# aqc-rev3.net
KiCad netlist of a schematic drawn in EAGLE
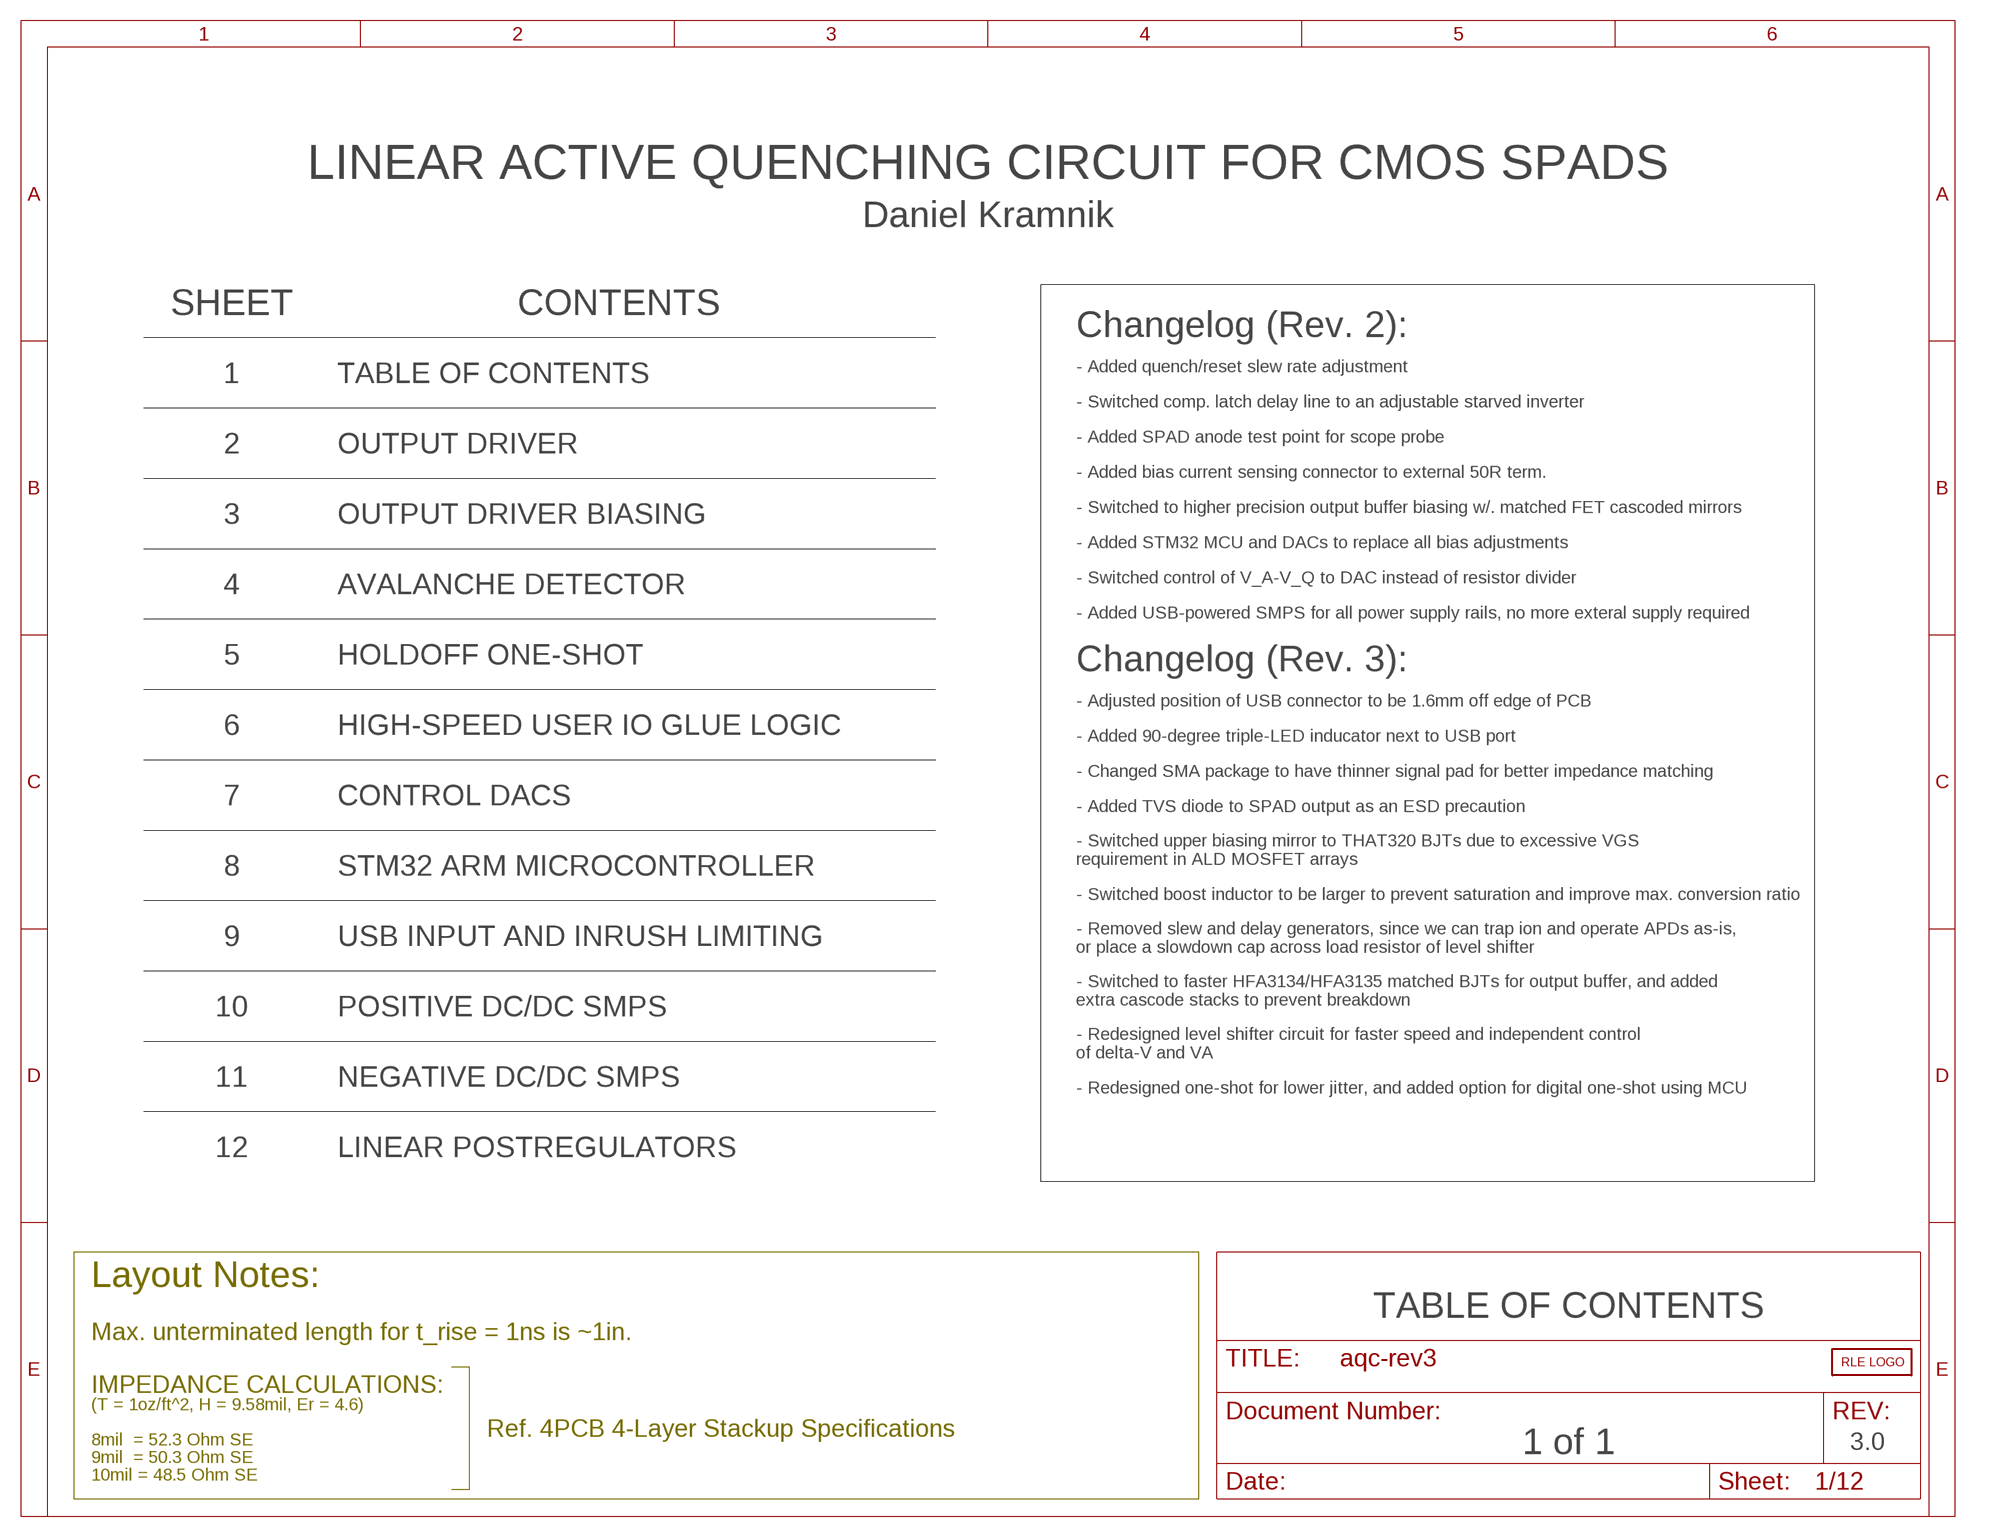
[diagram p0: schematic, sheet 1]
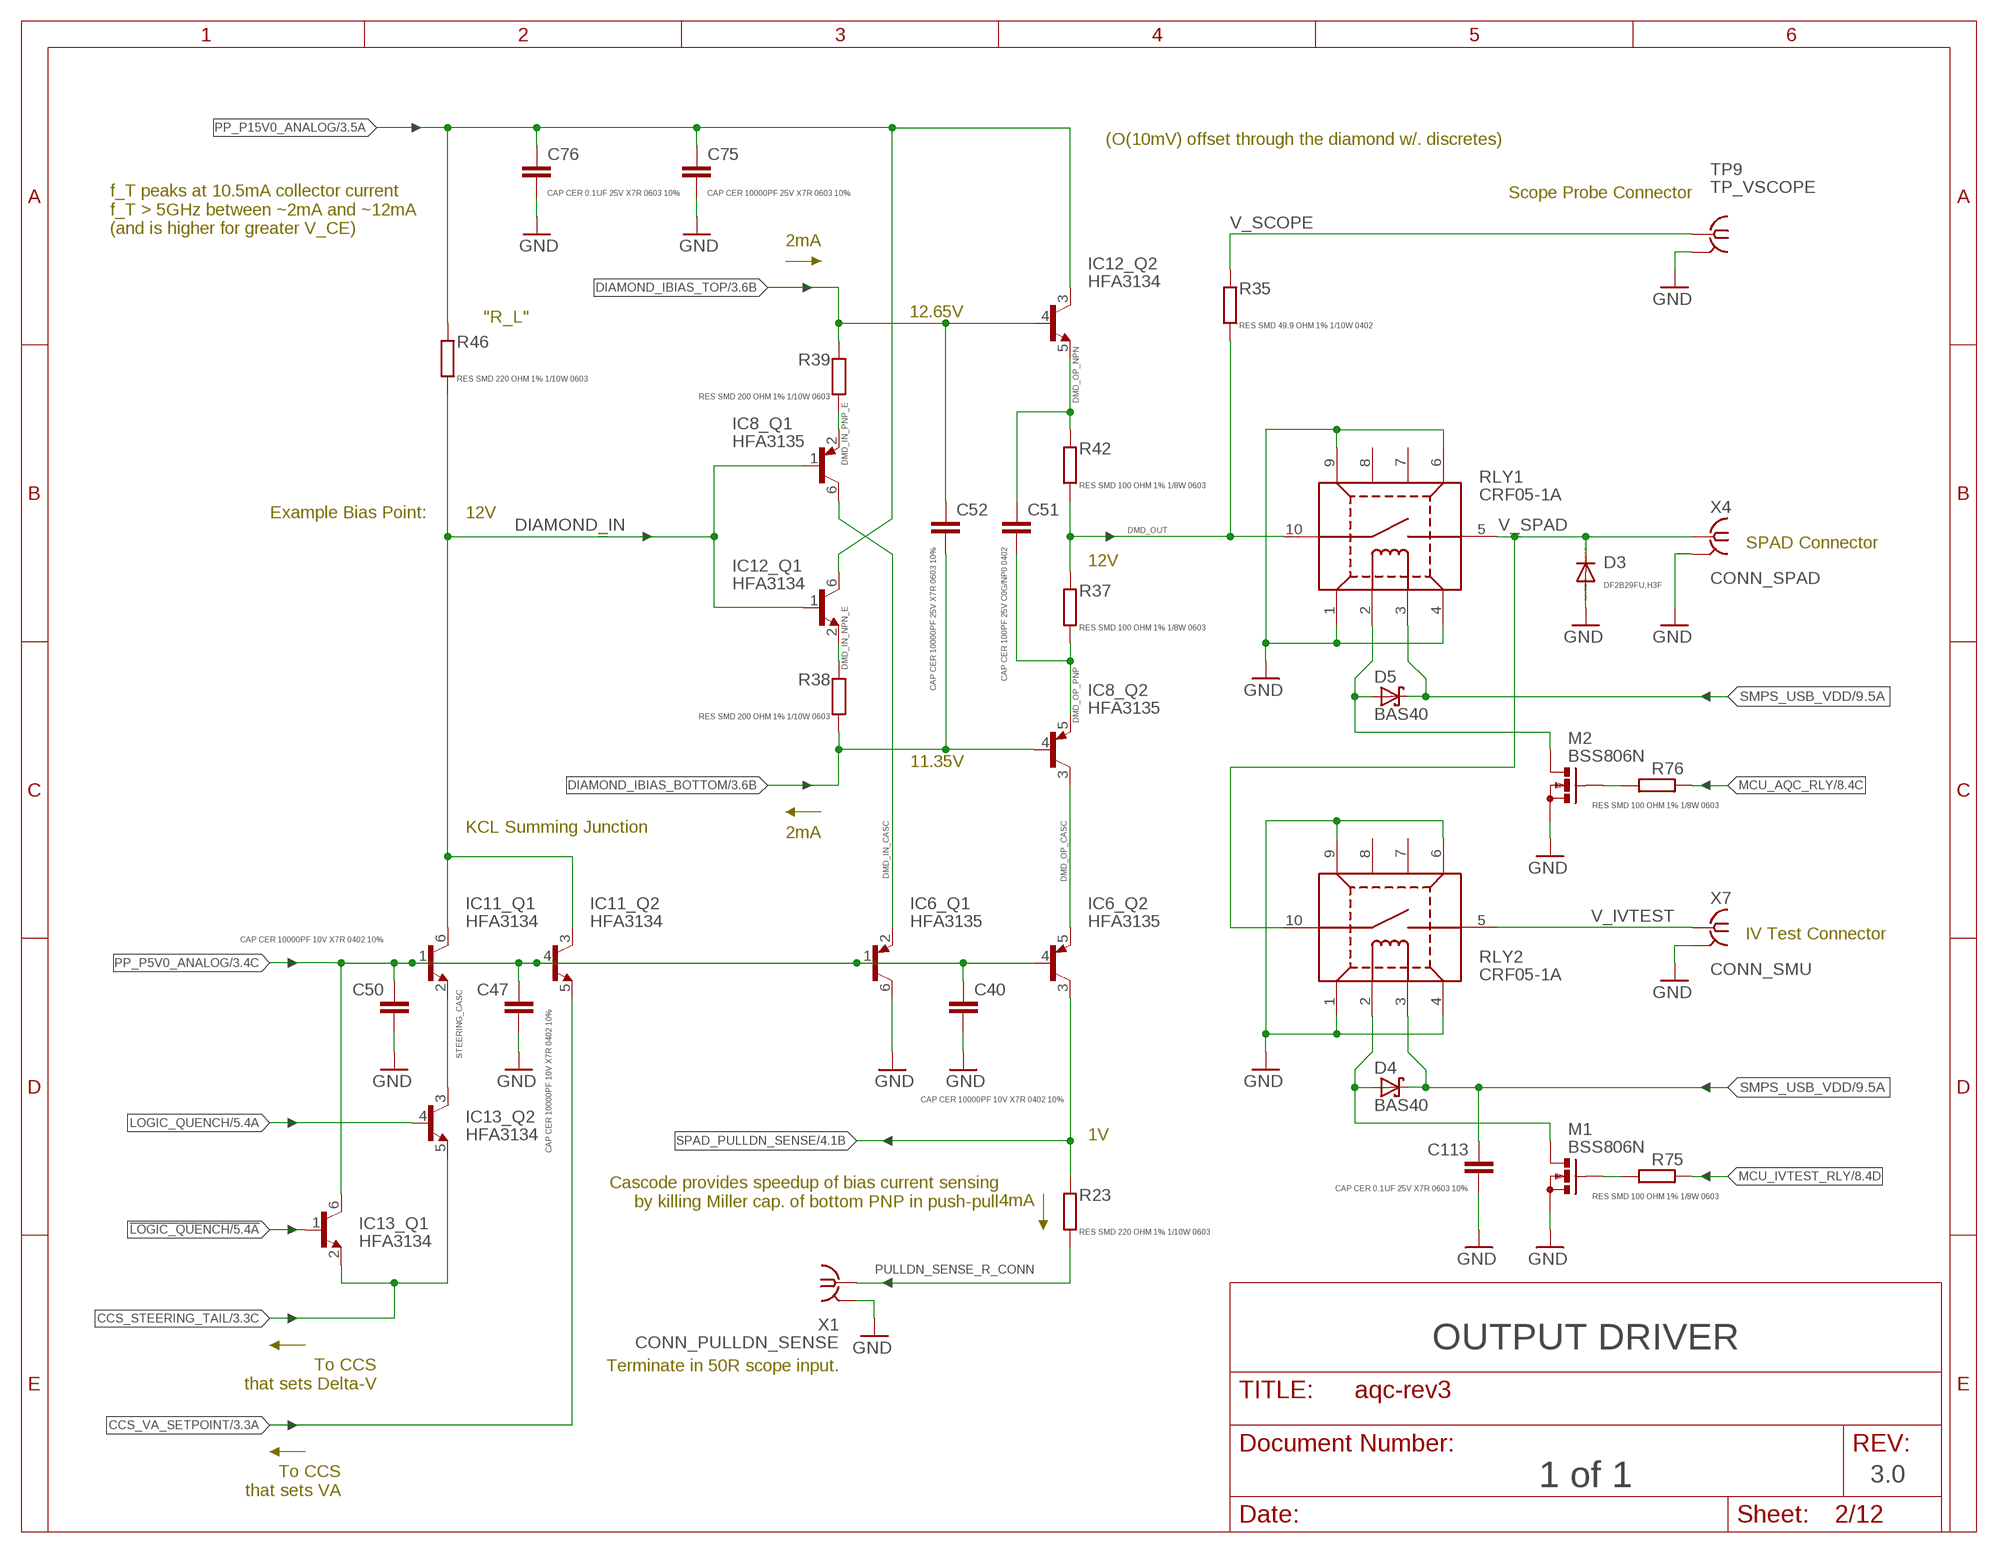
[diagram p1: schematic, sheet 2]
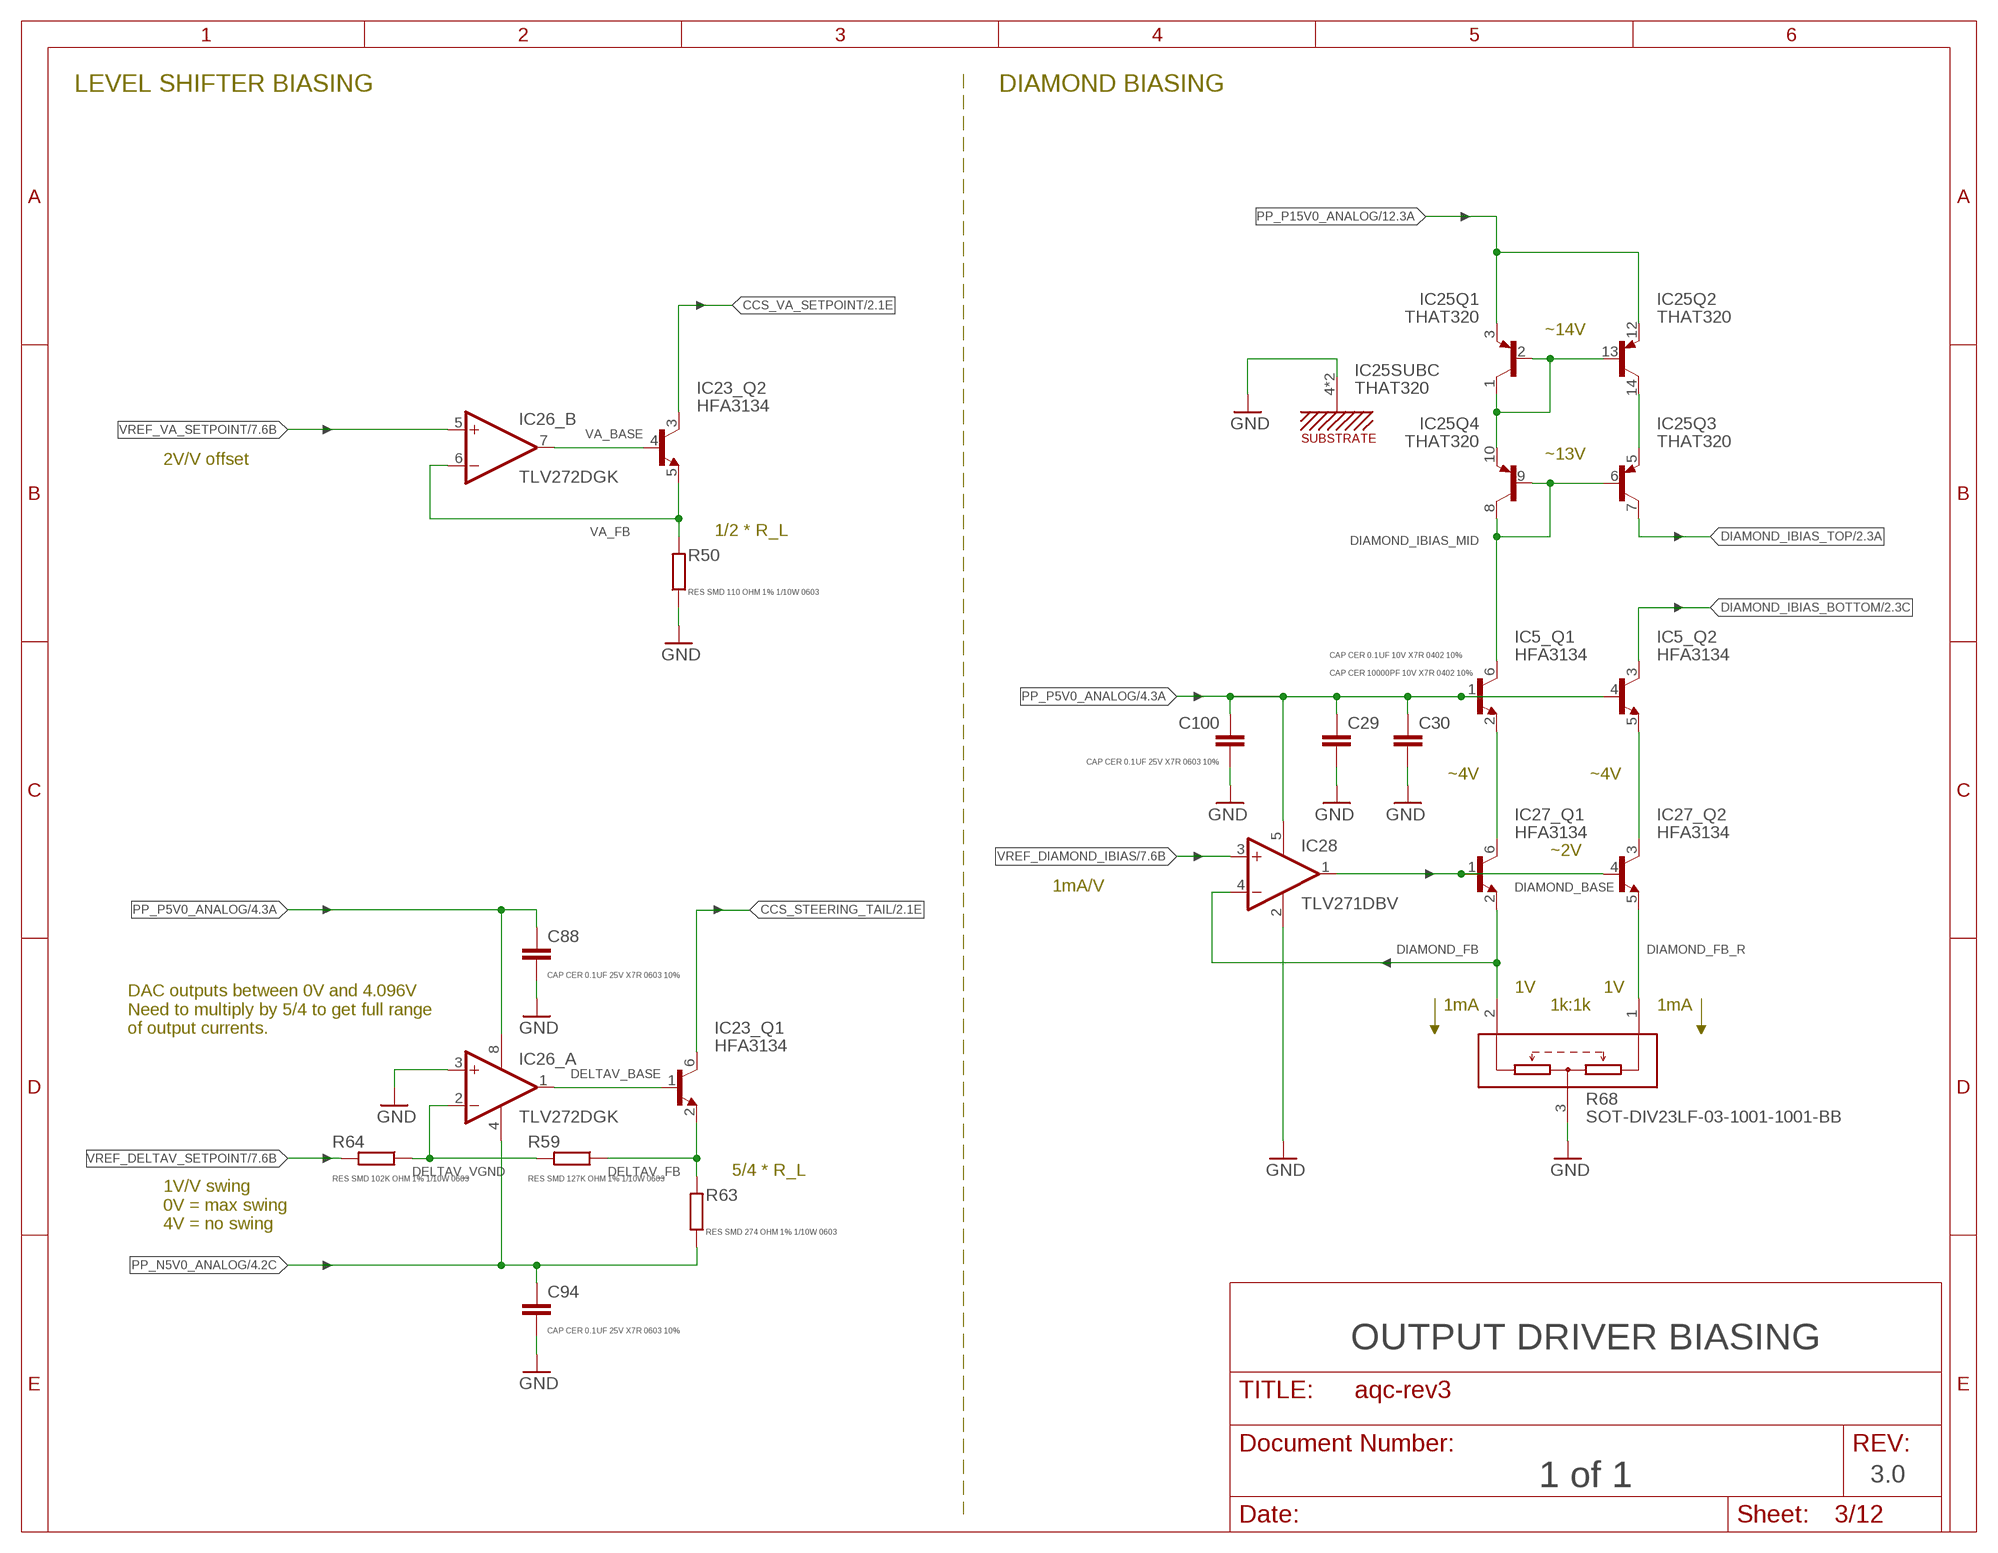
[diagram p2: schematic, sheet 3]
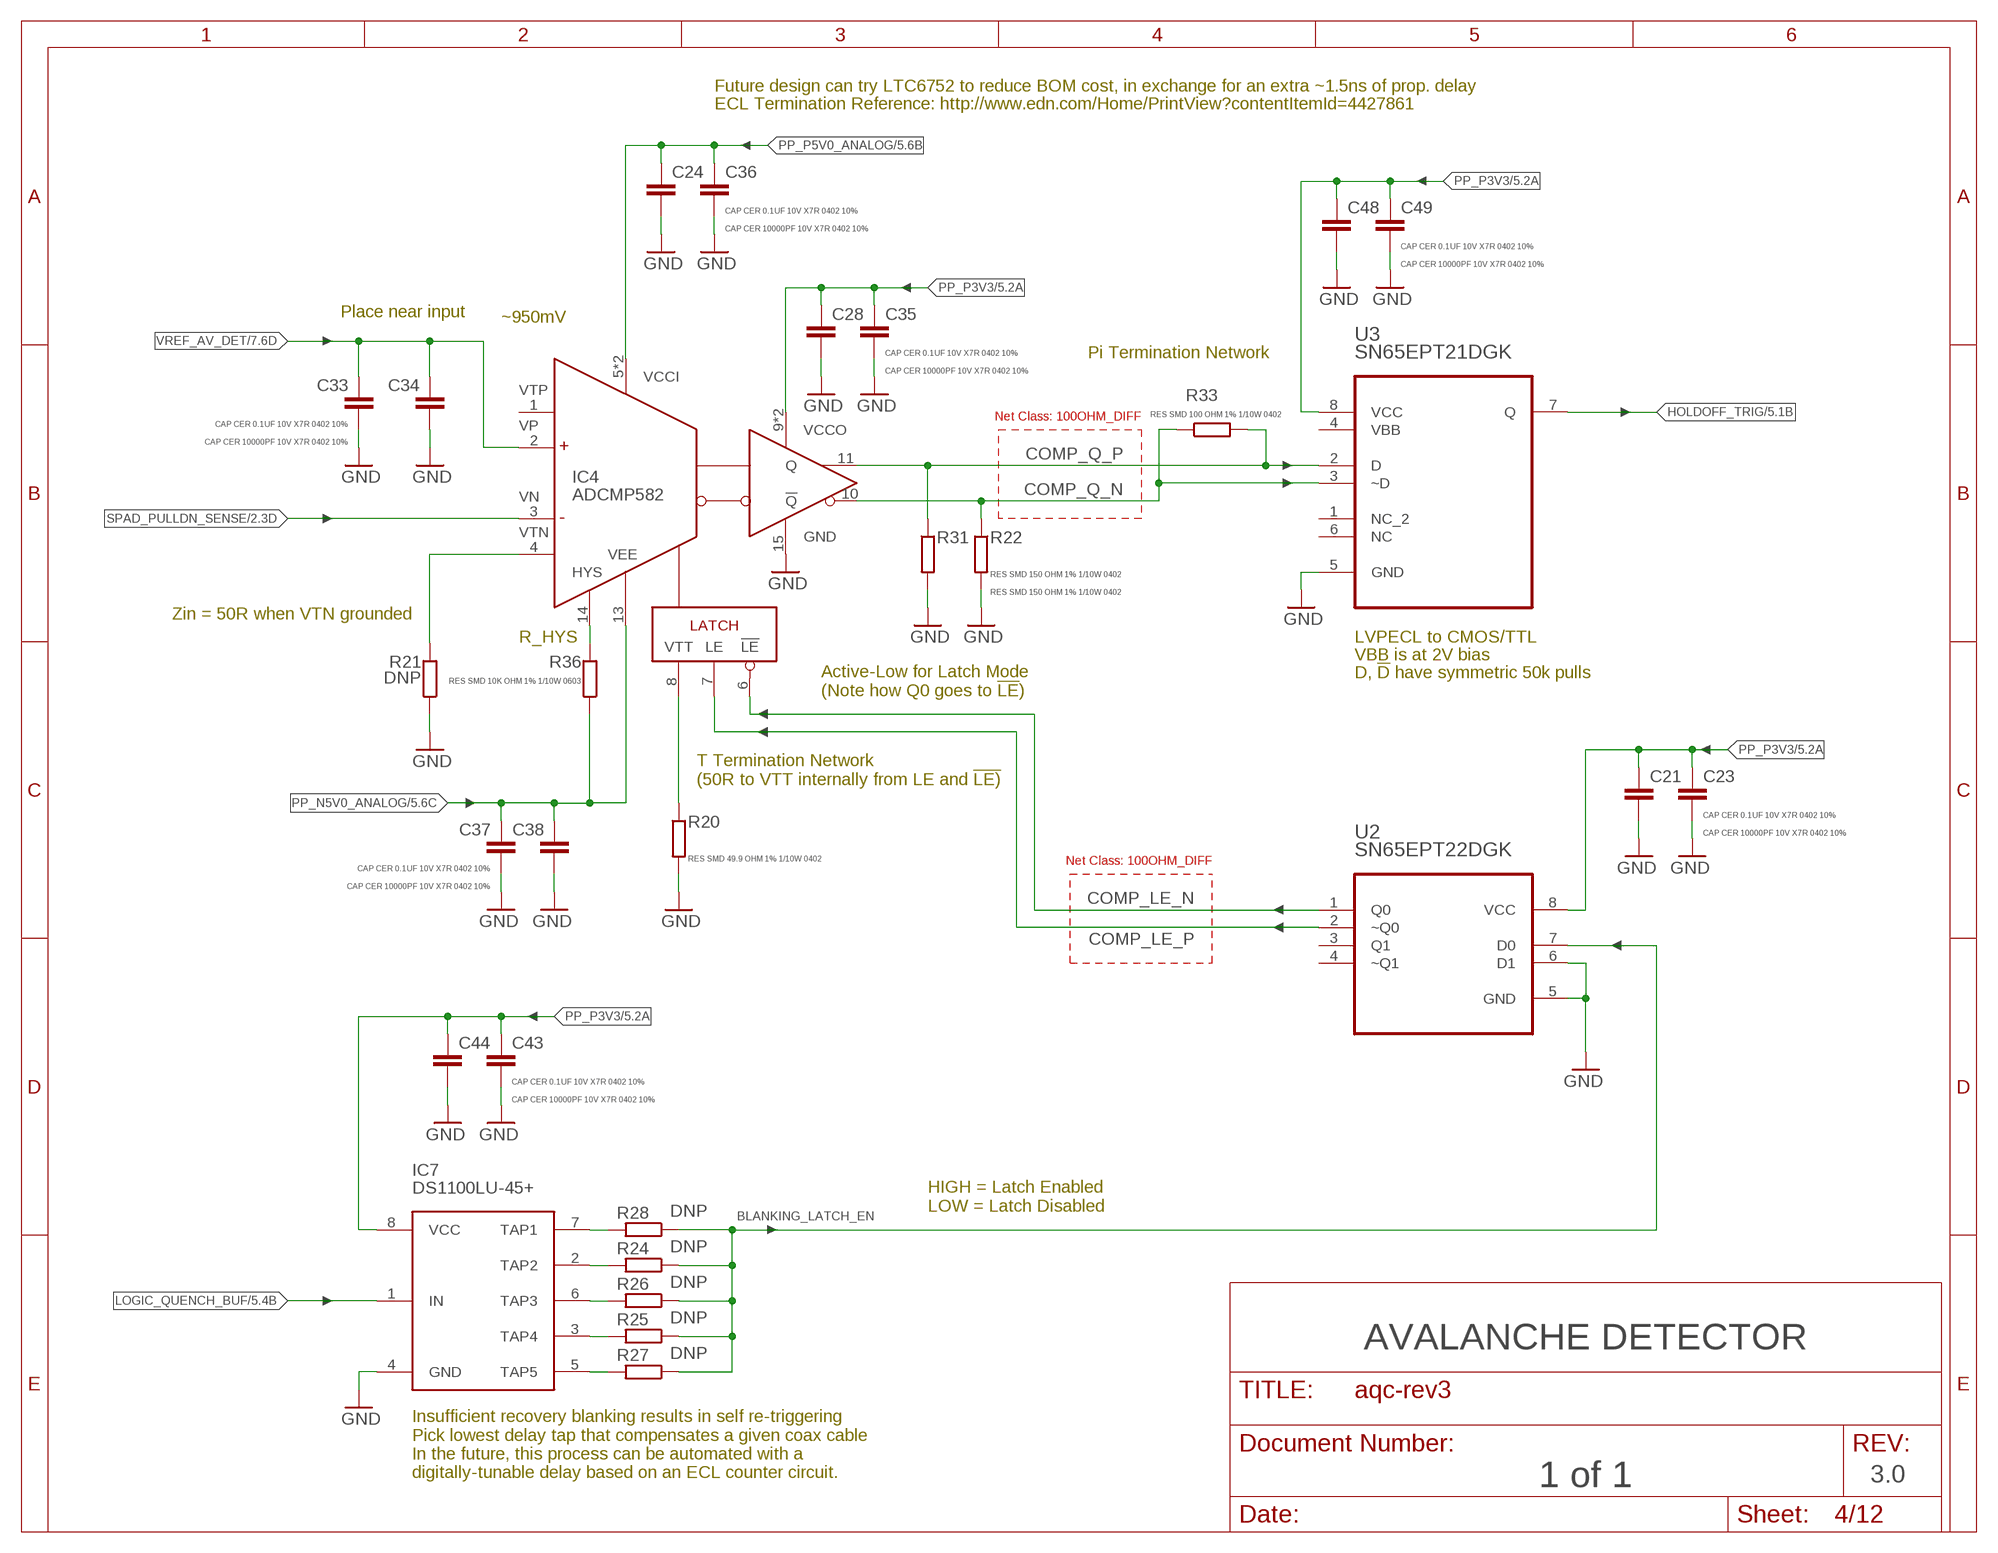
[diagram p3: schematic, sheet 4]
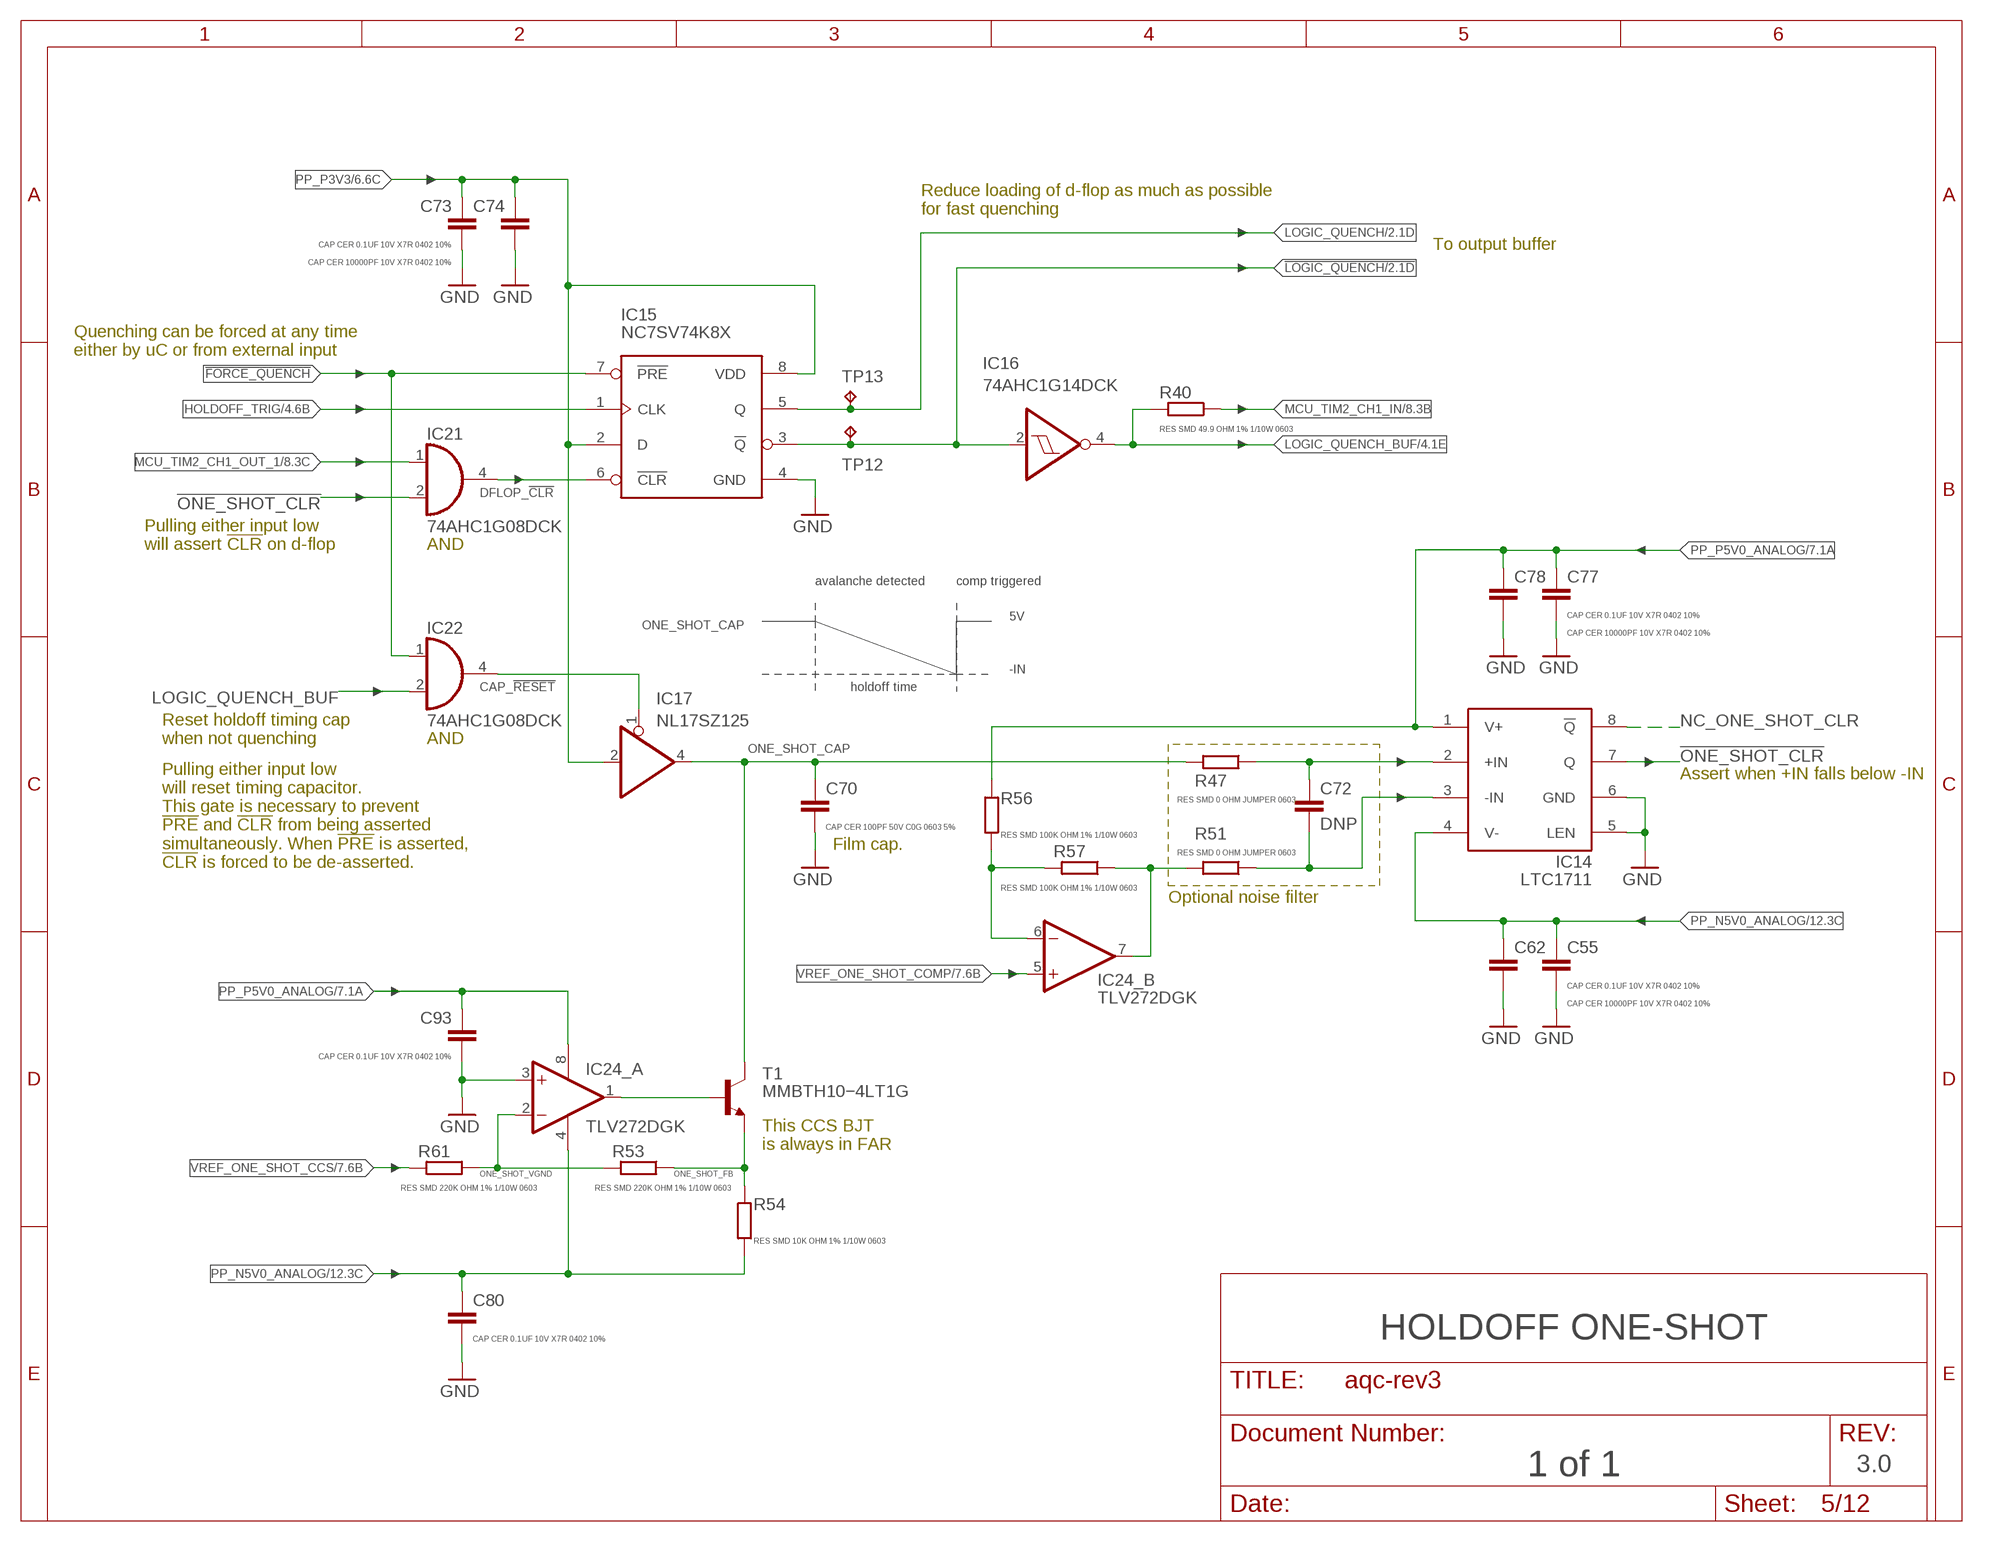
[diagram p4: schematic, sheet 5]
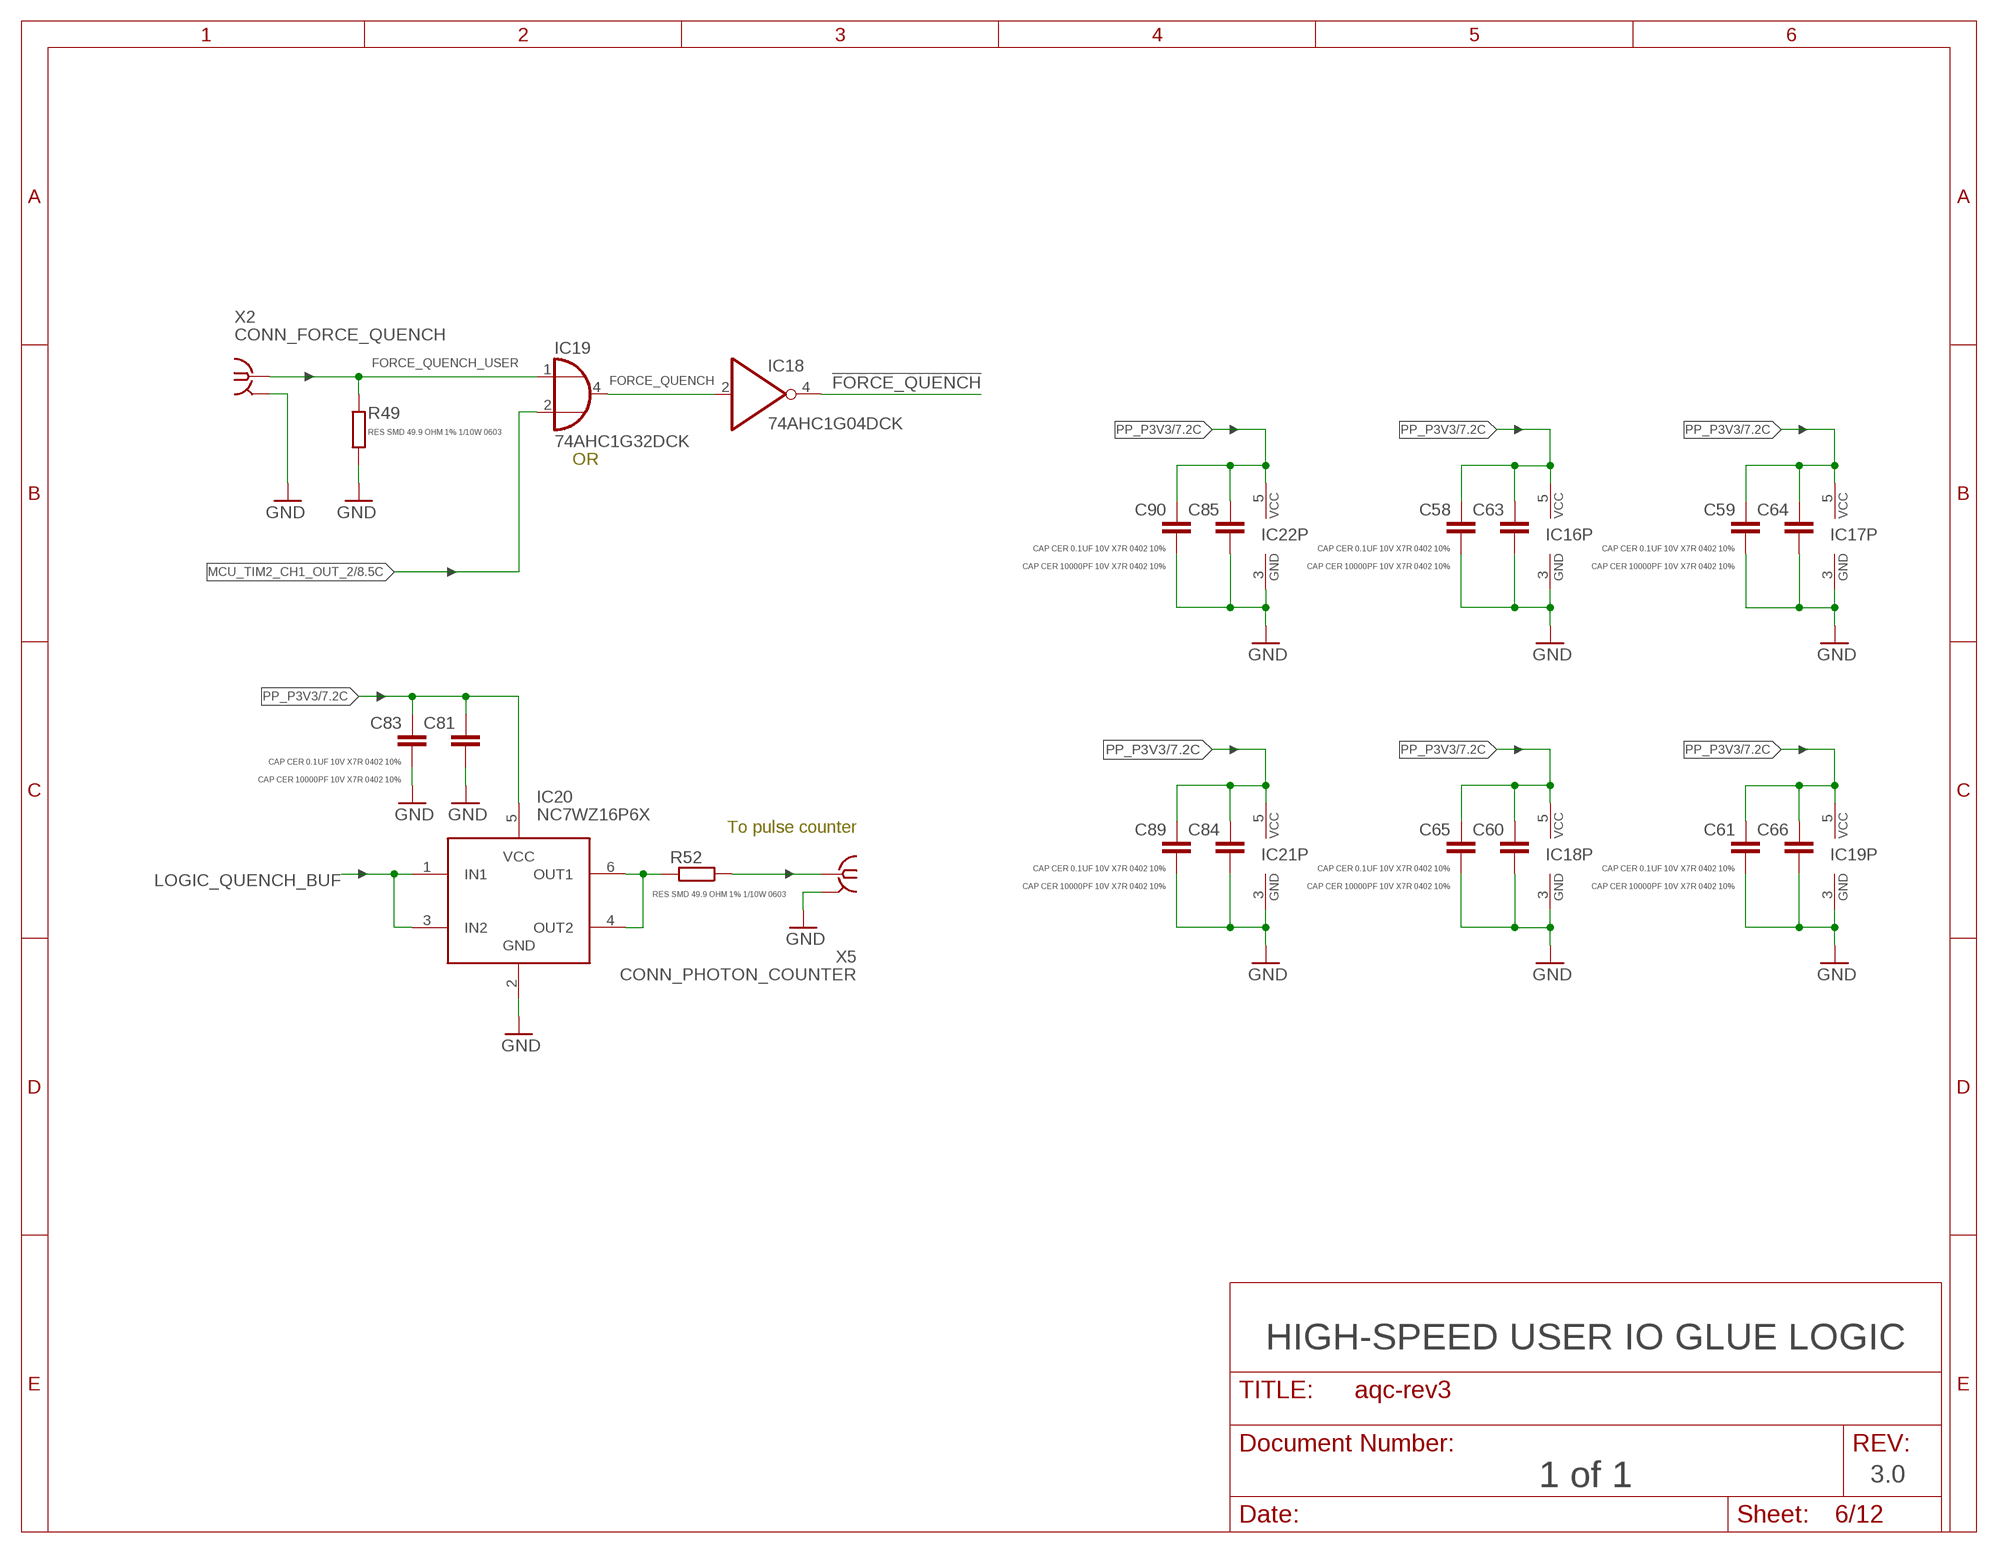
[diagram p5: schematic, sheet 6]
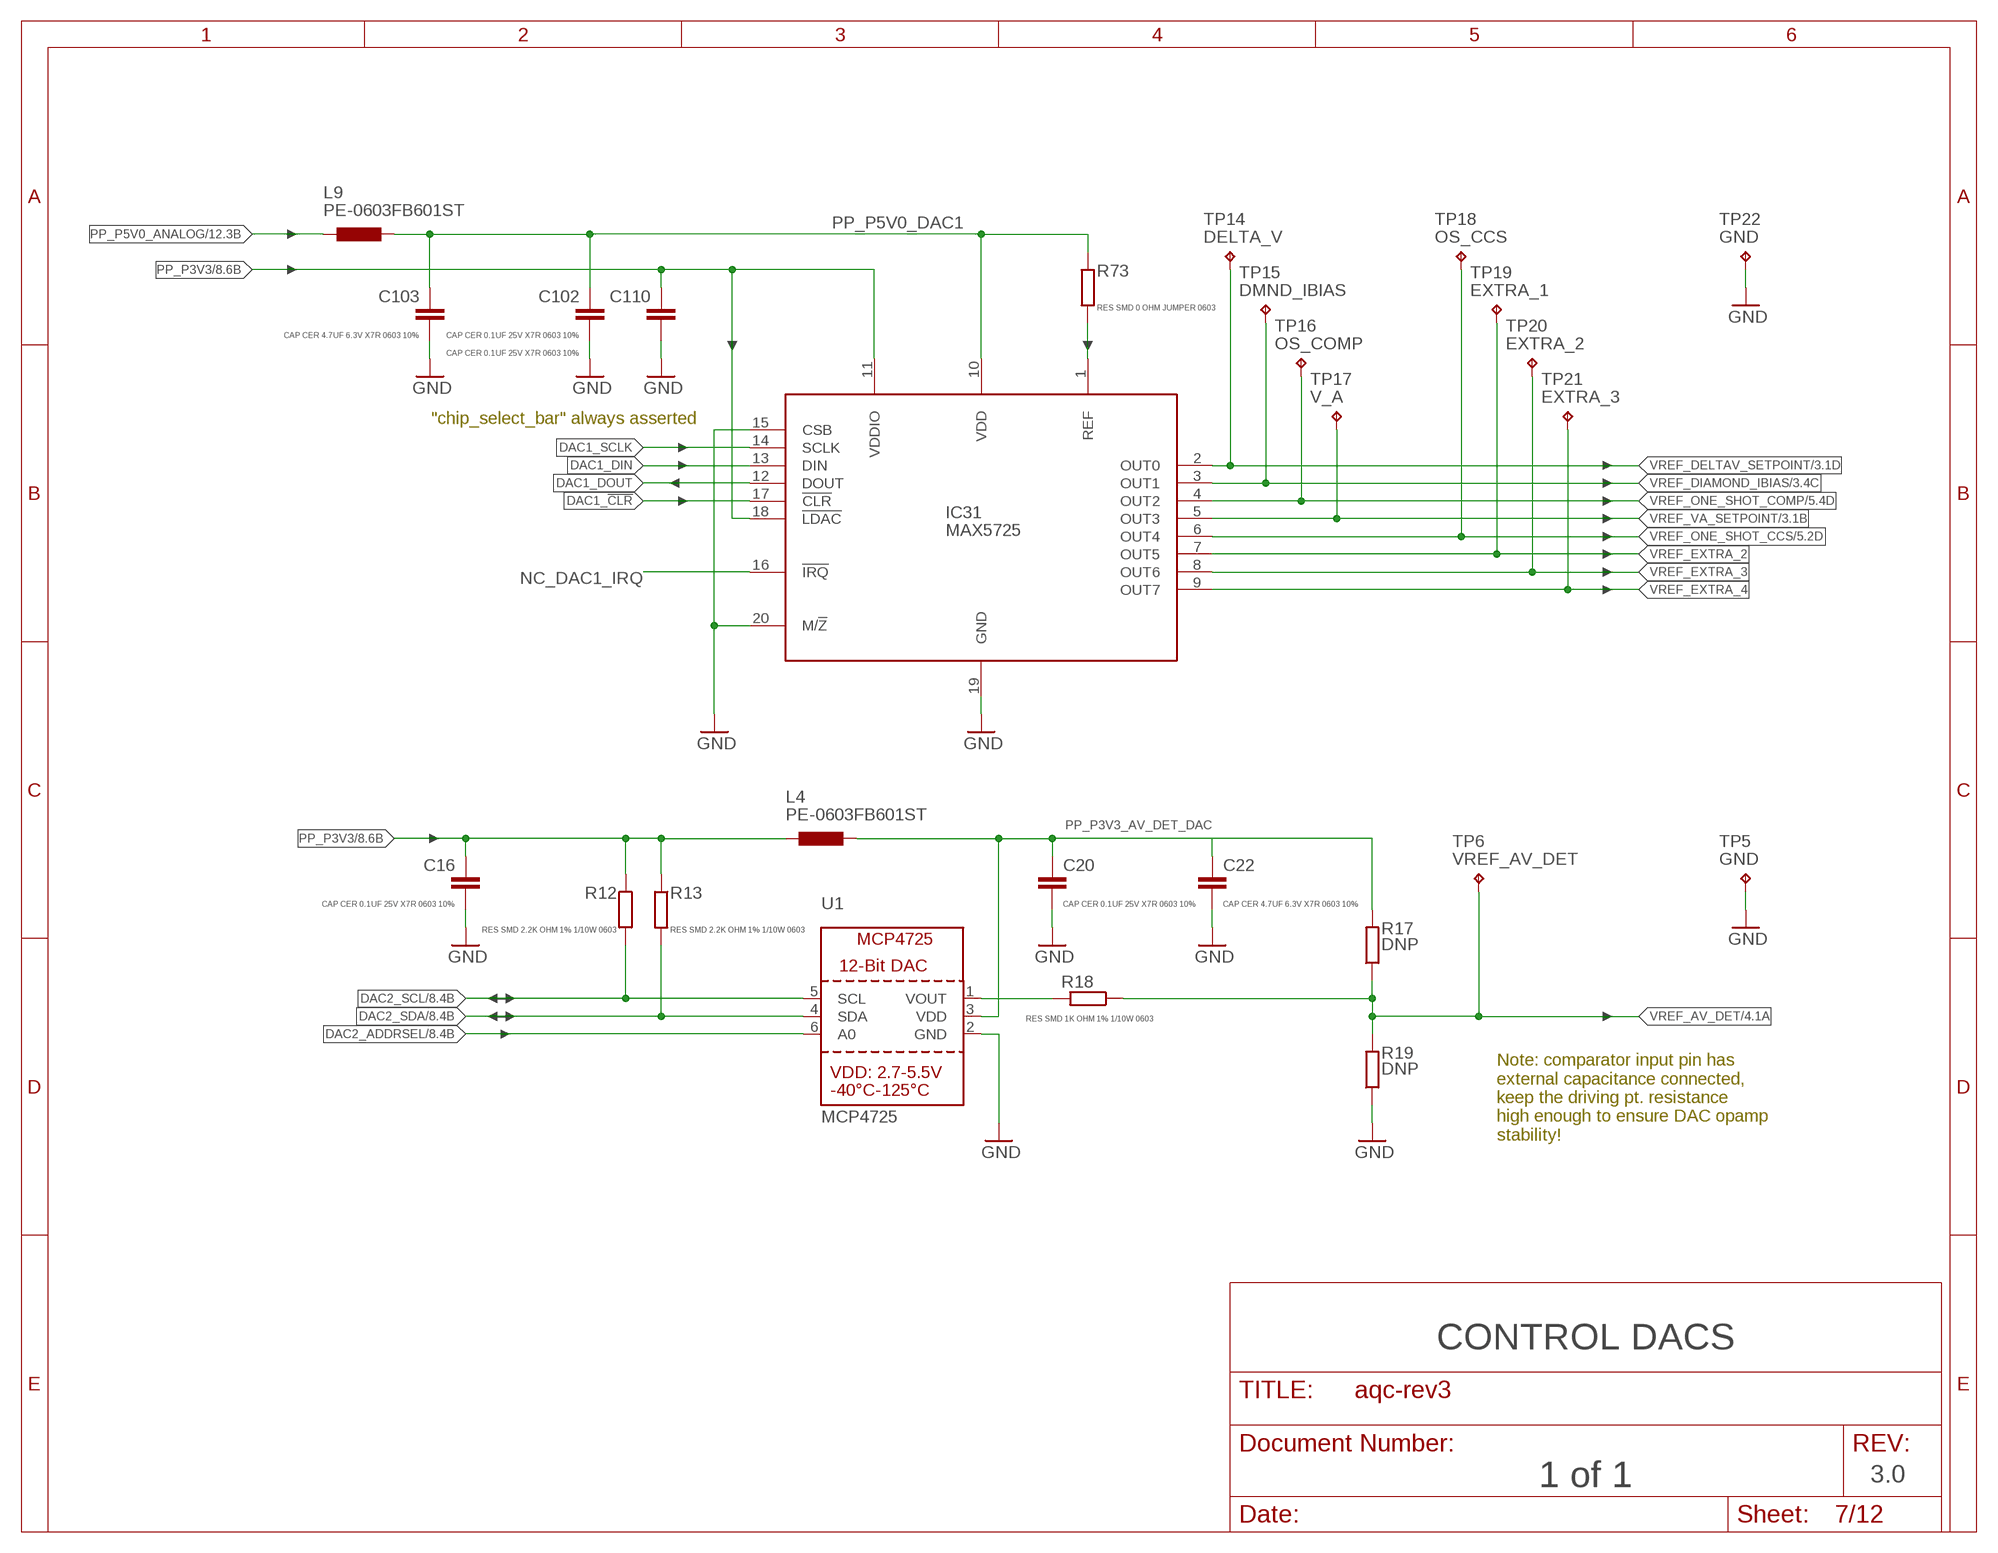
[diagram p6: schematic, sheet 7]
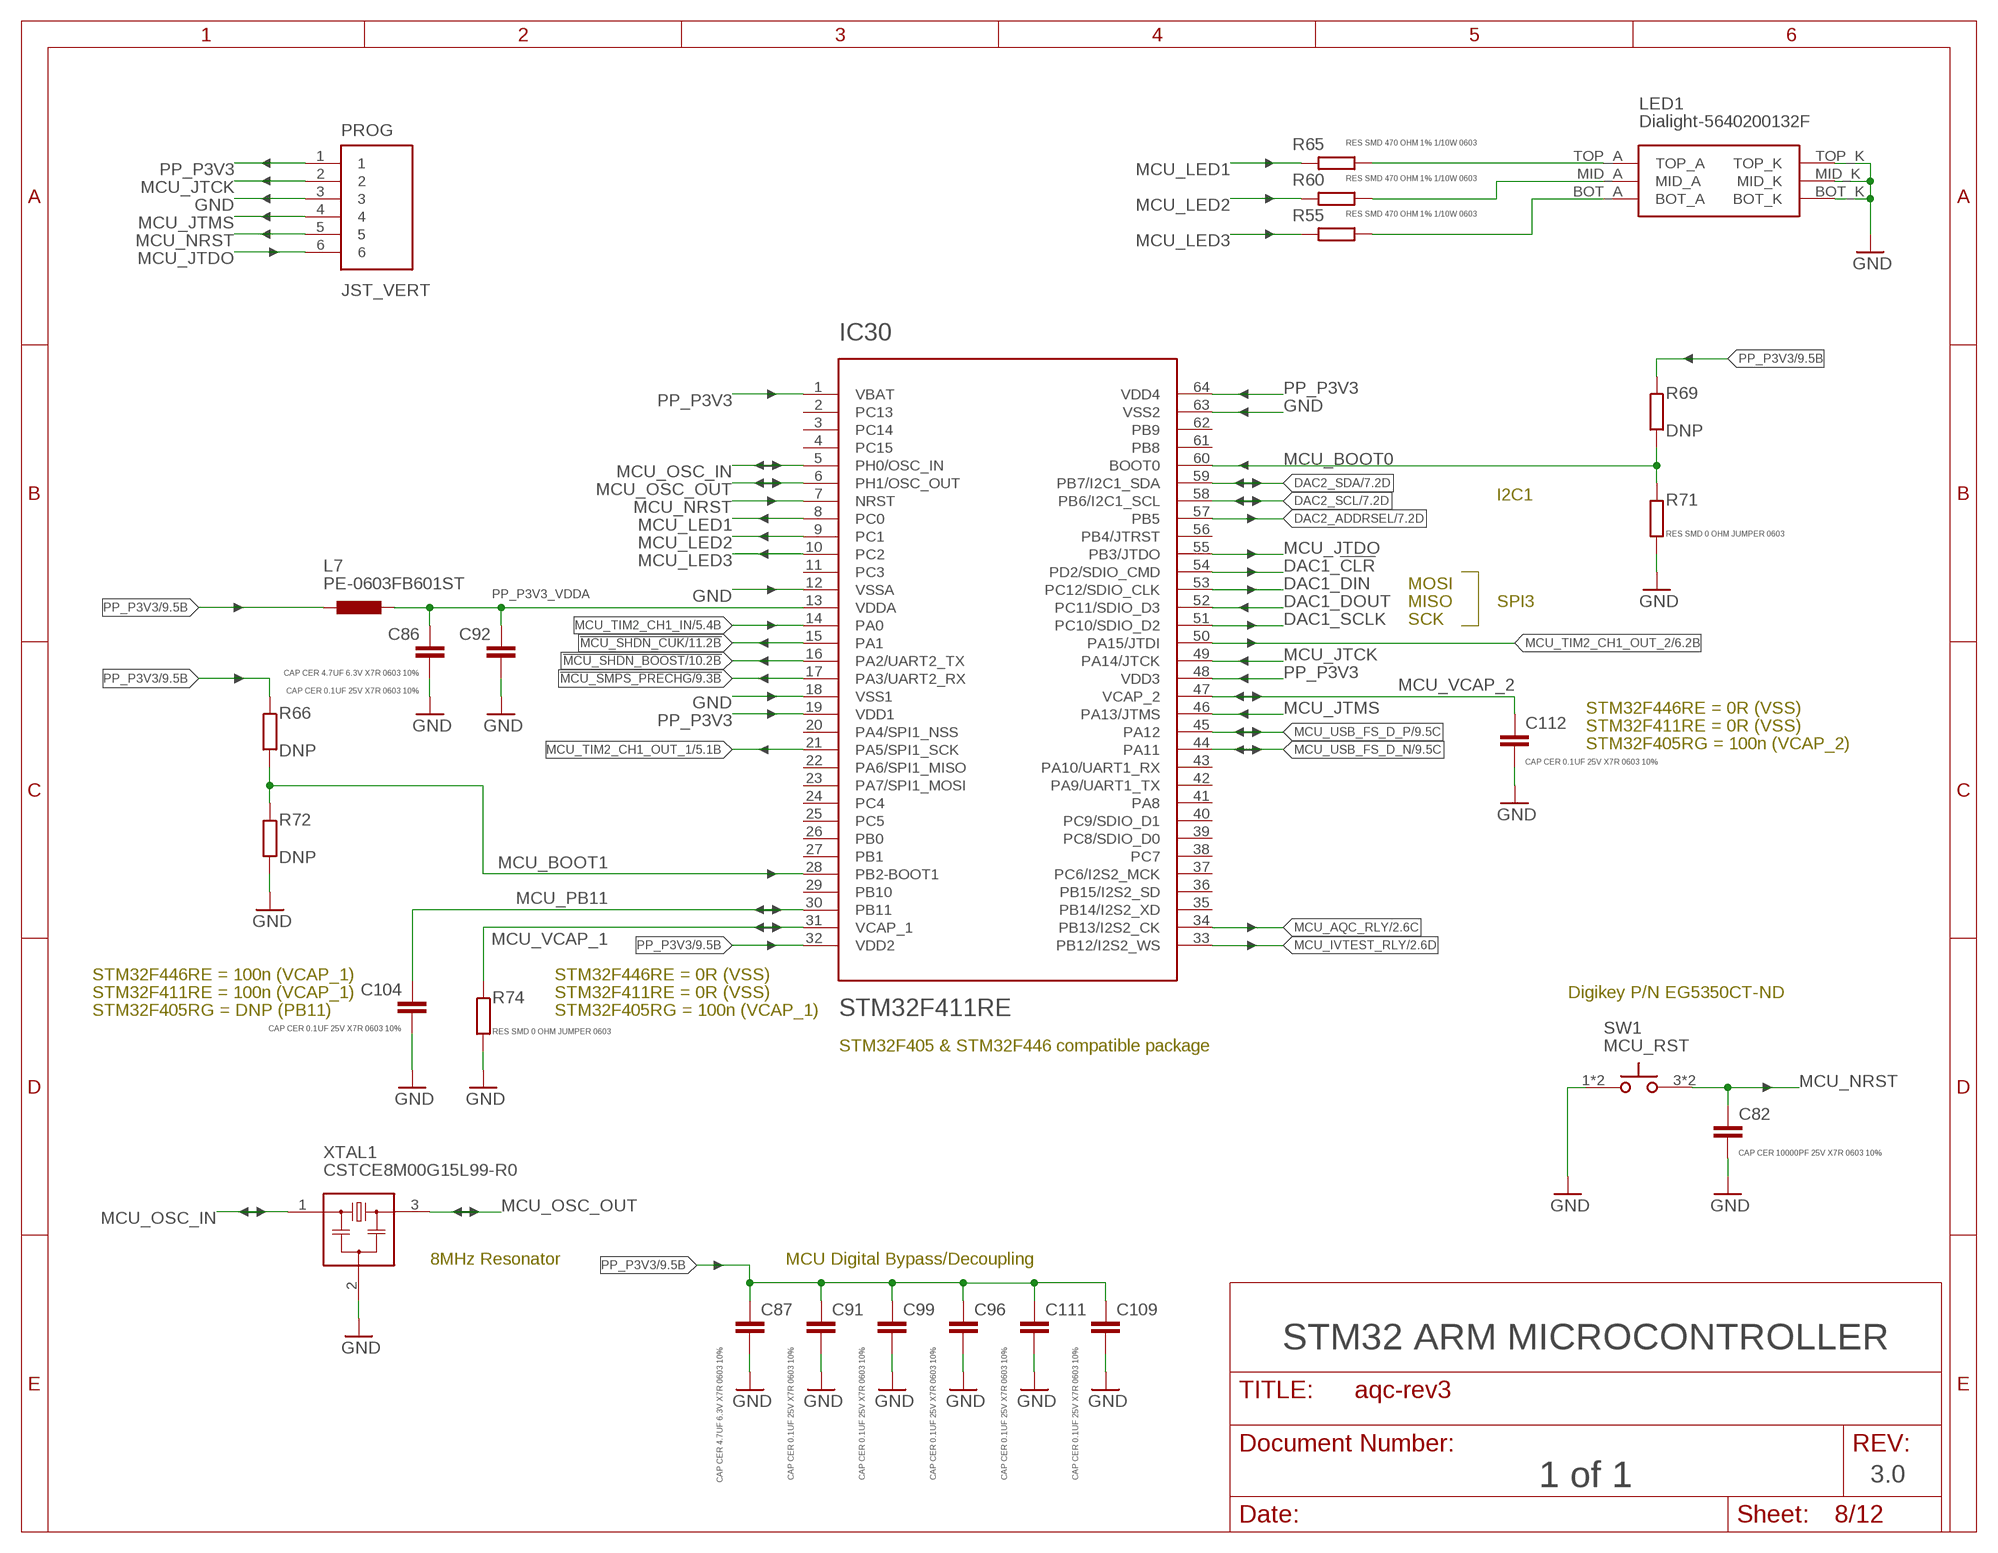
[diagram p7: schematic, sheet 8]
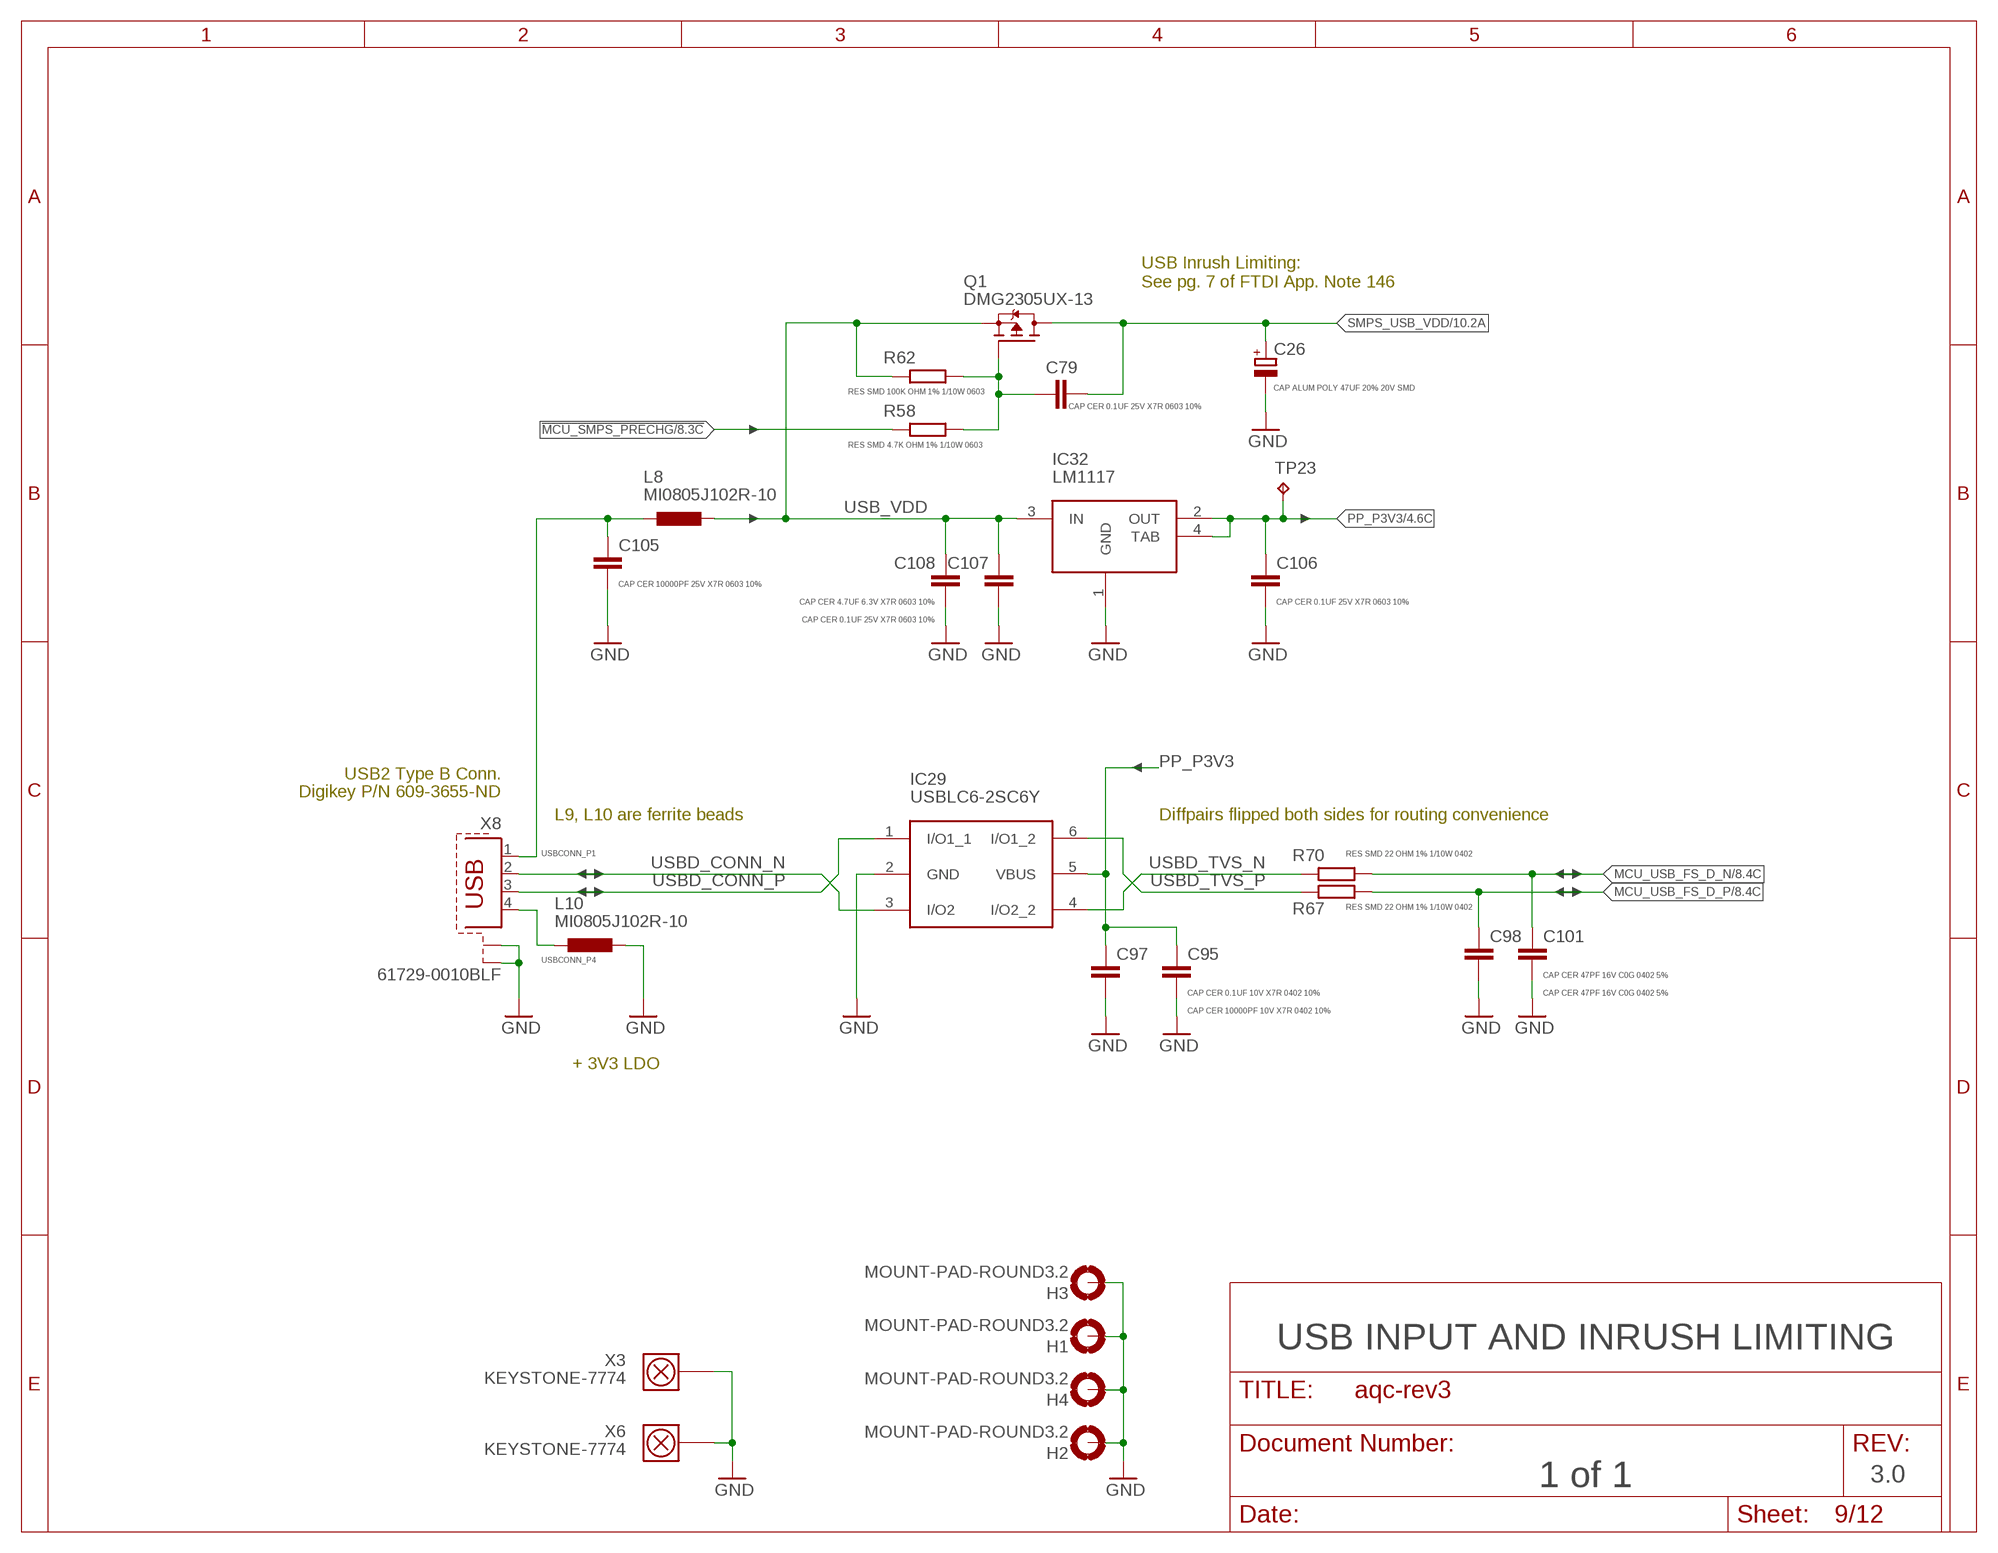
[diagram p8: schematic, sheet 9]
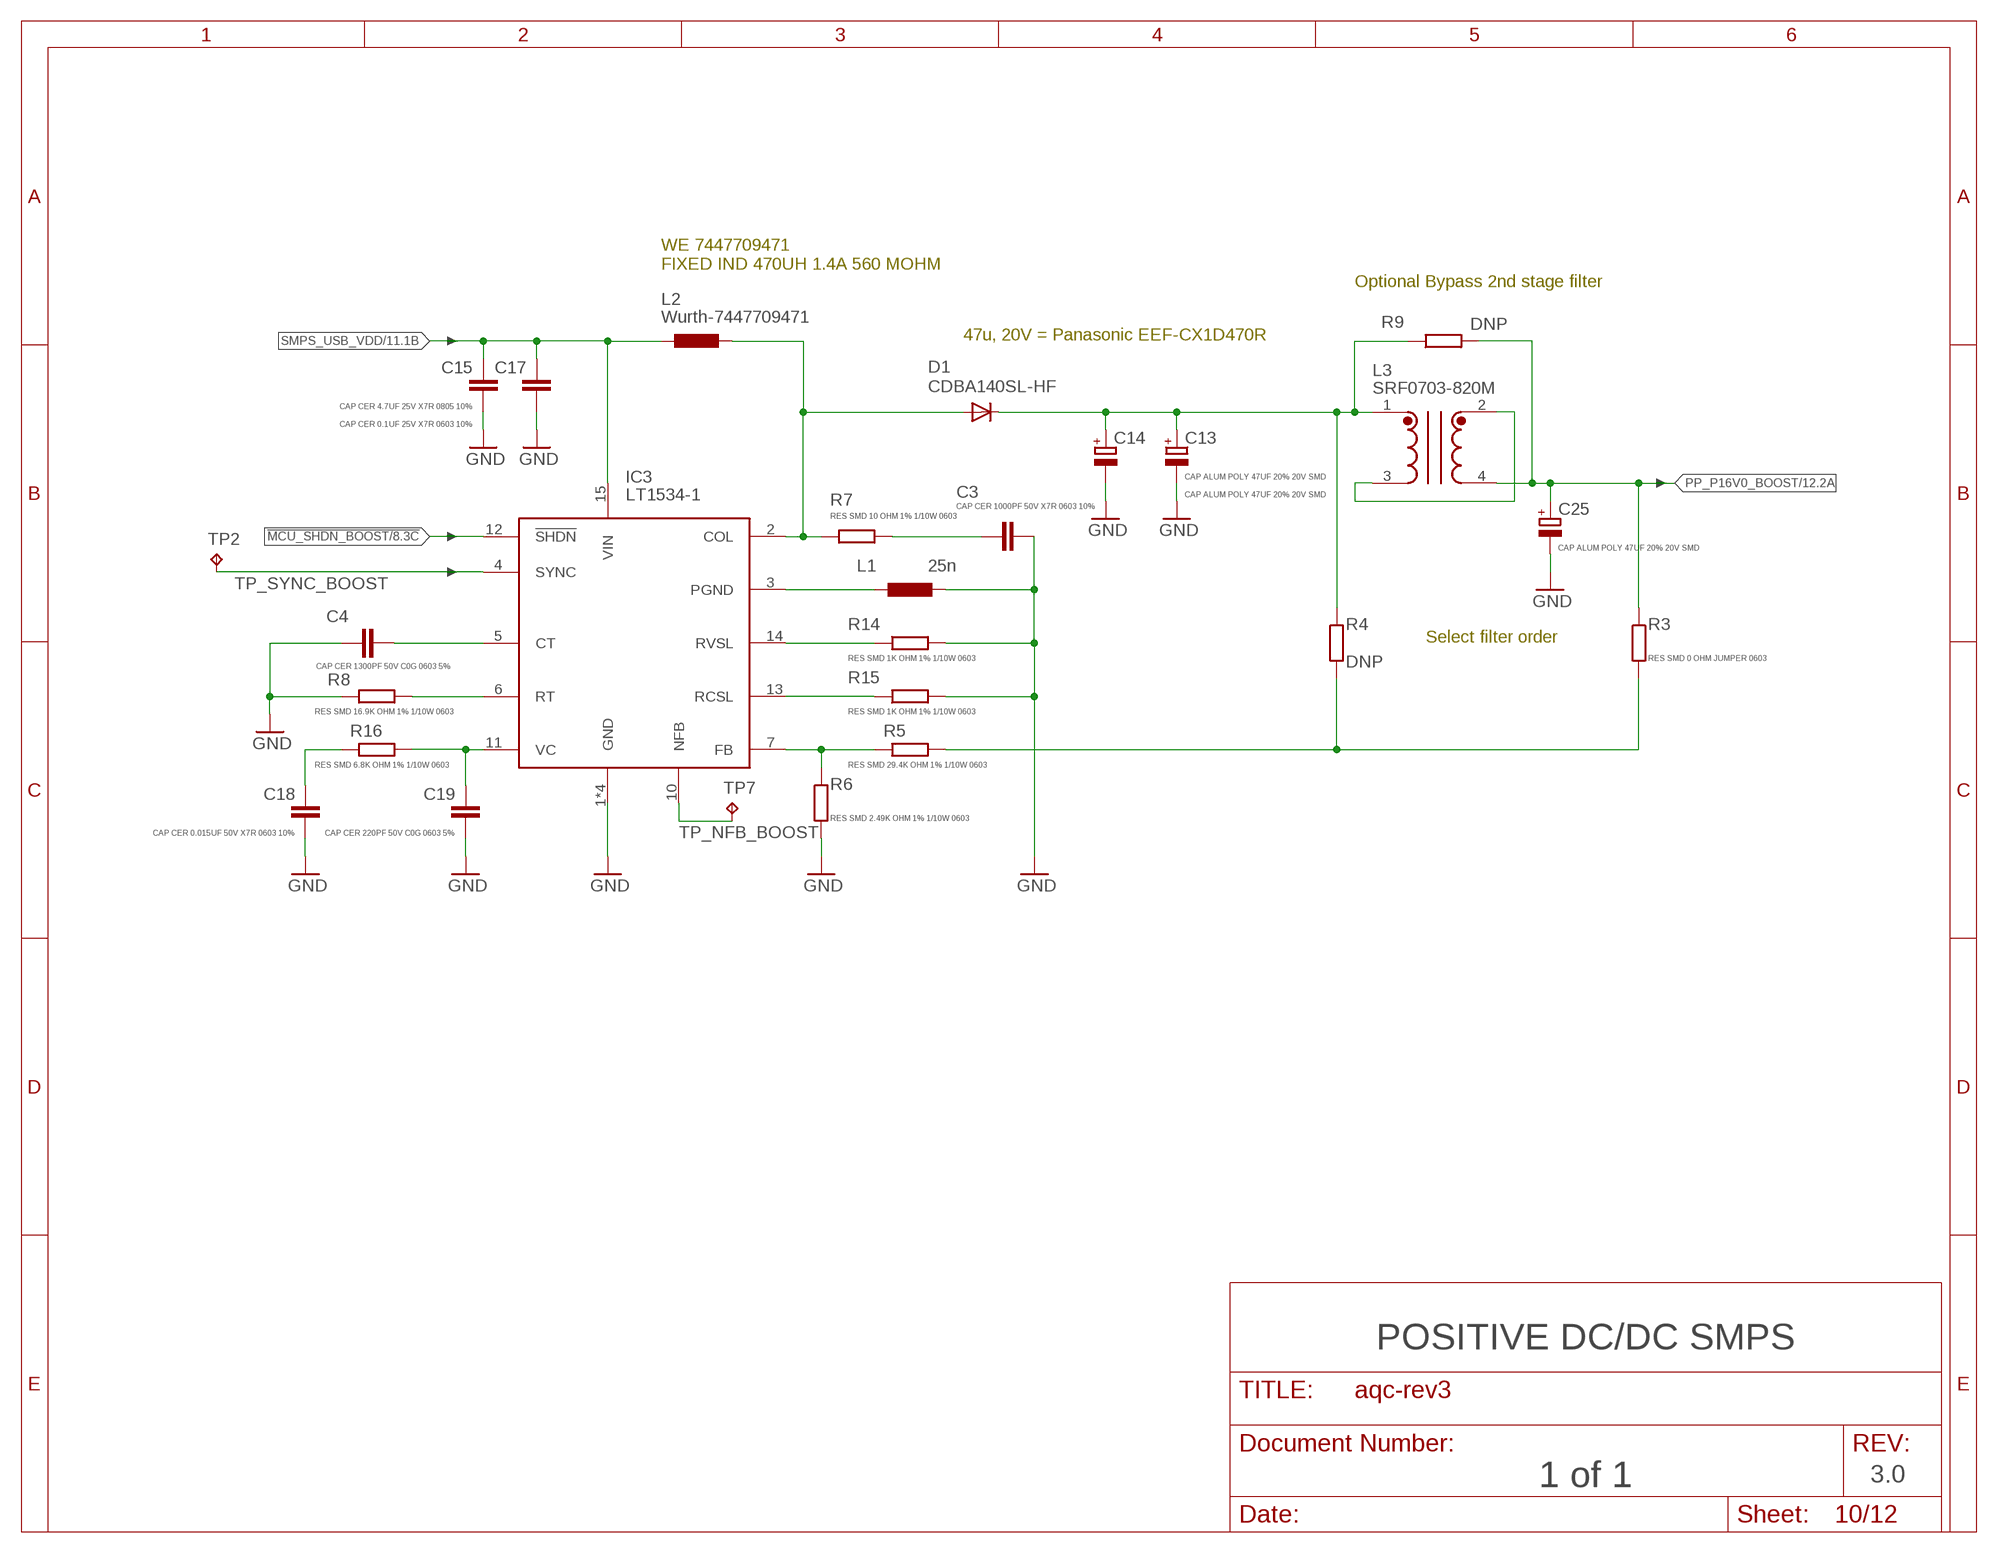
[diagram p9: schematic, sheet 10]
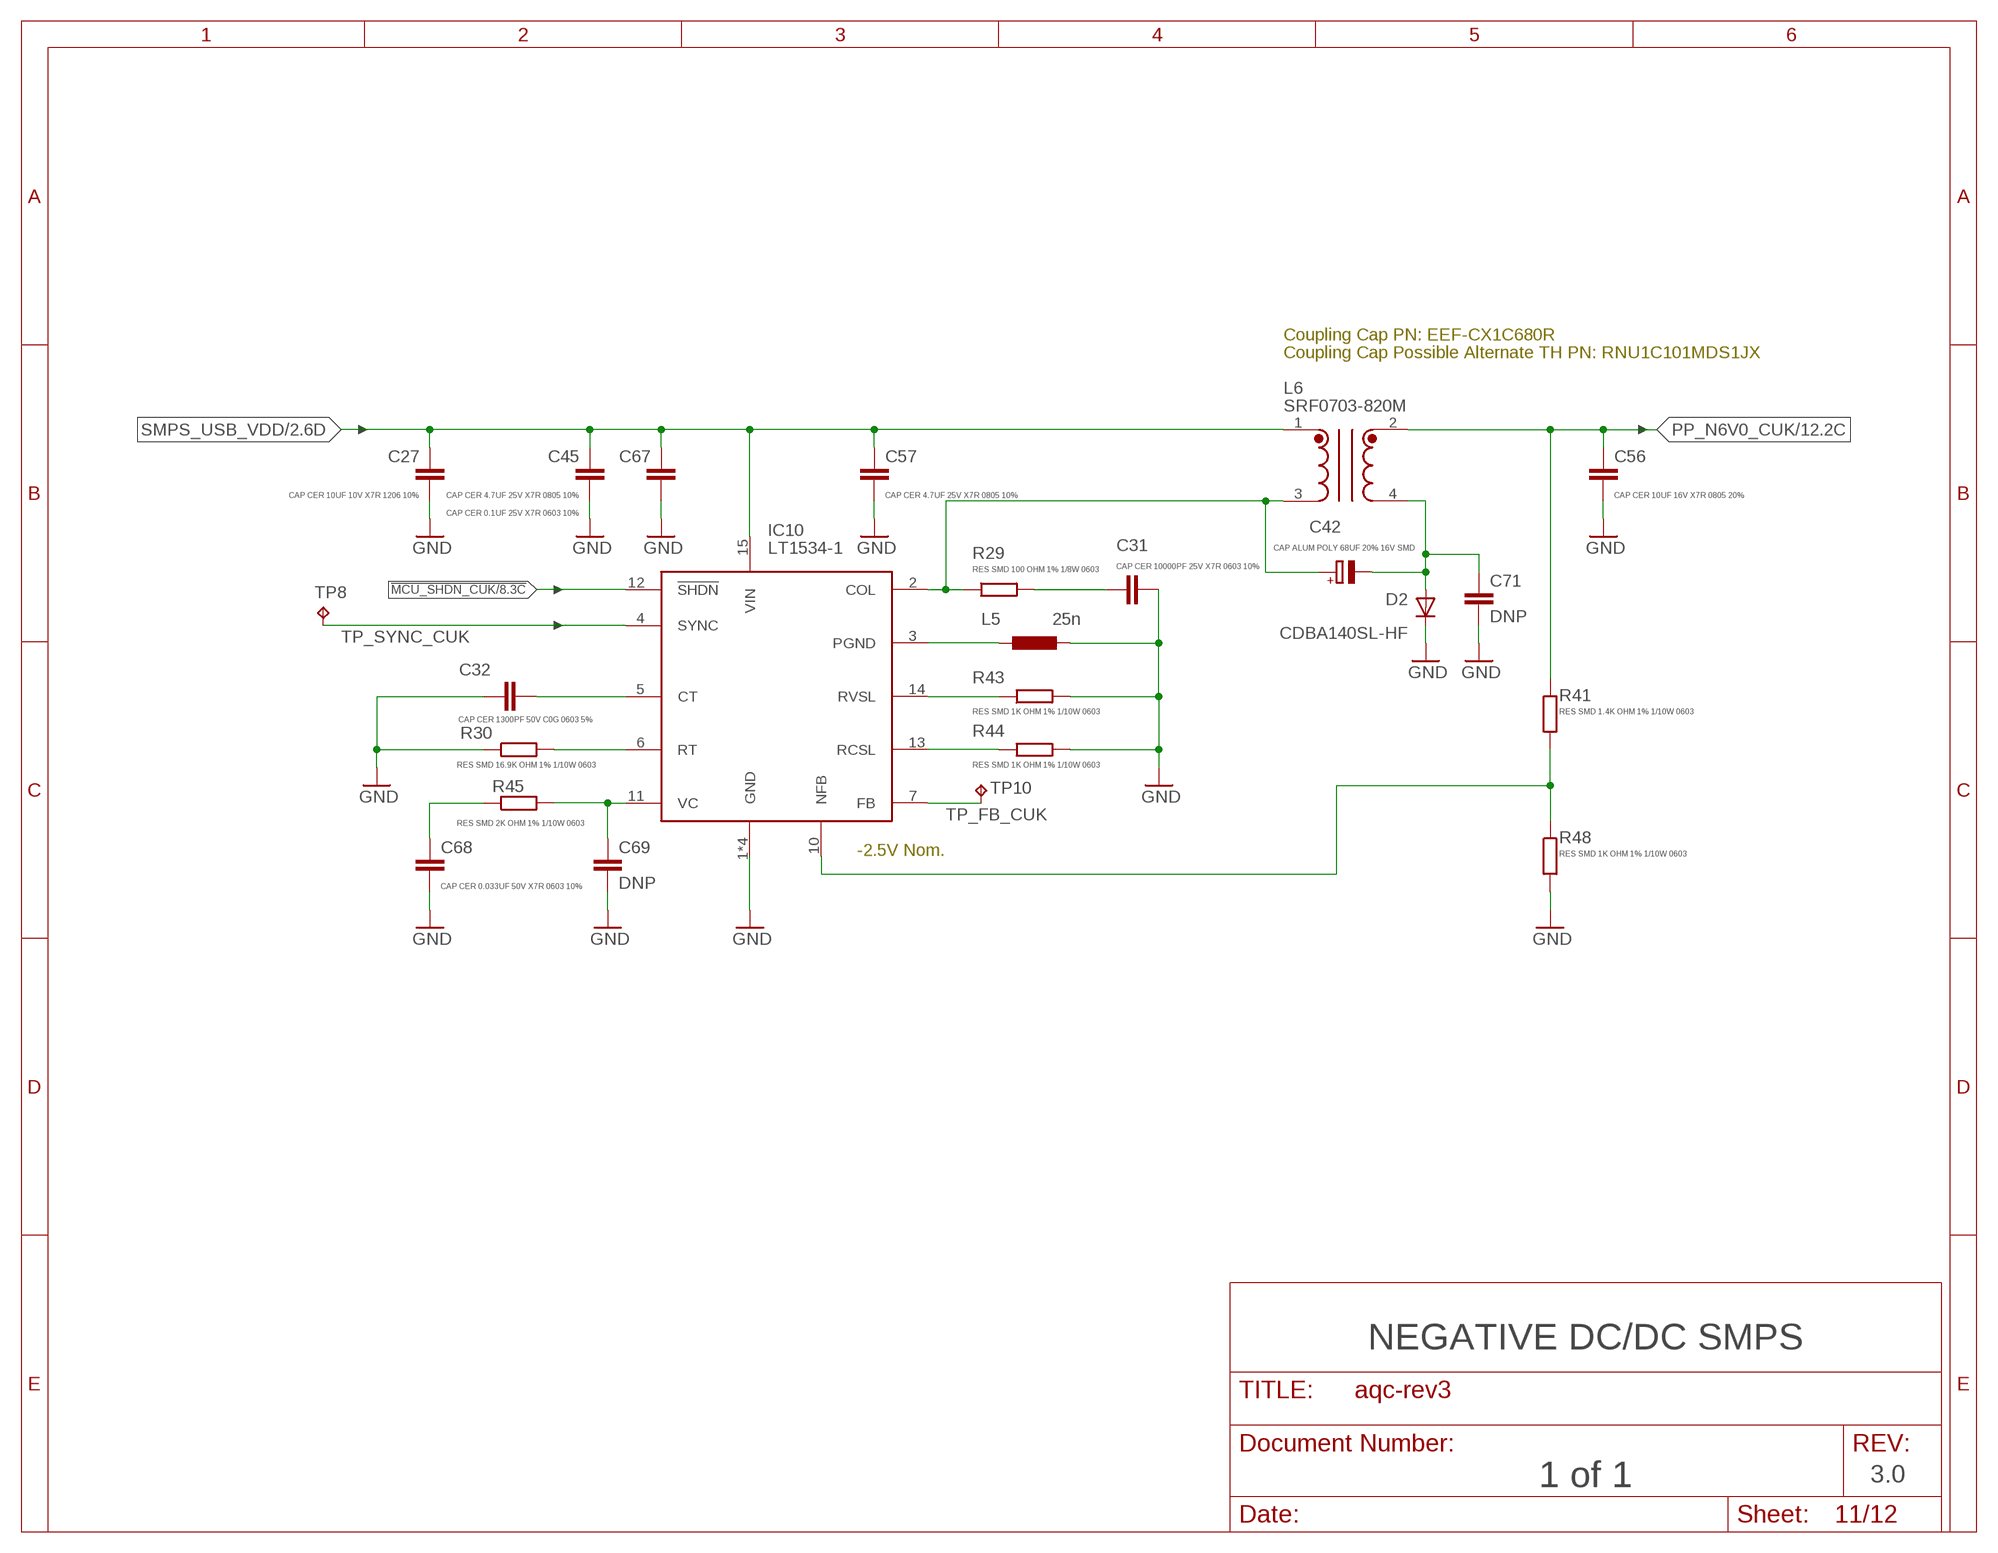
[diagram p10: schematic, sheet 11]
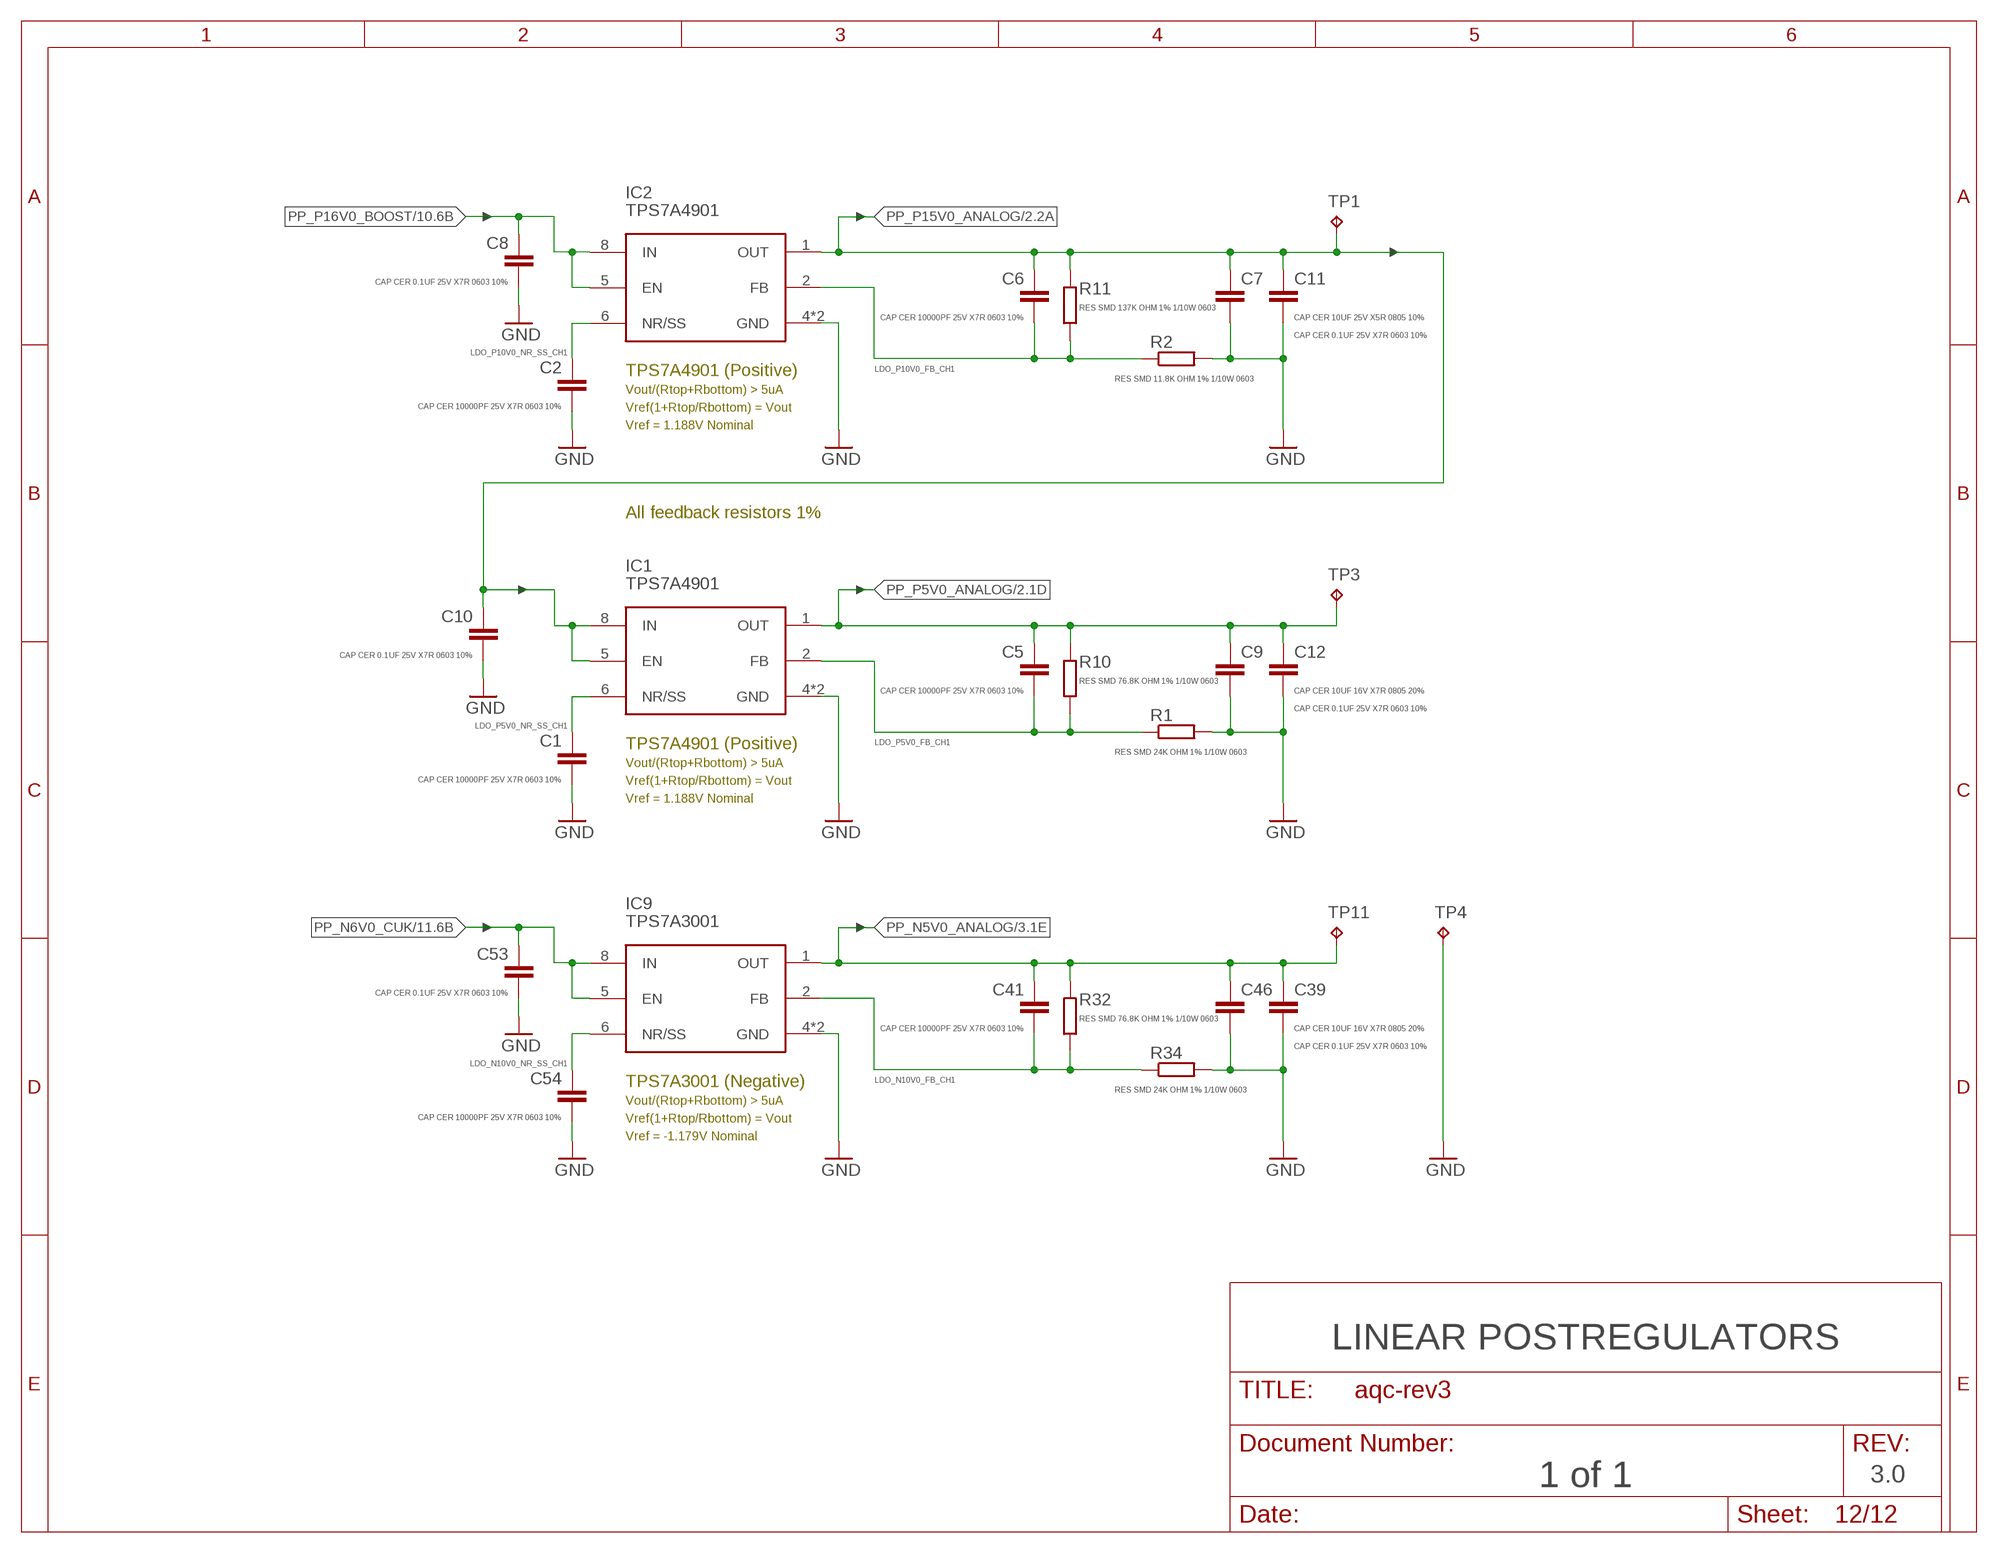
[diagram p11: schematic, sheet 12]

(export (version "E")
  (design (tool "Eeschema 10.0.6"))
  (components
    (comp (ref "C16")
      (value "CAP CER 0.1UF 25V X7R 0603 10%")
      (footprint "eagle-import:C0603")
      (libsource (lib "eagle-import") (part "rcl-modified-footprints_C-EUC0603"))
    )
    (comp (ref "C20")
      (value "CAP CER 0.1UF 25V X7R 0603 10%")
      (footprint "eagle-import:C0603")
      (libsource (lib "eagle-import") (part "rcl-modified-footprints_C-EUC0603"))
    )
    (comp (ref "C22")
      (value "CAP CER 4.7UF 6.3V X7R 0603 10%")
      (footprint "eagle-import:C0603")
      (libsource (lib "eagle-import") (part "rcl-modified-footprints_C-EUC0603"))
    )
    (comp (ref "C102")
      (value "CAP CER 0.1UF 25V X7R 0603 10%")
      (footprint "eagle-import:C0603")
      (libsource (lib "eagle-import") (part "C-EUC0603"))
    )
    (comp (ref "C103")
      (value "CAP CER 4.7UF 6.3V X7R 0603 10%")
      (footprint "eagle-import:C0603")
      (libsource (lib "eagle-import") (part "C-EUC0603"))
    )
    (comp (ref "C110")
      (value "CAP CER 0.1UF 25V X7R 0603 10%")
      (footprint "eagle-import:C0603")
      (libsource (lib "eagle-import") (part "C-EUC0603"))
    )
    (comp (ref "IC31")
      (value "MAX5725")
      (footprint "eagle-import:TSSOP20")
      (libsource (lib "eagle-import") (part "MAX572X"))
    )
    (comp (ref "L4")
      (value "PE-0603FB601ST")
      (footprint "eagle-import:R0603")
      (libsource (lib "eagle-import") (part "INDUCTOR0603"))
    )
    (comp (ref "L9")
      (value "PE-0603FB601ST")
      (footprint "eagle-import:R0603")
      (libsource (lib "eagle-import") (part "INDUCTOR0603"))
    )
    (comp (ref "R12")
      (value "RES SMD 2.2K OHM 1% 1/10W 0603")
      (footprint "eagle-import:R0603")
      (libsource (lib "eagle-import") (part "rcl-modified-footprints_R-EU_R0603"))
    )
    (comp (ref "R13")
      (value "RES SMD 2.2K OHM 1% 1/10W 0603")
      (footprint "eagle-import:R0603")
      (libsource (lib "eagle-import") (part "rcl-modified-footprints_R-EU_R0603"))
    )
    (comp (ref "R17")
      (value "DNP")
      (footprint "eagle-import:R0603")
      (libsource (lib "eagle-import") (part "rcl-modified-footprints_R-EU_R0603"))
    )
    (comp (ref "R18")
      (value "RES SMD 1K OHM 1% 1/10W 0603")
      (footprint "eagle-import:R0603")
      (libsource (lib "eagle-import") (part "rcl-modified-footprints_R-EU_R0603"))
    )
    (comp (ref "R19")
      (value "DNP")
      (footprint "eagle-import:R0603")
      (libsource (lib "eagle-import") (part "rcl-modified-footprints_R-EU_R0603"))
    )
    (comp (ref "R73")
      (value "RES SMD 0 OHM JUMPER 0603")
      (footprint "eagle-import:R0603")
      (libsource (lib "eagle-import") (part "R-EU_R0603"))
    )
    (comp (ref "TP5")
      (value "GND")
      (footprint "eagle-import:KEYSTONE_5000_MINIATURE")
      (libsource (lib "eagle-import") (part "KEYSTONE_5000"))
    )
    (comp (ref "TP6")
      (value "VREF_AV_DET")
      (footprint "eagle-import:KEYSTONE_5000_MINIATURE")
      (libsource (lib "eagle-import") (part "KEYSTONE_5000"))
    )
    (comp (ref "TP14")
      (value "DELTA_V")
      (footprint "eagle-import:KEYSTONE_5000_MINIATURE")
      (libsource (lib "eagle-import") (part "KEYSTONE_5000"))
    )
    (comp (ref "TP15")
      (value "DMND_IBIAS")
      (footprint "eagle-import:KEYSTONE_5000_MINIATURE")
      (libsource (lib "eagle-import") (part "KEYSTONE_5000"))
    )
    (comp (ref "TP16")
      (value "OS_COMP")
      (footprint "eagle-import:KEYSTONE_5000_MINIATURE")
      (libsource (lib "eagle-import") (part "KEYSTONE_5000"))
    )
    (comp (ref "TP17")
      (value "V_A")
      (footprint "eagle-import:KEYSTONE_5000_MINIATURE")
      (libsource (lib "eagle-import") (part "KEYSTONE_5000"))
    )
    (comp (ref "TP18")
      (value "OS_CCS")
      (footprint "eagle-import:KEYSTONE_5000_MINIATURE")
      (libsource (lib "eagle-import") (part "KEYSTONE_5000"))
    )
    (comp (ref "TP19")
      (value "EXTRA_1")
      (footprint "eagle-import:KEYSTONE_5000_MINIATURE")
      (libsource (lib "eagle-import") (part "KEYSTONE_5000"))
    )
    (comp (ref "TP20")
      (value "EXTRA_2")
      (footprint "eagle-import:KEYSTONE_5000_MINIATURE")
      (libsource (lib "eagle-import") (part "KEYSTONE_5000"))
    )
    (comp (ref "TP21")
      (value "EXTRA_3")
      (footprint "eagle-import:KEYSTONE_5000_MINIATURE")
      (libsource (lib "eagle-import") (part "KEYSTONE_5000"))
    )
    (comp (ref "TP22")
      (value "GND")
      (footprint "eagle-import:KEYSTONE_5000_MINIATURE")
      (libsource (lib "eagle-import") (part "KEYSTONE_5000"))
    )
    (comp (ref "U1")
      (value "MCP4725")
      (footprint "eagle-import:SOT23-6")
      (libsource (lib "eagle-import") (part "DAC_MCP4725"))
    )
    (comp (ref "C29")
      (value "CAP CER 0.1UF 10V X7R 0402 10%")
      (footprint "eagle-import:C0402")
      (libsource (lib "eagle-import") (part "rcl-modified-footprints_C-EUC0402"))
    )
    (comp (ref "C30")
      (value "CAP CER 10000PF 10V X7R 0402 10%")
      (footprint "eagle-import:C0402")
      (libsource (lib "eagle-import") (part "rcl-modified-footprints_C-EUC0402"))
    )
    (comp (ref "C88")
      (value "CAP CER 0.1UF 25V X7R 0603 10%")
      (footprint "eagle-import:C0603")
      (libsource (lib "eagle-import") (part "rcl-modified-footprints_C-EUC0603"))
    )
    (comp (ref "C94")
      (value "CAP CER 0.1UF 25V X7R 0603 10%")
      (footprint "eagle-import:C0603")
      (libsource (lib "eagle-import") (part "rcl-modified-footprints_C-EUC0603"))
    )
    (comp (ref "C100")
      (value "CAP CER 0.1UF 25V X7R 0603 10%")
      (footprint "eagle-import:C0603")
      (libsource (lib "eagle-import") (part "C-EUC0603"))
    )
    (comp (ref "IC5")
      (value "HFA3134")
      (footprint "eagle-import:SOT23-6L")
      (libsource (lib "eagle-import") (part "HFA3134"))
    )
    (comp (ref "IC23")
      (value "HFA3134")
      (footprint "eagle-import:SOT23-6L")
      (libsource (lib "eagle-import") (part "HFA3134"))
    )
    (comp (ref "IC25")
      (value "THAT320")
      (footprint "eagle-import:SO14")
      (libsource (lib "eagle-import") (part "THAT320"))
    )
    (comp (ref "IC26")
      (value "TLV272DGK")
      (footprint "eagle-import:MSOP8")
      (libsource (lib "eagle-import") (part "TLV272DGK"))
    )
    (comp (ref "IC27")
      (value "HFA3134")
      (footprint "eagle-import:SOT23-6L")
      (libsource (lib "eagle-import") (part "HFA3134"))
    )
    (comp (ref "IC28")
      (value "TLV271DBV")
      (footprint "eagle-import:SOT23-5")
      (libsource (lib "eagle-import") (part "TLV271DBV"))
    )
    (comp (ref "R50")
      (value "RES SMD 110 OHM 1% 1/10W 0603")
      (footprint "eagle-import:R0603")
      (libsource (lib "eagle-import") (part "rcl-modified-footprints_R-EU_R0603"))
    )
    (comp (ref "R59")
      (value "RES SMD 127K OHM 1% 1/10W 0603")
      (footprint "eagle-import:R0603")
      (libsource (lib "eagle-import") (part "rcl-modified-footprints_R-EU_R0603"))
    )
    (comp (ref "R63")
      (value "RES SMD 274 OHM 1% 1/10W 0603")
      (footprint "eagle-import:R0603")
      (libsource (lib "eagle-import") (part "rcl-modified-footprints_R-EU_R0603"))
    )
    (comp (ref "R64")
      (value "RES SMD 102K OHM 1% 1/10W 0603")
      (footprint "eagle-import:R0603")
      (libsource (lib "eagle-import") (part "rcl-modified-footprints_R-EU_R0603"))
    )
    (comp (ref "R68")
      (value "SOT-DIV23LF-03-1001-1001-BB")
      (footprint "eagle-import:SOT23C")
      (libsource (lib "eagle-import") (part "DIVIDER_SOT23-5"))
    )
    (comp (ref "C40")
      (value "CAP CER 10000PF 10V X7R 0402 10%")
      (footprint "eagle-import:C0402")
      (libsource (lib "eagle-import") (part "rcl-modified-footprints_C-EUC0402"))
    )
    (comp (ref "C47")
      (value "CAP CER 10000PF 10V X7R 0402 10%")
      (footprint "eagle-import:C0402")
      (libsource (lib "eagle-import") (part "rcl-modified-footprints_C-EUC0402"))
    )
    (comp (ref "C50")
      (value "CAP CER 10000PF 10V X7R 0402 10%")
      (footprint "eagle-import:C0402")
      (libsource (lib "eagle-import") (part "rcl-modified-footprints_C-EUC0402"))
    )
    (comp (ref "C51")
      (value "CAP CER 100PF 25V C0G/NP0 0402")
      (footprint "eagle-import:C0402")
      (libsource (lib "eagle-import") (part "rcl-modified-footprints_C-EUC0402"))
    )
    (comp (ref "C52")
      (value "CAP CER 10000PF 25V X7R 0603 10%")
      (footprint "eagle-import:C0603")
      (libsource (lib "eagle-import") (part "rcl-modified-footprints_C-EUC0603"))
    )
    (comp (ref "C75")
      (value "CAP CER 10000PF 25V X7R 0603 10%")
      (footprint "eagle-import:C0603")
      (libsource (lib "eagle-import") (part "rcl-modified-footprints_C-EUC0603"))
    )
    (comp (ref "C76")
      (value "CAP CER 0.1UF 25V X7R 0603 10%")
      (footprint "eagle-import:C0603")
      (libsource (lib "eagle-import") (part "rcl-modified-footprints_C-EUC0603"))
    )
    (comp (ref "C113")
      (value "CAP CER 0.1UF 25V X7R 0603 10%")
      (footprint "eagle-import:C0603")
      (libsource (lib "eagle-import") (part "C-EUC0603"))
    )
    (comp (ref "D3")
      (value "DF2B29FU,H3F")
      (footprint "eagle-import:SOD523")
      (libsource (lib "eagle-import") (part "diode_210_DIODE-SOD523"))
    )
    (comp (ref "D4")
      (value "BAS40")
      (footprint "eagle-import:SOT23")
      (libsource (lib "eagle-import") (part "BAS40"))
    )
    (comp (ref "D5")
      (value "BAS40")
      (footprint "eagle-import:SOT23")
      (libsource (lib "eagle-import") (part "BAS40"))
    )
    (comp (ref "IC6")
      (value "HFA3135")
      (footprint "eagle-import:SOT23-6L")
      (libsource (lib "eagle-import") (part "HFA3135"))
    )
    (comp (ref "IC8")
      (value "HFA3135")
      (footprint "eagle-import:SOT23-6L")
      (libsource (lib "eagle-import") (part "HFA3135"))
    )
    (comp (ref "IC11")
      (value "HFA3134")
      (footprint "eagle-import:SOT23-6L")
      (libsource (lib "eagle-import") (part "HFA3134"))
    )
    (comp (ref "IC12")
      (value "HFA3134")
      (footprint "eagle-import:SOT23-6L")
      (libsource (lib "eagle-import") (part "HFA3134"))
    )
    (comp (ref "IC13")
      (value "HFA3134")
      (footprint "eagle-import:SOT23-6L")
      (libsource (lib "eagle-import") (part "HFA3134"))
    )
    (comp (ref "M1")
      (value "BSS806N")
      (footprint "eagle-import:SOT23R_INFINEON")
      (libsource (lib "eagle-import") (part "BSS806N"))
    )
    (comp (ref "M2")
      (value "BSS806N")
      (footprint "eagle-import:SOT23R_INFINEON")
      (libsource (lib "eagle-import") (part "BSS806N"))
    )
    (comp (ref "R23")
      (value "RES SMD 220 OHM 1% 1/10W 0603")
      (footprint "eagle-import:R0603")
      (libsource (lib "eagle-import") (part "rcl-modified-footprints_R-EU_R0603"))
    )
    (comp (ref "R35")
      (value "RES SMD 49.9 OHM 1% 1/10W 0402")
      (footprint "eagle-import:R0402")
      (libsource (lib "eagle-import") (part "rcl-modified-footprints_R-EU_R0402"))
    )
    (comp (ref "R37")
      (value "RES SMD 100 OHM 1% 1/8W 0603")
      (footprint "eagle-import:R0603")
      (libsource (lib "eagle-import") (part "rcl-modified-footprints_R-EU_R0603"))
    )
    (comp (ref "R38")
      (value "RES SMD 200 OHM 1% 1/10W 0603")
      (footprint "eagle-import:R0603")
      (libsource (lib "eagle-import") (part "rcl-modified-footprints_R-EU_R0603"))
    )
    (comp (ref "R39")
      (value "RES SMD 200 OHM 1% 1/10W 0603")
      (footprint "eagle-import:R0603")
      (libsource (lib "eagle-import") (part "rcl-modified-footprints_R-EU_R0603"))
    )
    (comp (ref "R42")
      (value "RES SMD 100 OHM 1% 1/8W 0603")
      (footprint "eagle-import:R0603")
      (libsource (lib "eagle-import") (part "rcl-modified-footprints_R-EU_R0603"))
    )
    (comp (ref "R46")
      (value "RES SMD 220 OHM 1% 1/10W 0603")
      (footprint "eagle-import:R0603")
      (libsource (lib "eagle-import") (part "rcl-modified-footprints_R-EU_R0603"))
    )
    (comp (ref "R75")
      (value "RES SMD 100 OHM 1% 1/8W 0603")
      (footprint "eagle-import:R0603")
      (libsource (lib "eagle-import") (part "R-EU_R0603"))
    )
    (comp (ref "R76")
      (value "RES SMD 100 OHM 1% 1/8W 0603")
      (footprint "eagle-import:R0603")
      (libsource (lib "eagle-import") (part "R-EU_R0603"))
    )
    (comp (ref "RLY1")
      (value "CRF05-1A")
      (footprint "eagle-import:MEDER_RELAY_CRF")
      (libsource (lib "eagle-import") (part "MEDER_CRF05-1A"))
    )
    (comp (ref "RLY2")
      (value "CRF05-1A")
      (footprint "eagle-import:MEDER_RELAY_CRF")
      (libsource (lib "eagle-import") (part "MEDER_CRF05-1A"))
    )
    (comp (ref "TP9")
      (value "TP_VSCOPE")
      (footprint "eagle-import:JOHNSON-129-0701-30X")
      (libsource (lib "eagle-import") (part "TP-SCOPE_H"))
    )
    (comp (ref "X1")
      (value "CONN_PULLDN_SENSE")
      (footprint "eagle-import:J502-ND-142-0701-881_886")
      (fields
        (field (name "MF") "JOHNSON COMPONENTS")
        (field (name "MPN") "142-0701-881")
        (field (name "MF_1") "JOHNSON COMPONENTS")
        (field (name "MPN_1") "142-0711-871")
        (field (name "OC_FARNELL") "unknown")
        (field (name "OC_NEWARK") "01C1639")
      )
      (libsource (lib "eagle-import") (part "SMA-142-0701-881/886"))
    )
    (comp (ref "X4")
      (value "CONN_SPAD")
      (footprint "eagle-import:J502-ND-142-0701-881_886")
      (fields (field (name "MF") "JOHNSON COMPONENTS") (field (name "MPN") "142-0701-881"))
      (libsource (lib "eagle-import") (part "SMA-142-0701-881/886"))
    )
    (comp (ref "X7")
      (value "CONN_SMU")
      (footprint "eagle-import:J502-ND-142-0701-881_886")
      (fields (field (name "MF") "JOHNSON COMPONENTS") (field (name "MPN") "142-0701-881"))
      (libsource (lib "eagle-import") (part "SMA-142-0701-881/886"))
    )
    (comp (ref "C27")
      (value "CAP CER 10UF 10V X7R 1206 10%")
      (footprint "eagle-import:C1206")
      (libsource (lib "eagle-import") (part "C-EUC1206"))
    )
    (comp (ref "C31")
      (value "CAP CER 10000PF 25V X7R 0603 10%")
      (footprint "eagle-import:C0603")
      (libsource (lib "eagle-import") (part "C-EUC0603"))
    )
    (comp (ref "C32")
      (value "CAP CER 1300PF 50V C0G 0603 5%")
      (footprint "eagle-import:C0603")
      (libsource (lib "eagle-import") (part "C-EUC0603"))
    )
    (comp (ref "C42")
      (value "CAP ALUM POLY 68UF 20% 16V SMD")
      (footprint "eagle-import:CT7343")
      (libsource (lib "eagle-import") (part "CPOL-EUCT7343"))
    )
    (comp (ref "C45")
      (value "CAP CER 4.7UF 25V X7R 0805 10%")
      (footprint "eagle-import:C0805")
      (libsource (lib "eagle-import") (part "C-EUC0805"))
    )
    (comp (ref "C56")
      (value "CAP CER 10UF 16V X7R 0805 20%")
      (footprint "eagle-import:C0805")
      (libsource (lib "eagle-import") (part "C-EUC0805"))
    )
    (comp (ref "C57")
      (value "CAP CER 4.7UF 25V X7R 0805 10%")
      (footprint "eagle-import:C0805")
      (libsource (lib "eagle-import") (part "C-EUC0805"))
    )
    (comp (ref "C67")
      (value "CAP CER 0.1UF 25V X7R 0603 10%")
      (footprint "eagle-import:C0603")
      (libsource (lib "eagle-import") (part "C-EUC0603"))
    )
    (comp (ref "C68")
      (value "CAP CER 0.033UF 50V X7R 0603 10%")
      (footprint "eagle-import:C0603")
      (libsource (lib "eagle-import") (part "C-EUC0603"))
    )
    (comp (ref "C69")
      (value "DNP")
      (footprint "eagle-import:C0603")
      (libsource (lib "eagle-import") (part "C-EUC0603"))
    )
    (comp (ref "C71")
      (value "DNP")
      (footprint "eagle-import:C0603")
      (libsource (lib "eagle-import") (part "C-EUC0603"))
    )
    (comp (ref "D2")
      (value "CDBA140SL-HF")
      (footprint "eagle-import:DO214AC")
      (libsource (lib "eagle-import") (part "DIODE-DO214AC"))
    )
    (comp (ref "IC10")
      (value "LT1534-1")
      (footprint "eagle-import:SO16")
      (libsource (lib "eagle-import") (part "LT1534"))
    )
    (comp (ref "L5")
      (value "25n")
      (footprint "eagle-import:R0603")
      (libsource (lib "eagle-import") (part "INDUCTOR0603"))
    )
    (comp (ref "L6")
      (value "SRF0703-820M")
      (footprint "eagle-import:SRF0703")
      (libsource (lib "eagle-import") (part "SRF0703"))
    )
    (comp (ref "R29")
      (value "RES SMD 100 OHM 1% 1/8W 0603")
      (footprint "eagle-import:R0603")
      (libsource (lib "eagle-import") (part "resistor_R-EU_R0603"))
    )
    (comp (ref "R30")
      (value "RES SMD 16.9K OHM 1% 1/10W 0603")
      (footprint "eagle-import:R0603")
      (libsource (lib "eagle-import") (part "R-EU_R0603"))
    )
    (comp (ref "R41")
      (value "RES SMD 1.4K OHM 1% 1/10W 0603")
      (footprint "eagle-import:R0603")
      (libsource (lib "eagle-import") (part "resistor_R-EU_R0603"))
    )
    (comp (ref "R43")
      (value "RES SMD 1K OHM 1% 1/10W 0603")
      (footprint "eagle-import:R0603")
      (libsource (lib "eagle-import") (part "resistor_R-EU_R0603"))
    )
    (comp (ref "R44")
      (value "RES SMD 1K OHM 1% 1/10W 0603")
      (footprint "eagle-import:R0603")
      (libsource (lib "eagle-import") (part "resistor_R-EU_R0603"))
    )
    (comp (ref "R45")
      (value "RES SMD 2K OHM 1% 1/10W 0603")
      (footprint "eagle-import:R0603")
      (libsource (lib "eagle-import") (part "R-EU_R0603"))
    )
    (comp (ref "R48")
      (value "RES SMD 1K OHM 1% 1/10W 0603")
      (footprint "eagle-import:R0603")
      (libsource (lib "eagle-import") (part "resistor_R-EU_R0603"))
    )
    (comp (ref "TP8")
      (value "TPB1,27")
      (footprint "eagle-import:B1,27")
      (libsource (lib "eagle-import") (part "TPB1,27"))
    )
    (comp (ref "TP10")
      (value "TPB1,27")
      (footprint "eagle-import:B1,27")
      (libsource (lib "eagle-import") (part "TPB1,27"))
    )
    (comp (ref "C26")
      (value "CAP ALUM POLY 47UF 20% 20V SMD")
      (footprint "eagle-import:CT7343")
      (libsource (lib "eagle-import") (part "CPOL-EUCT7343"))
    )
    (comp (ref "C79")
      (value "CAP CER 0.1UF 25V X7R 0603 10%")
      (footprint "eagle-import:C0603")
      (libsource (lib "eagle-import") (part "C-EUC0603"))
    )
    (comp (ref "C95")
      (value "CAP CER 0.1UF 10V X7R 0402 10%")
      (footprint "eagle-import:C0402")
      (libsource (lib "eagle-import") (part "C-EUC0402"))
    )
    (comp (ref "C97")
      (value "CAP CER 10000PF 10V X7R 0402 10%")
      (footprint "eagle-import:C0402")
      (libsource (lib "eagle-import") (part "C-EUC0402"))
    )
    (comp (ref "C98")
      (value "CAP CER 47PF 16V C0G 0402 5%")
      (footprint "eagle-import:C0402")
      (libsource (lib "eagle-import") (part "C-EUC0402"))
    )
    (comp (ref "C101")
      (value "CAP CER 47PF 16V C0G 0402 5%")
      (footprint "eagle-import:C0402")
      (libsource (lib "eagle-import") (part "C-EUC0402"))
    )
    (comp (ref "C105")
      (value "CAP CER 10000PF 25V X7R 0603 10%")
      (footprint "eagle-import:C0603")
      (libsource (lib "eagle-import") (part "C-EUC0603"))
    )
    (comp (ref "C106")
      (value "CAP CER 0.1UF 25V X7R 0603 10%")
      (footprint "eagle-import:C0603")
      (libsource (lib "eagle-import") (part "C-EUC0603"))
    )
    (comp (ref "C107")
      (value "CAP CER 0.1UF 25V X7R 0603 10%")
      (footprint "eagle-import:C0603")
      (libsource (lib "eagle-import") (part "C-EUC0603"))
    )
    (comp (ref "C108")
      (value "CAP CER 4.7UF 6.3V X7R 0603 10%")
      (footprint "eagle-import:C0603")
      (libsource (lib "eagle-import") (part "C-EUC0603"))
    )
    (comp (ref "H1")
      (value "MOUNT-PAD-ROUND3.2")
      (footprint "eagle-import:3,2-PAD")
      (libsource (lib "eagle-import") (part "MOUNT-PAD-ROUND3.2"))
    )
    (comp (ref "H2")
      (value "MOUNT-PAD-ROUND3.2")
      (footprint "eagle-import:3,2-PAD")
      (libsource (lib "eagle-import") (part "MOUNT-PAD-ROUND3.2"))
    )
    (comp (ref "H3")
      (value "MOUNT-PAD-ROUND3.2")
      (footprint "eagle-import:3,2-PAD")
      (libsource (lib "eagle-import") (part "MOUNT-PAD-ROUND3.2"))
    )
    (comp (ref "H4")
      (value "MOUNT-PAD-ROUND3.2")
      (footprint "eagle-import:3,2-PAD")
      (libsource (lib "eagle-import") (part "MOUNT-PAD-ROUND3.2"))
    )
    (comp (ref "IC29")
      (value "USBLC6-2SC6Y")
      (footprint "eagle-import:SOT23-6L")
      (libsource (lib "eagle-import") (part "USBLC6"))
    )
    (comp (ref "IC32")
      (value "LM1117")
      (footprint "eagle-import:SOT-223")
      (libsource (lib "eagle-import") (part "LM1117"))
    )
    (comp (ref "L8")
      (value "MI0805J102R-10")
      (footprint "eagle-import:R0805")
      (libsource (lib "eagle-import") (part "INDUCTOR0805"))
    )
    (comp (ref "L10")
      (value "MI0805J102R-10")
      (footprint "eagle-import:R0805")
      (libsource (lib "eagle-import") (part "INDUCTOR0805"))
    )
    (comp (ref "Q1")
      (value "DMG2305UX-13")
      (footprint "eagle-import:SOT23-WIDE")
      (libsource (lib "eagle-import") (part "MOSFET-PWIDE"))
    )
    (comp (ref "R58")
      (value "RES SMD 4.7K OHM 1% 1/10W 0603")
      (footprint "eagle-import:R0603")
      (libsource (lib "eagle-import") (part "resistor_R-EU_R0603"))
    )
    (comp (ref "R62")
      (value "RES SMD 100K OHM 1% 1/10W 0603")
      (footprint "eagle-import:R0603")
      (libsource (lib "eagle-import") (part "resistor_R-EU_R0603"))
    )
    (comp (ref "R67")
      (value "RES SMD 22 OHM 1% 1/10W 0402")
      (footprint "eagle-import:R0402")
      (libsource (lib "eagle-import") (part "resistor_R-EU_R0402"))
    )
    (comp (ref "R70")
      (value "RES SMD 22 OHM 1% 1/10W 0402")
      (footprint "eagle-import:R0402")
      (libsource (lib "eagle-import") (part "resistor_R-EU_R0402"))
    )
    (comp (ref "TP23")
      (value "TPTP15R")
      (footprint "eagle-import:TP15R")
      (libsource (lib "eagle-import") (part "TPTP15R"))
    )
    (comp (ref "X3")
      (value "KEYSTONE-7774")
      (footprint "eagle-import:KEYSTONE-7774")
      (libsource (lib "eagle-import") (part "KEYSTONE-7774"))
    )
    (comp (ref "X6")
      (value "KEYSTONE-7774")
      (footprint "eagle-import:KEYSTONE-7774")
      (libsource (lib "eagle-import") (part "KEYSTONE-7774"))
    )
    (comp (ref "X8")
      (value "61729-0010BLF")
      (footprint "eagle-import:PN61729-S")
      (libsource (lib "eagle-import") (part "PN61729-S"))
    )
    (comp (ref "C1")
      (value "CAP CER 10000PF 25V X7R 0603 10%")
      (footprint "eagle-import:C0603")
      (libsource (lib "eagle-import") (part "rcl-modified-footprints_C-EUC0603"))
    )
    (comp (ref "C2")
      (value "CAP CER 10000PF 25V X7R 0603 10%")
      (footprint "eagle-import:C0603")
      (libsource (lib "eagle-import") (part "rcl-modified-footprints_C-EUC0603"))
    )
    (comp (ref "C5")
      (value "CAP CER 10000PF 25V X7R 0603 10%")
      (footprint "eagle-import:C0603")
      (libsource (lib "eagle-import") (part "rcl-modified-footprints_C-EUC0603"))
    )
    (comp (ref "C6")
      (value "CAP CER 10000PF 25V X7R 0603 10%")
      (footprint "eagle-import:C0603")
      (libsource (lib "eagle-import") (part "rcl-modified-footprints_C-EUC0603"))
    )
    (comp (ref "C7")
      (value "CAP CER 0.1UF 25V X7R 0603 10%")
      (footprint "eagle-import:C0603")
      (libsource (lib "eagle-import") (part "rcl-modified-footprints_C-EUC0603"))
    )
    (comp (ref "C8")
      (value "CAP CER 0.1UF 25V X7R 0603 10%")
      (footprint "eagle-import:C0603")
      (libsource (lib "eagle-import") (part "rcl-modified-footprints_C-EUC0603"))
    )
    (comp (ref "C9")
      (value "CAP CER 0.1UF 25V X7R 0603 10%")
      (footprint "eagle-import:C0603")
      (libsource (lib "eagle-import") (part "rcl-modified-footprints_C-EUC0603"))
    )
    (comp (ref "C10")
      (value "CAP CER 0.1UF 25V X7R 0603 10%")
      (footprint "eagle-import:C0603")
      (libsource (lib "eagle-import") (part "rcl-modified-footprints_C-EUC0603"))
    )
    (comp (ref "C11")
      (value "CAP CER 10UF 25V X5R 0805 10%")
      (footprint "eagle-import:C0805")
      (libsource (lib "eagle-import") (part "C-EUC0805"))
    )
    (comp (ref "C12")
      (value "CAP CER 10UF 16V X7R 0805 20%")
      (footprint "eagle-import:C0805")
      (libsource (lib "eagle-import") (part "C-EUC0805"))
    )
    (comp (ref "C39")
      (value "CAP CER 10UF 16V X7R 0805 20%")
      (footprint "eagle-import:C0805")
      (libsource (lib "eagle-import") (part "C-EUC0805"))
    )
    (comp (ref "C41")
      (value "CAP CER 10000PF 25V X7R 0603 10%")
      (footprint "eagle-import:C0603")
      (libsource (lib "eagle-import") (part "rcl-modified-footprints_C-EUC0603"))
    )
    (comp (ref "C46")
      (value "CAP CER 0.1UF 25V X7R 0603 10%")
      (footprint "eagle-import:C0603")
      (libsource (lib "eagle-import") (part "rcl-modified-footprints_C-EUC0603"))
    )
    (comp (ref "C53")
      (value "CAP CER 0.1UF 25V X7R 0603 10%")
      (footprint "eagle-import:C0603")
      (libsource (lib "eagle-import") (part "rcl-modified-footprints_C-EUC0603"))
    )
    (comp (ref "C54")
      (value "CAP CER 10000PF 25V X7R 0603 10%")
      (footprint "eagle-import:C0603")
      (libsource (lib "eagle-import") (part "rcl-modified-footprints_C-EUC0603"))
    )
    (comp (ref "IC1")
      (value "TPS7A4901")
      (footprint "eagle-import:MSOP-8_POWER_PAD")
      (libsource (lib "eagle-import") (part "TPS7A"))
    )
    (comp (ref "IC2")
      (value "TPS7A4901")
      (footprint "eagle-import:MSOP-8_POWER_PAD")
      (libsource (lib "eagle-import") (part "TPS7A"))
    )
    (comp (ref "IC9")
      (value "TPS7A3001")
      (footprint "eagle-import:MSOP-8_POWER_PAD")
      (libsource (lib "eagle-import") (part "TPS7A"))
    )
    (comp (ref "R1")
      (value "RES SMD 24K OHM 1% 1/10W 0603")
      (footprint "eagle-import:R0603")
      (libsource (lib "eagle-import") (part "rcl-modified-footprints_R-EU_R0603"))
    )
    (comp (ref "R2")
      (value "RES SMD 11.8K OHM 1% 1/10W 0603")
      (footprint "eagle-import:R0603")
      (libsource (lib "eagle-import") (part "rcl-modified-footprints_R-EU_R0603"))
    )
    (comp (ref "R10")
      (value "RES SMD 76.8K OHM 1% 1/10W 0603")
      (footprint "eagle-import:R0603")
      (libsource (lib "eagle-import") (part "rcl-modified-footprints_R-EU_R0603"))
    )
    (comp (ref "R11")
      (value "RES SMD 137K OHM 1% 1/10W 0603")
      (footprint "eagle-import:R0603")
      (libsource (lib "eagle-import") (part "rcl-modified-footprints_R-EU_R0603"))
    )
    (comp (ref "R32")
      (value "RES SMD 76.8K OHM 1% 1/10W 0603")
      (footprint "eagle-import:R0603")
      (libsource (lib "eagle-import") (part "rcl-modified-footprints_R-EU_R0603"))
    )
    (comp (ref "R34")
      (value "RES SMD 24K OHM 1% 1/10W 0603")
      (footprint "eagle-import:R0603")
      (libsource (lib "eagle-import") (part "rcl-modified-footprints_R-EU_R0603"))
    )
    (comp (ref "TP1")
      (value "TPTP15R")
      (footprint "eagle-import:TP15R")
      (libsource (lib "eagle-import") (part "TPTP15R"))
    )
    (comp (ref "TP3")
      (value "TPTP15R")
      (footprint "eagle-import:TP15R")
      (libsource (lib "eagle-import") (part "TPTP15R"))
    )
    (comp (ref "TP4")
      (value "TPTP15R")
      (footprint "eagle-import:TP15R")
      (libsource (lib "eagle-import") (part "TPTP15R"))
    )
    (comp (ref "TP11")
      (value "TPTP15R")
      (footprint "eagle-import:TP15R")
      (libsource (lib "eagle-import") (part "TPTP15R"))
    )
    (comp (ref "C82")
      (value "CAP CER 10000PF 25V X7R 0603 10%")
      (footprint "eagle-import:C0603")
      (libsource (lib "eagle-import") (part "C-EUC0603"))
    )
    (comp (ref "C86")
      (value "CAP CER 4.7UF 6.3V X7R 0603 10%")
      (footprint "eagle-import:C0603")
      (libsource (lib "eagle-import") (part "C-EUC0603"))
    )
    (comp (ref "C87")
      (value "CAP CER 4.7UF 6.3V X7R 0603 10%")
      (footprint "eagle-import:C0603")
      (libsource (lib "eagle-import") (part "C-EUC0603"))
    )
    (comp (ref "C91")
      (value "CAP CER 0.1UF 25V X7R 0603 10%")
      (footprint "eagle-import:C0603")
      (libsource (lib "eagle-import") (part "C-EUC0603"))
    )
    (comp (ref "C92")
      (value "CAP CER 0.1UF 25V X7R 0603 10%")
      (footprint "eagle-import:C0603")
      (libsource (lib "eagle-import") (part "C-EUC0603"))
    )
    (comp (ref "C96")
      (value "CAP CER 0.1UF 25V X7R 0603 10%")
      (footprint "eagle-import:C0603")
      (libsource (lib "eagle-import") (part "rcl-modified-footprints_C-EUC0603"))
    )
    (comp (ref "C99")
      (value "CAP CER 0.1UF 25V X7R 0603 10%")
      (footprint "eagle-import:C0603")
      (libsource (lib "eagle-import") (part "rcl-modified-footprints_C-EUC0603"))
    )
    (comp (ref "C104")
      (value "CAP CER 0.1UF 25V X7R 0603 10%")
      (footprint "eagle-import:C0603")
      (libsource (lib "eagle-import") (part "rcl-modified-footprints_C-EUC0603"))
    )
    (comp (ref "C109")
      (value "CAP CER 0.1UF 25V X7R 0603 10%")
      (footprint "eagle-import:C0603")
      (libsource (lib "eagle-import") (part "rcl-modified-footprints_C-EUC0603"))
    )
    (comp (ref "C111")
      (value "CAP CER 0.1UF 25V X7R 0603 10%")
      (footprint "eagle-import:C0603")
      (libsource (lib "eagle-import") (part "C-EUC0603"))
    )
    (comp (ref "C112")
      (value "CAP CER 0.1UF 25V X7R 0603 10%")
      (footprint "eagle-import:C0603")
      (libsource (lib "eagle-import") (part "C-EUC0603"))
    )
    (comp (ref "IC30")
      (value "STM32F411RE")
      (footprint "eagle-import:TQFP64_STM32")
      (libsource (lib "eagle-import") (part "STM32F405RG"))
    )
    (comp (ref "L7")
      (value "PE-0603FB601ST")
      (footprint "eagle-import:R0603")
      (libsource (lib "eagle-import") (part "INDUCTOR0603"))
    )
    (comp (ref "LED1")
      (value "Dialight-5640200132F")
      (footprint "eagle-import:CBI-564-0X00-XXX")
      (libsource (lib "eagle-import") (part "CBI-564-0X00-XXX-3LED"))
    )
    (comp (ref "PROG")
      (value "JST_VERT")
      (footprint "eagle-import:JST-6-SMD-VERT-1.0MM")
      (libsource (lib "eagle-import") (part "JST_VERTICAL"))
    )
    (comp (ref "R55")
      (value "RES SMD 470 OHM 1% 1/10W 0603")
      (footprint "eagle-import:R0603")
      (libsource (lib "eagle-import") (part "resistor_R-EU_R0603"))
    )
    (comp (ref "R60")
      (value "RES SMD 470 OHM 1% 1/10W 0603")
      (footprint "eagle-import:R0603")
      (libsource (lib "eagle-import") (part "resistor_R-EU_R0603"))
    )
    (comp (ref "R65")
      (value "RES SMD 470 OHM 1% 1/10W 0603")
      (footprint "eagle-import:R0603")
      (libsource (lib "eagle-import") (part "resistor_R-EU_R0603"))
    )
    (comp (ref "R66")
      (value "DNP")
      (footprint "eagle-import:R0603")
      (libsource (lib "eagle-import") (part "rcl-modified-footprints_R-EU_R0603"))
    )
    (comp (ref "R69")
      (value "DNP")
      (footprint "eagle-import:R0603")
      (libsource (lib "eagle-import") (part "rcl-modified-footprints_R-EU_R0603"))
    )
    (comp (ref "R71")
      (value "RES SMD 0 OHM JUMPER 0603")
      (footprint "eagle-import:R0603")
      (libsource (lib "eagle-import") (part "rcl-modified-footprints_R-EU_R0603"))
    )
    (comp (ref "R72")
      (value "DNP")
      (footprint "eagle-import:R0603")
      (libsource (lib "eagle-import") (part "rcl-modified-footprints_R-EU_R0603"))
    )
    (comp (ref "R74")
      (value "RES SMD 0 OHM JUMPER 0603")
      (footprint "eagle-import:R0603")
      (libsource (lib "eagle-import") (part "rcl-modified-footprints_R-EU_R0603"))
    )
    (comp (ref "SW1")
      (value "MCU_RST")
      (footprint "eagle-import:E-SWITCH-TL3305AF160QG")
      (libsource (lib "eagle-import") (part "E-SWITCH-TL3305AF160QG"))
    )
    (comp (ref "XTAL1")
      (value "CSTCE8M00G15L99-R0")
      (footprint "eagle-import:CSTCE_G15L_CSTCE_GH5L")
      (libsource (lib "eagle-import") (part "MURATA_CSTCE_G15L/CSTCE_GH5L"))
    )
    (comp (ref "C21")
      (value "CAP CER 10000PF 10V X7R 0402 10%")
      (footprint "eagle-import:C0402")
      (libsource (lib "eagle-import") (part "rcl-modified-footprints_C-EUC0402"))
    )
    (comp (ref "C23")
      (value "CAP CER 0.1UF 10V X7R 0402 10%")
      (footprint "eagle-import:C0402")
      (libsource (lib "eagle-import") (part "rcl-modified-footprints_C-EUC0402"))
    )
    (comp (ref "C24")
      (value "CAP CER 10000PF 10V X7R 0402 10%")
      (footprint "eagle-import:C0402")
      (libsource (lib "eagle-import") (part "rcl-modified-footprints_C-EUC0402"))
    )
    (comp (ref "C28")
      (value "CAP CER 10000PF 10V X7R 0402 10%")
      (footprint "eagle-import:C0402")
      (libsource (lib "eagle-import") (part "rcl-modified-footprints_C-EUC0402"))
    )
    (comp (ref "C33")
      (value "CAP CER 0.1UF 10V X7R 0402 10%")
      (footprint "eagle-import:C0402")
      (libsource (lib "eagle-import") (part "rcl-modified-footprints_C-EUC0402"))
    )
    (comp (ref "C34")
      (value "CAP CER 10000PF 10V X7R 0402 10%")
      (footprint "eagle-import:C0402")
      (libsource (lib "eagle-import") (part "rcl-modified-footprints_C-EUC0402"))
    )
    (comp (ref "C35")
      (value "CAP CER 0.1UF 10V X7R 0402 10%")
      (footprint "eagle-import:C0402")
      (libsource (lib "eagle-import") (part "rcl-modified-footprints_C-EUC0402"))
    )
    (comp (ref "C36")
      (value "CAP CER 0.1UF 10V X7R 0402 10%")
      (footprint "eagle-import:C0402")
      (libsource (lib "eagle-import") (part "rcl-modified-footprints_C-EUC0402"))
    )
    (comp (ref "C37")
      (value "CAP CER 0.1UF 10V X7R 0402 10%")
      (footprint "eagle-import:C0402")
      (libsource (lib "eagle-import") (part "rcl-modified-footprints_C-EUC0402"))
    )
    (comp (ref "C38")
      (value "CAP CER 10000PF 10V X7R 0402 10%")
      (footprint "eagle-import:C0402")
      (libsource (lib "eagle-import") (part "rcl-modified-footprints_C-EUC0402"))
    )
    (comp (ref "C43")
      (value "CAP CER 0.1UF 10V X7R 0402 10%")
      (footprint "eagle-import:C0402")
      (libsource (lib "eagle-import") (part "rcl-modified-footprints_C-EUC0402"))
    )
    (comp (ref "C44")
      (value "CAP CER 10000PF 10V X7R 0402 10%")
      (footprint "eagle-import:C0402")
      (libsource (lib "eagle-import") (part "rcl-modified-footprints_C-EUC0402"))
    )
    (comp (ref "C48")
      (value "CAP CER 10000PF 10V X7R 0402 10%")
      (footprint "eagle-import:C0402")
      (libsource (lib "eagle-import") (part "rcl-modified-footprints_C-EUC0402"))
    )
    (comp (ref "C49")
      (value "CAP CER 0.1UF 10V X7R 0402 10%")
      (footprint "eagle-import:C0402")
      (libsource (lib "eagle-import") (part "rcl-modified-footprints_C-EUC0402"))
    )
    (comp (ref "IC4")
      (value "ADCMP582")
      (footprint "eagle-import:QFN50P300X300X80-16N")
      (libsource (lib "eagle-import") (part "ADCMP582"))
    )
    (comp (ref "IC7")
      (value "DS1100LU-45+")
      (footprint "eagle-import:MSOP8")
      (libsource (lib "eagle-import") (part "DS1100L"))
    )
    (comp (ref "R20")
      (value "RES SMD 49.9 OHM 1% 1/10W 0402")
      (footprint "eagle-import:R0402")
      (libsource (lib "eagle-import") (part "rcl-modified-footprints_R-EU_R0402"))
    )
    (comp (ref "R21")
      (value "DNP")
      (footprint "eagle-import:R0603")
      (libsource (lib "eagle-import") (part "rcl-modified-footprints_R-EU_R0603"))
    )
    (comp (ref "R22")
      (value "RES SMD 150 OHM 1% 1/10W 0402")
      (footprint "eagle-import:R0402")
      (libsource (lib "eagle-import") (part "rcl-modified-footprints_R-EU_R0402"))
    )
    (comp (ref "R24")
      (value "DNP")
      (footprint "eagle-import:R0603")
      (libsource (lib "eagle-import") (part "rcl-modified-footprints_R-EU_R0603"))
    )
    (comp (ref "R25")
      (value "DNP")
      (footprint "eagle-import:R0603")
      (libsource (lib "eagle-import") (part "rcl-modified-footprints_R-EU_R0603"))
    )
    (comp (ref "R26")
      (value "DNP")
      (footprint "eagle-import:R0603")
      (libsource (lib "eagle-import") (part "rcl-modified-footprints_R-EU_R0603"))
    )
    (comp (ref "R27")
      (value "DNP")
      (footprint "eagle-import:R0603")
      (libsource (lib "eagle-import") (part "rcl-modified-footprints_R-EU_R0603"))
    )
    (comp (ref "R28")
      (value "DNP")
      (footprint "eagle-import:R0603")
      (libsource (lib "eagle-import") (part "rcl-modified-footprints_R-EU_R0603"))
    )
    (comp (ref "R31")
      (value "RES SMD 150 OHM 1% 1/10W 0402")
      (footprint "eagle-import:R0402")
      (libsource (lib "eagle-import") (part "rcl-modified-footprints_R-EU_R0402"))
    )
    (comp (ref "R33")
      (value "RES SMD 100 OHM 1% 1/10W 0402")
      (footprint "eagle-import:R0402")
      (libsource (lib "eagle-import") (part "rcl-modified-footprints_R-EU_R0402"))
    )
    (comp (ref "R36")
      (value "RES SMD 10K OHM 1% 1/10W 0603")
      (footprint "eagle-import:R0603")
      (libsource (lib "eagle-import") (part "rcl-modified-footprints_R-EU_R0603"))
    )
    (comp (ref "U2")
      (value "SN65EPT22DGK")
      (footprint "eagle-import:SOP65P490X110-8N")
      (libsource (lib "eagle-import") (part "SN65EPT22DGK"))
    )
    (comp (ref "U3")
      (value "SN65EPT21DGK")
      (footprint "eagle-import:SOP65P490X110-8N")
      (libsource (lib "eagle-import") (part "SN65EPT21DGK"))
    )
    (comp (ref "C58")
      (value "CAP CER 0.1UF 10V X7R 0402 10%")
      (footprint "eagle-import:C0402")
      (libsource (lib "eagle-import") (part "rcl-modified-footprints_C-EUC0402"))
    )
    (comp (ref "C59")
      (value "CAP CER 0.1UF 10V X7R 0402 10%")
      (footprint "eagle-import:C0402")
      (libsource (lib "eagle-import") (part "rcl-modified-footprints_C-EUC0402"))
    )
    (comp (ref "C60")
      (value "CAP CER 10000PF 10V X7R 0402 10%")
      (footprint "eagle-import:C0402")
      (libsource (lib "eagle-import") (part "C-EUC0402"))
    )
    (comp (ref "C61")
      (value "CAP CER 0.1UF 10V X7R 0402 10%")
      (footprint "eagle-import:C0402")
      (libsource (lib "eagle-import") (part "C-EUC0402"))
    )
    (comp (ref "C63")
      (value "CAP CER 10000PF 10V X7R 0402 10%")
      (footprint "eagle-import:C0402")
      (libsource (lib "eagle-import") (part "rcl-modified-footprints_C-EUC0402"))
    )
    (comp (ref "C64")
      (value "CAP CER 10000PF 10V X7R 0402 10%")
      (footprint "eagle-import:C0402")
      (libsource (lib "eagle-import") (part "rcl-modified-footprints_C-EUC0402"))
    )
    (comp (ref "C65")
      (value "CAP CER 0.1UF 10V X7R 0402 10%")
      (footprint "eagle-import:C0402")
      (libsource (lib "eagle-import") (part "C-EUC0402"))
    )
    (comp (ref "C66")
      (value "CAP CER 10000PF 10V X7R 0402 10%")
      (footprint "eagle-import:C0402")
      (libsource (lib "eagle-import") (part "C-EUC0402"))
    )
    (comp (ref "C81")
      (value "CAP CER 10000PF 10V X7R 0402 10%")
      (footprint "eagle-import:C0402")
      (libsource (lib "eagle-import") (part "C-EUC0402"))
    )
    (comp (ref "C83")
      (value "CAP CER 0.1UF 10V X7R 0402 10%")
      (footprint "eagle-import:C0402")
      (libsource (lib "eagle-import") (part "C-EUC0402"))
    )
    (comp (ref "C84")
      (value "CAP CER 10000PF 10V X7R 0402 10%")
      (footprint "eagle-import:C0402")
      (libsource (lib "eagle-import") (part "rcl-modified-footprints_C-EUC0402"))
    )
    (comp (ref "C85")
      (value "CAP CER 10000PF 10V X7R 0402 10%")
      (footprint "eagle-import:C0402")
      (libsource (lib "eagle-import") (part "rcl-modified-footprints_C-EUC0402"))
    )
    (comp (ref "C89")
      (value "CAP CER 0.1UF 10V X7R 0402 10%")
      (footprint "eagle-import:C0402")
      (libsource (lib "eagle-import") (part "rcl-modified-footprints_C-EUC0402"))
    )
    (comp (ref "C90")
      (value "CAP CER 0.1UF 10V X7R 0402 10%")
      (footprint "eagle-import:C0402")
      (libsource (lib "eagle-import") (part "rcl-modified-footprints_C-EUC0402"))
    )
    (comp (ref "IC16")
      (value "74AHC1G14DCK")
      (footprint "eagle-import:SC70-5")
      (libsource (lib "eagle-import") (part "741G14DCKAHC"))
    )
    (comp (ref "IC17")
      (value "NL17SZ125")
      (footprint "eagle-import:SC70-5")
      (libsource (lib "eagle-import") (part "741G125DCKAHC"))
    )
    (comp (ref "IC18")
      (value "74AHC1G04DCK")
      (footprint "eagle-import:SC70-5")
      (libsource (lib "eagle-import") (part "741G04DCKAHC"))
    )
    (comp (ref "IC19")
      (value "74AHC1G32DCK")
      (footprint "eagle-import:SC70-5")
      (libsource (lib "eagle-import") (part "741G32DCKAHC"))
    )
    (comp (ref "IC20")
      (value "NC7WZ16P6X")
      (footprint "eagle-import:SC70-6L")
      (libsource (lib "eagle-import") (part "NC7WZ16P6X"))
    )
    (comp (ref "IC21")
      (value "74AHC1G08DCK")
      (footprint "eagle-import:SC70-5")
      (libsource (lib "eagle-import") (part "741G08DCKAHC"))
    )
    (comp (ref "IC22")
      (value "74AHC1G08DCK")
      (footprint "eagle-import:SC70-5")
      (libsource (lib "eagle-import") (part "741G08DCKAHC"))
    )
    (comp (ref "R49")
      (value "RES SMD 49.9 OHM 1% 1/10W 0603")
      (footprint "eagle-import:R0603")
      (libsource (lib "eagle-import") (part "R-EU_R0603"))
    )
    (comp (ref "R52")
      (value "RES SMD 49.9 OHM 1% 1/10W 0603")
      (footprint "eagle-import:R0603")
      (libsource (lib "eagle-import") (part "R-EU_R0603"))
    )
    (comp (ref "X2")
      (value "CONN_FORCE_QUENCH")
      (footprint "eagle-import:J502-ND-142-0701-881_886")
      (fields
        (field (name "MF") "JOHNSON COMPONENTS")
        (field (name "MPN") "142-0701-881")
        (field (name "MF_1") "JOHNSON COMPONENTS")
        (field (name "MPN_1") "142-0711-871")
        (field (name "OC_FARNELL") "unknown")
        (field (name "OC_NEWARK") "01C1639")
      )
      (libsource (lib "eagle-import") (part "SMA-142-0701-881/886"))
    )
    (comp (ref "X5")
      (value "CONN_PHOTON_COUNTER")
      (footprint "eagle-import:J502-ND-142-0701-881_886")
      (fields (field (name "MF") "JOHNSON COMPONENTS") (field (name "MPN") "142-0701-881"))
      (libsource (lib "eagle-import") (part "SMA-142-0701-881/886"))
    )
    (comp (ref "DNP1000")
      (value "RLE_LOGO")
      (footprint "eagle-import:RLE_LOGO")
      (libsource (lib "eagle-import") (part "RLE_LOGO"))
    )
    (comp (ref "C3")
      (value "CAP CER 1000PF 50V X7R 0603 10%")
      (footprint "eagle-import:C0603")
      (libsource (lib "eagle-import") (part "C-EUC0603"))
    )
    (comp (ref "C4")
      (value "CAP CER 1300PF 50V C0G 0603 5%")
      (footprint "eagle-import:C0603")
      (libsource (lib "eagle-import") (part "C-EUC0603"))
    )
    (comp (ref "C13")
      (value "CAP ALUM POLY 47UF 20% 20V SMD")
      (footprint "eagle-import:CT7343")
      (libsource (lib "eagle-import") (part "CPOL-EUCT7343"))
    )
    (comp (ref "C14")
      (value "CAP ALUM POLY 47UF 20% 20V SMD")
      (footprint "eagle-import:CT7343")
      (libsource (lib "eagle-import") (part "CPOL-EUCT7343"))
    )
    (comp (ref "C15")
      (value "CAP CER 4.7UF 25V X7R 0805 10%")
      (footprint "eagle-import:C0805")
      (libsource (lib "eagle-import") (part "C-EUC0805"))
    )
    (comp (ref "C17")
      (value "CAP CER 0.1UF 25V X7R 0603 10%")
      (footprint "eagle-import:C0603")
      (libsource (lib "eagle-import") (part "C-EUC0603"))
    )
    (comp (ref "C18")
      (value "CAP CER 0.015UF 50V X7R 0603 10%")
      (footprint "eagle-import:C0603")
      (libsource (lib "eagle-import") (part "C-EUC0603"))
    )
    (comp (ref "C19")
      (value "CAP CER 220PF 50V C0G 0603 5%")
      (footprint "eagle-import:C0603")
      (libsource (lib "eagle-import") (part "C-EUC0603"))
    )
    (comp (ref "C25")
      (value "CAP ALUM POLY 47UF 20% 20V SMD")
      (footprint "eagle-import:CT7343")
      (libsource (lib "eagle-import") (part "CPOL-EUCT7343"))
    )
    (comp (ref "D1")
      (value "CDBA140SL-HF")
      (footprint "eagle-import:DO214AC")
      (libsource (lib "eagle-import") (part "DIODE-DO214AC"))
    )
    (comp (ref "IC3")
      (value "LT1534-1")
      (footprint "eagle-import:SO16")
      (libsource (lib "eagle-import") (part "LT1534"))
    )
    (comp (ref "L1")
      (value "25n")
      (footprint "eagle-import:R0603")
      (libsource (lib "eagle-import") (part "INDUCTOR0603"))
    )
    (comp (ref "L2")
      (value "Wurth-7447709471")
      (footprint "eagle-import:WE_INDUCTOR_SIZE_CODE_1210")
      (libsource (lib "eagle-import") (part "WE_INDUCTOR"))
    )
    (comp (ref "L3")
      (value "SRF0703-820M")
      (footprint "eagle-import:SRF0703")
      (libsource (lib "eagle-import") (part "SRF0703"))
    )
    (comp (ref "R3")
      (value "RES SMD 0 OHM JUMPER 0603")
      (footprint "eagle-import:R0603")
      (libsource (lib "eagle-import") (part "rcl-modified-footprints_R-EU_R0603"))
    )
    (comp (ref "R4")
      (value "DNP")
      (footprint "eagle-import:R0603")
      (libsource (lib "eagle-import") (part "rcl-modified-footprints_R-EU_R0603"))
    )
    (comp (ref "R5")
      (value "RES SMD 29.4K OHM 1% 1/10W 0603")
      (footprint "eagle-import:R0603")
      (libsource (lib "eagle-import") (part "rcl-modified-footprints_R-EU_R0603"))
    )
    (comp (ref "R6")
      (value "RES SMD 2.49K OHM 1% 1/10W 0603")
      (footprint "eagle-import:R0603")
      (libsource (lib "eagle-import") (part "rcl-modified-footprints_R-EU_R0603"))
    )
    (comp (ref "R7")
      (value "RES SMD 10 OHM 1% 1/10W 0603")
      (footprint "eagle-import:R0603")
      (libsource (lib "eagle-import") (part "resistor_R-EU_R0603"))
    )
    (comp (ref "R8")
      (value "RES SMD 16.9K OHM 1% 1/10W 0603")
      (footprint "eagle-import:R0603")
      (libsource (lib "eagle-import") (part "resistor_R-EU_R0603"))
    )
    (comp (ref "R9")
      (value "DNP")
      (footprint "eagle-import:R0603")
      (libsource (lib "eagle-import") (part "rcl-modified-footprints_R-EU_R0603"))
    )
    (comp (ref "R14")
      (value "RES SMD 1K OHM 1% 1/10W 0603")
      (footprint "eagle-import:R0603")
      (libsource (lib "eagle-import") (part "resistor_R-EU_R0603"))
    )
    (comp (ref "R15")
      (value "RES SMD 1K OHM 1% 1/10W 0603")
      (footprint "eagle-import:R0603")
      (libsource (lib "eagle-import") (part "resistor_R-EU_R0603"))
    )
    (comp (ref "R16")
      (value "RES SMD 6.8K OHM 1% 1/10W 0603")
      (footprint "eagle-import:R0603")
      (libsource (lib "eagle-import") (part "resistor_R-EU_R0603"))
    )
    (comp (ref "TP2")
      (value "TPB1,27")
      (footprint "eagle-import:B1,27")
      (libsource (lib "eagle-import") (part "TPB1,27"))
    )
    (comp (ref "TP7")
      (value "TPB1,27")
      (footprint "eagle-import:B1,27")
      (libsource (lib "eagle-import") (part "TPB1,27"))
    )
    (comp (ref "C55")
      (value "CAP CER 0.1UF 10V X7R 0402 10%")
      (footprint "eagle-import:C0402")
      (libsource (lib "eagle-import") (part "rcl-modified-footprints_C-EUC0402"))
    )
    (comp (ref "C62")
      (value "CAP CER 10000PF 10V X7R 0402 10%")
      (footprint "eagle-import:C0402")
      (libsource (lib "eagle-import") (part "rcl-modified-footprints_C-EUC0402"))
    )
    (comp (ref "C70")
      (value "CAP CER 100PF 50V C0G 0603 5%")
      (footprint "eagle-import:C0603")
      (libsource (lib "eagle-import") (part "rcl-modified-footprints_C-EUC0603"))
    )
    (comp (ref "C72")
      (value "DNP")
      (footprint "eagle-import:C0402")
      (libsource (lib "eagle-import") (part "rcl-modified-footprints_C-EUC0402"))
    )
    (comp (ref "C73")
      (value "CAP CER 0.1UF 10V X7R 0402 10%")
      (footprint "eagle-import:C0402")
      (libsource (lib "eagle-import") (part "C-EUC0402"))
    )
    (comp (ref "C74")
      (value "CAP CER 10000PF 10V X7R 0402 10%")
      (footprint "eagle-import:C0402")
      (libsource (lib "eagle-import") (part "C-EUC0402"))
    )
    (comp (ref "C77")
      (value "CAP CER 0.1UF 10V X7R 0402 10%")
      (footprint "eagle-import:C0402")
      (libsource (lib "eagle-import") (part "rcl-modified-footprints_C-EUC0402"))
    )
    (comp (ref "C78")
      (value "CAP CER 10000PF 10V X7R 0402 10%")
      (footprint "eagle-import:C0402")
      (libsource (lib "eagle-import") (part "rcl-modified-footprints_C-EUC0402"))
    )
    (comp (ref "C80")
      (value "CAP CER 0.1UF 10V X7R 0402 10%")
      (footprint "eagle-import:C0402")
      (libsource (lib "eagle-import") (part "rcl-modified-footprints_C-EUC0402"))
    )
    (comp (ref "C93")
      (value "CAP CER 0.1UF 10V X7R 0402 10%")
      (footprint "eagle-import:C0402")
      (libsource (lib "eagle-import") (part "rcl-modified-footprints_C-EUC0402"))
    )
    (comp (ref "IC14")
      (value "LTC1711")
      (footprint "eagle-import:MSOP8")
      (libsource (lib "eagle-import") (part "LTC1711"))
    )
    (comp (ref "IC15")
      (value "NC7SV74K8X")
      (footprint "eagle-import:US8_3.1MM_JDEC_MO-187")
      (libsource (lib "eagle-import") (part "NC7SV74K8X"))
    )
    (comp (ref "IC24")
      (value "TLV272DGK")
      (footprint "eagle-import:MSOP8")
      (libsource (lib "eagle-import") (part "TLV272DGK"))
    )
    (comp (ref "R40")
      (value "RES SMD 49.9 OHM 1% 1/10W 0603")
      (footprint "eagle-import:R0603")
      (libsource (lib "eagle-import") (part "rcl-modified-footprints_R-EU_R0603"))
    )
    (comp (ref "R47")
      (value "RES SMD 0 OHM JUMPER 0603")
      (footprint "eagle-import:R0603")
      (libsource (lib "eagle-import") (part "rcl-modified-footprints_R-EU_R0603"))
    )
    (comp (ref "R51")
      (value "RES SMD 0 OHM JUMPER 0603")
      (footprint "eagle-import:R0603")
      (libsource (lib "eagle-import") (part "rcl-modified-footprints_R-EU_R0603"))
    )
    (comp (ref "R53")
      (value "RES SMD 220K OHM 1% 1/10W 0603")
      (footprint "eagle-import:R0603")
      (libsource (lib "eagle-import") (part "rcl-modified-footprints_R-EU_R0603"))
    )
    (comp (ref "R54")
      (value "RES SMD 10K OHM 1% 1/10W 0603")
      (footprint "eagle-import:R0603")
      (libsource (lib "eagle-import") (part "rcl-modified-footprints_R-EU_R0603"))
    )
    (comp (ref "R56")
      (value "RES SMD 100K OHM 1% 1/10W 0603")
      (footprint "eagle-import:R0603")
      (libsource (lib "eagle-import") (part "rcl-modified-footprints_R-EU_R0603"))
    )
    (comp (ref "R57")
      (value "RES SMD 100K OHM 1% 1/10W 0603")
      (footprint "eagle-import:R0603")
      (libsource (lib "eagle-import") (part "rcl-modified-footprints_R-EU_R0603"))
    )
    (comp (ref "R61")
      (value "RES SMD 220K OHM 1% 1/10W 0603")
      (footprint "eagle-import:R0603")
      (libsource (lib "eagle-import") (part "rcl-modified-footprints_R-EU_R0603"))
    )
    (comp (ref "T1")
      (value "MMBTH10−4LT1G")
      (footprint "eagle-import:SOT23-BEC")
      (libsource (lib "eagle-import") (part "-NPN-SOT23-BECMMBTH10LT1"))
    )
    (comp (ref "TP12")
      (value "TPTP06R")
      (footprint "eagle-import:TP06R")
      (libsource (lib "eagle-import") (part "TPTP06R"))
    )
    (comp (ref "TP13")
      (value "TPTP06R")
      (footprint "eagle-import:TP06R")
      (libsource (lib "eagle-import") (part "TPTP06R"))
    )
  )
  (nets
    (net (code "1") (name "BLANKING_LATCH_EN") (class "Default")
      (node (ref "R24") (pin "1") (pinfunction "1_1") (pintype "passive"))
      (node (ref "R25") (pin "1") (pinfunction "1_1") (pintype "passive"))
      (node (ref "R26") (pin "1") (pinfunction "1_1") (pintype "passive"))
      (node (ref "R27") (pin "1") (pinfunction "1_1") (pintype "passive"))
      (node (ref "R28") (pin "1") (pinfunction "1_1") (pintype "passive"))
      (node (ref "U2") (pin "7") (pinfunction "D0_7") (pintype "input"))
    )
    (net (code "2") (name "CAP_~{RESET}") (class "Default")
      (node (ref "IC17") (pin "1") (pinfunction "OE_1") (pintype "input"))
      (node (ref "IC22") (pin "4") (pinfunction "O_4") (pintype "output"))
    )
    (net (code "3") (name "CCS_STEERING_TAIL") (class "Default")
      (node (ref "IC13") (pin "2") (pinfunction "E_2") (pintype "passive"))
      (node (ref "IC13") (pin "5") (pinfunction "E_5") (pintype "passive"))
      (node (ref "IC23") (pin "6") (pinfunction "C_6") (pintype "passive"))
    )
    (net (code "4") (name "CCS_VA_SETPOINT") (class "Default")
      (node (ref "IC11") (pin "5") (pinfunction "E_5") (pintype "passive"))
      (node (ref "IC23") (pin "3") (pinfunction "C_3") (pintype "passive"))
    )
    (net (code "5") (name "COMP_LE_N") (class "Default")
      (node (ref "IC4") (pin "6") (pinfunction "~{LE}_6") (pintype "bidirectional"))
      (node (ref "U2") (pin "1") (pinfunction "Q0_1") (pintype "output"))
    )
    (net (code "6") (name "COMP_LE_P") (class "Default")
      (node (ref "IC4") (pin "7") (pinfunction "LE_7") (pintype "bidirectional"))
      (node (ref "U2") (pin "2") (pinfunction "~{Q0}_2") (pintype "output"))
    )
    (net (code "7") (name "COMP_Q_N") (class "Default")
      (node (ref "IC4") (pin "10") (pinfunction "~{Q}_10") (pintype "bidirectional"))
      (node (ref "R22") (pin "1") (pinfunction "1_1") (pintype "passive"))
      (node (ref "R33") (pin "1") (pinfunction "1_1") (pintype "passive"))
      (node (ref "U3") (pin "3") (pinfunction "~{D}_3") (pintype "input"))
    )
    (net (code "8") (name "COMP_Q_P") (class "Default")
      (node (ref "IC4") (pin "11") (pinfunction "Q_11") (pintype "bidirectional"))
      (node (ref "R31") (pin "1") (pinfunction "1_1") (pintype "passive"))
      (node (ref "R33") (pin "2") (pinfunction "2_2") (pintype "passive"))
      (node (ref "U3") (pin "2") (pinfunction "D_2") (pintype "input"))
    )
    (net (code "9") (name "DAC1_DIN") (class "Default")
      (node (ref "IC30") (pin "53") (pinfunction "PC12/SDIO_CLK_53") (pintype "bidirectional"))
      (node (ref "IC31") (pin "13") (pinfunction "DIN_13") (pintype "bidirectional"))
    )
    (net (code "10") (name "DAC1_DOUT") (class "Default")
      (node (ref "IC30") (pin "52") (pinfunction "PC11/SDIO_D3_52") (pintype "bidirectional"))
      (node (ref "IC31") (pin "12") (pinfunction "DOUT_12") (pintype "bidirectional"))
    )
    (net (code "11") (name "DAC1_SCLK") (class "Default")
      (node (ref "IC30") (pin "51") (pinfunction "PC10/SDIO_D2_51") (pintype "bidirectional"))
      (node (ref "IC31") (pin "14") (pinfunction "SCLK_14") (pintype "bidirectional"))
    )
    (net (code "12") (name "DAC1_~{CLR}") (class "Default")
      (node (ref "IC30") (pin "54") (pinfunction "PD2/SDIO_CMD_54") (pintype "bidirectional"))
      (node (ref "IC31") (pin "17") (pinfunction "~{CLR}_17") (pintype "bidirectional"))
    )
    (net (code "13") (name "DAC2_ADDRSEL") (class "Default")
      (node (ref "IC30") (pin "57") (pinfunction "PB5_57") (pintype "bidirectional"))
      (node (ref "U1") (pin "6") (pinfunction "A0_6") (pintype "input"))
    )
    (net (code "14") (name "DAC2_SCL") (class "Default")
      (node (ref "IC30") (pin "58") (pinfunction "PB6/I2C1_SCL_58") (pintype "bidirectional"))
      (node (ref "R12") (pin "2") (pinfunction "2_2") (pintype "passive"))
      (node (ref "U1") (pin "5") (pinfunction "SCL_5") (pintype "bidirectional"))
    )
    (net (code "15") (name "DAC2_SDA") (class "Default")
      (node (ref "IC30") (pin "59") (pinfunction "PB7/I2C1_SDA_59") (pintype "bidirectional"))
      (node (ref "R13") (pin "2") (pinfunction "2_2") (pintype "passive"))
      (node (ref "U1") (pin "4") (pinfunction "SDA_4") (pintype "bidirectional"))
    )
    (net (code "16") (name "DELTAV_BASE") (class "Default")
      (node (ref "IC23") (pin "1") (pinfunction "B_1") (pintype "passive"))
      (node (ref "IC26") (pin "1") (pinfunction "OUT_1") (pintype "output"))
    )
    (net (code "17") (name "DELTAV_FB") (class "Default")
      (node (ref "IC23") (pin "2") (pinfunction "E_2") (pintype "passive"))
      (node (ref "R59") (pin "1") (pinfunction "1_1") (pintype "passive"))
      (node (ref "R63") (pin "2") (pinfunction "2_2") (pintype "passive"))
    )
    (net (code "18") (name "DELTAV_VGND") (class "Default")
      (node (ref "IC26") (pin "2") (pinfunction "-IN_2") (pintype "input"))
      (node (ref "R59") (pin "2") (pinfunction "2_2") (pintype "passive"))
      (node (ref "R64") (pin "1") (pinfunction "1_1") (pintype "passive"))
    )
    (net (code "19") (name "DFLOP_~{CLR}") (class "Default")
      (node (ref "IC15") (pin "6") (pinfunction "~{CLR}_6") (pintype "bidirectional"))
      (node (ref "IC21") (pin "4") (pinfunction "O_4") (pintype "output"))
    )
    (net (code "20") (name "DIAMOND_BASE") (class "Default")
      (node (ref "IC27") (pin "1") (pinfunction "B_1") (pintype "passive"))
      (node (ref "IC27") (pin "4") (pinfunction "B_4") (pintype "passive"))
      (node (ref "IC28") (pin "1") (pinfunction "OUT_1") (pintype "output"))
    )
    (net (code "21") (name "DIAMOND_FB") (class "Default")
      (node (ref "IC27") (pin "2") (pinfunction "E_2") (pintype "passive"))
      (node (ref "IC28") (pin "4") (pinfunction "-IN_4") (pintype "input"))
      (node (ref "R68") (pin "2") (pinfunction "TOP_2") (pintype "bidirectional"))
    )
    (net (code "22") (name "DIAMOND_FB_R") (class "Default")
      (node (ref "IC27") (pin "5") (pinfunction "E_5") (pintype "passive"))
      (node (ref "R68") (pin "1") (pinfunction "BOTTOM_1") (pintype "bidirectional"))
    )
    (net (code "23") (name "DIAMOND_IBIAS_BOTTOM") (class "Default")
      (node (ref "C52") (pin "2") (pinfunction "2_2") (pintype "passive"))
      (node (ref "IC5") (pin "3") (pinfunction "C_3") (pintype "passive"))
      (node (ref "IC8") (pin "4") (pinfunction "B_4") (pintype "passive"))
      (node (ref "R38") (pin "1") (pinfunction "1_1") (pintype "passive"))
    )
    (net (code "24") (name "DIAMOND_IBIAS_MID") (class "Default")
      (node (ref "IC25") (pin "6") (pinfunction "B_6") (pintype "passive"))
      (node (ref "IC25") (pin "8") (pinfunction "C_8") (pintype "passive"))
      (node (ref "IC25") (pin "9") (pinfunction "B_9") (pintype "passive"))
      (node (ref "IC5") (pin "6") (pinfunction "C_6") (pintype "passive"))
    )
    (net (code "25") (name "DIAMOND_IBIAS_TOP") (class "Default")
      (node (ref "C52") (pin "1") (pinfunction "1_1") (pintype "passive"))
      (node (ref "IC12") (pin "4") (pinfunction "B_4") (pintype "passive"))
      (node (ref "IC25") (pin "7") (pinfunction "C_7") (pintype "passive"))
      (node (ref "R39") (pin "2") (pinfunction "2_2") (pintype "passive"))
    )
    (net (code "26") (name "DIAMOND_IN") (class "Default")
      (node (ref "IC11") (pin "3") (pinfunction "C_3") (pintype "passive"))
      (node (ref "IC11") (pin "6") (pinfunction "C_6") (pintype "passive"))
      (node (ref "IC12") (pin "1") (pinfunction "B_1") (pintype "passive"))
      (node (ref "IC8") (pin "1") (pinfunction "B_1") (pintype "passive"))
      (node (ref "R46") (pin "1") (pinfunction "1_1") (pintype "passive"))
    )
    (net (code "27") (name "DMD_IN_CASC") (class "Default")
      (node (ref "IC6") (pin "2") (pinfunction "E_2") (pintype "passive"))
      (node (ref "IC8") (pin "6") (pinfunction "C_6") (pintype "passive"))
    )
    (net (code "28") (name "DMD_IN_NPN_E") (class "Default")
      (node (ref "IC12") (pin "2") (pinfunction "E_2") (pintype "passive"))
      (node (ref "R38") (pin "2") (pinfunction "2_2") (pintype "passive"))
    )
    (net (code "29") (name "DMD_IN_PNP_E") (class "Default")
      (node (ref "IC8") (pin "2") (pinfunction "E_2") (pintype "passive"))
      (node (ref "R39") (pin "1") (pinfunction "1_1") (pintype "passive"))
    )
    (net (code "30") (name "DMD_OP_CASC") (class "Default")
      (node (ref "IC6") (pin "5") (pinfunction "E_5") (pintype "passive"))
      (node (ref "IC8") (pin "3") (pinfunction "C_3") (pintype "passive"))
    )
    (net (code "31") (name "DMD_OP_NPN") (class "Default")
      (node (ref "C51") (pin "1") (pinfunction "1_1") (pintype "passive"))
      (node (ref "IC12") (pin "5") (pinfunction "E_5") (pintype "passive"))
      (node (ref "R42") (pin "2") (pinfunction "2_2") (pintype "passive"))
    )
    (net (code "32") (name "DMD_OP_PNP") (class "Default")
      (node (ref "C51") (pin "2") (pinfunction "2_2") (pintype "passive"))
      (node (ref "IC8") (pin "5") (pinfunction "E_5") (pintype "passive"))
      (node (ref "R37") (pin "1") (pinfunction "1_1") (pintype "passive"))
    )
    (net (code "33") (name "DMD_OUT") (class "Default")
      (node (ref "R35") (pin "1") (pinfunction "1_1") (pintype "passive"))
      (node (ref "R37") (pin "2") (pinfunction "2_2") (pintype "passive"))
      (node (ref "R42") (pin "1") (pinfunction "1_1") (pintype "passive"))
      (node (ref "RLY1") (pin "10") (pinfunction "PIN10_10") (pintype "bidirectional"))
    )
    (net (code "34") (name "FORCE_QUENCH") (class "Default")
      (node (ref "IC18") (pin "2") (pinfunction "I_2") (pintype "input"))
      (node (ref "IC19") (pin "4") (pinfunction "O_4") (pintype "output"))
    )
    (net (code "35") (name "FORCE_QUENCH_USER") (class "Default")
      (node (ref "IC19") (pin "1") (pinfunction "I0_1") (pintype "input"))
      (node (ref "R49") (pin "2") (pinfunction "2_2") (pintype "passive"))
      (node (ref "X2") (pin "1") (pinfunction "1_1") (pintype "passive"))
    )
    (net (code "36") (name "GND") (class "Default")
      (node (ref "C1") (pin "2") (pinfunction "2_2") (pintype "passive"))
      (node (ref "C10") (pin "2") (pinfunction "2_2") (pintype "passive"))
      (node (ref "C100") (pin "2") (pinfunction "2_2") (pintype "passive"))
      (node (ref "C101") (pin "2") (pinfunction "2_2") (pintype "passive"))
      (node (ref "C102") (pin "2") (pinfunction "2_2") (pintype "passive"))
      (node (ref "C103") (pin "2") (pinfunction "2_2") (pintype "passive"))
      (node (ref "C104") (pin "2") (pinfunction "2_2") (pintype "passive"))
      (node (ref "C105") (pin "2") (pinfunction "2_2") (pintype "passive"))
      (node (ref "C106") (pin "2") (pinfunction "2_2") (pintype "passive"))
      (node (ref "C107") (pin "2") (pinfunction "2_2") (pintype "passive"))
      (node (ref "C108") (pin "2") (pinfunction "2_2") (pintype "passive"))
      (node (ref "C109") (pin "2") (pinfunction "2_2") (pintype "passive"))
      (node (ref "C11") (pin "2") (pinfunction "2_2") (pintype "passive"))
      (node (ref "C110") (pin "2") (pinfunction "2_2") (pintype "passive"))
      (node (ref "C111") (pin "2") (pinfunction "2_2") (pintype "passive"))
      (node (ref "C112") (pin "2") (pinfunction "2_2") (pintype "passive"))
      (node (ref "C113") (pin "2") (pinfunction "2_2") (pintype "passive"))
      (node (ref "C12") (pin "2") (pinfunction "2_2") (pintype "passive"))
      (node (ref "C13") (pin "-") (pinfunction "-_-") (pintype "passive"))
      (node (ref "C14") (pin "-") (pinfunction "-_-") (pintype "passive"))
      (node (ref "C15") (pin "2") (pinfunction "2_2") (pintype "passive"))
      (node (ref "C16") (pin "2") (pinfunction "2_2") (pintype "passive"))
      (node (ref "C17") (pin "2") (pinfunction "2_2") (pintype "passive"))
      (node (ref "C18") (pin "2") (pinfunction "2_2") (pintype "passive"))
      (node (ref "C19") (pin "2") (pinfunction "2_2") (pintype "passive"))
      (node (ref "C2") (pin "2") (pinfunction "2_2") (pintype "passive"))
      (node (ref "C20") (pin "2") (pinfunction "2_2") (pintype "passive"))
      (node (ref "C21") (pin "2") (pinfunction "2_2") (pintype "passive"))
      (node (ref "C22") (pin "2") (pinfunction "2_2") (pintype "passive"))
      (node (ref "C23") (pin "2") (pinfunction "2_2") (pintype "passive"))
      (node (ref "C24") (pin "2") (pinfunction "2_2") (pintype "passive"))
      (node (ref "C25") (pin "-") (pinfunction "-_-") (pintype "passive"))
      (node (ref "C26") (pin "-") (pinfunction "-_-") (pintype "passive"))
      (node (ref "C27") (pin "2") (pinfunction "2_2") (pintype "passive"))
      (node (ref "C28") (pin "2") (pinfunction "2_2") (pintype "passive"))
      (node (ref "C29") (pin "2") (pinfunction "2_2") (pintype "passive"))
      (node (ref "C3") (pin "1") (pinfunction "1_1") (pintype "passive"))
      (node (ref "C30") (pin "2") (pinfunction "2_2") (pintype "passive"))
      (node (ref "C31") (pin "2") (pinfunction "2_2") (pintype "passive"))
      (node (ref "C32") (pin "2") (pinfunction "2_2") (pintype "passive"))
      (node (ref "C33") (pin "2") (pinfunction "2_2") (pintype "passive"))
      (node (ref "C34") (pin "2") (pinfunction "2_2") (pintype "passive"))
      (node (ref "C35") (pin "2") (pinfunction "2_2") (pintype "passive"))
      (node (ref "C36") (pin "2") (pinfunction "2_2") (pintype "passive"))
      (node (ref "C37") (pin "2") (pinfunction "2_2") (pintype "passive"))
      (node (ref "C38") (pin "2") (pinfunction "2_2") (pintype "passive"))
      (node (ref "C39") (pin "2") (pinfunction "2_2") (pintype "passive"))
      (node (ref "C4") (pin "2") (pinfunction "2_2") (pintype "passive"))
      (node (ref "C40") (pin "2") (pinfunction "2_2") (pintype "passive"))
      (node (ref "C43") (pin "2") (pinfunction "2_2") (pintype "passive"))
      (node (ref "C44") (pin "2") (pinfunction "2_2") (pintype "passive"))
      (node (ref "C45") (pin "2") (pinfunction "2_2") (pintype "passive"))
      (node (ref "C46") (pin "2") (pinfunction "2_2") (pintype "passive"))
      (node (ref "C47") (pin "2") (pinfunction "2_2") (pintype "passive"))
      (node (ref "C48") (pin "2") (pinfunction "2_2") (pintype "passive"))
      (node (ref "C49") (pin "2") (pinfunction "2_2") (pintype "passive"))
      (node (ref "C50") (pin "2") (pinfunction "2_2") (pintype "passive"))
      (node (ref "C53") (pin "2") (pinfunction "2_2") (pintype "passive"))
      (node (ref "C54") (pin "2") (pinfunction "2_2") (pintype "passive"))
      (node (ref "C55") (pin "2") (pinfunction "2_2") (pintype "passive"))
      (node (ref "C56") (pin "2") (pinfunction "2_2") (pintype "passive"))
      (node (ref "C57") (pin "2") (pinfunction "2_2") (pintype "passive"))
      (node (ref "C58") (pin "2") (pinfunction "2_2") (pintype "passive"))
      (node (ref "C59") (pin "2") (pinfunction "2_2") (pintype "passive"))
      (node (ref "C60") (pin "2") (pinfunction "2_2") (pintype "passive"))
      (node (ref "C61") (pin "2") (pinfunction "2_2") (pintype "passive"))
      (node (ref "C62") (pin "2") (pinfunction "2_2") (pintype "passive"))
      (node (ref "C63") (pin "2") (pinfunction "2_2") (pintype "passive"))
      (node (ref "C64") (pin "2") (pinfunction "2_2") (pintype "passive"))
      (node (ref "C65") (pin "2") (pinfunction "2_2") (pintype "passive"))
      (node (ref "C66") (pin "2") (pinfunction "2_2") (pintype "passive"))
      (node (ref "C67") (pin "2") (pinfunction "2_2") (pintype "passive"))
      (node (ref "C68") (pin "2") (pinfunction "2_2") (pintype "passive"))
      (node (ref "C69") (pin "2") (pinfunction "2_2") (pintype "passive"))
      (node (ref "C7") (pin "2") (pinfunction "2_2") (pintype "passive"))
      (node (ref "C70") (pin "2") (pinfunction "2_2") (pintype "passive"))
      (node (ref "C71") (pin "2") (pinfunction "2_2") (pintype "passive"))
      (node (ref "C73") (pin "2") (pinfunction "2_2") (pintype "passive"))
      (node (ref "C74") (pin "2") (pinfunction "2_2") (pintype "passive"))
      (node (ref "C75") (pin "2") (pinfunction "2_2") (pintype "passive"))
      (node (ref "C76") (pin "2") (pinfunction "2_2") (pintype "passive"))
      (node (ref "C77") (pin "2") (pinfunction "2_2") (pintype "passive"))
      (node (ref "C78") (pin "2") (pinfunction "2_2") (pintype "passive"))
      (node (ref "C8") (pin "2") (pinfunction "2_2") (pintype "passive"))
      (node (ref "C80") (pin "2") (pinfunction "2_2") (pintype "passive"))
      (node (ref "C81") (pin "2") (pinfunction "2_2") (pintype "passive"))
      (node (ref "C82") (pin "2") (pinfunction "2_2") (pintype "passive"))
      (node (ref "C83") (pin "2") (pinfunction "2_2") (pintype "passive"))
      (node (ref "C84") (pin "2") (pinfunction "2_2") (pintype "passive"))
      (node (ref "C85") (pin "2") (pinfunction "2_2") (pintype "passive"))
      (node (ref "C86") (pin "2") (pinfunction "2_2") (pintype "passive"))
      (node (ref "C87") (pin "2") (pinfunction "2_2") (pintype "passive"))
      (node (ref "C88") (pin "2") (pinfunction "2_2") (pintype "passive"))
      (node (ref "C89") (pin "2") (pinfunction "2_2") (pintype "passive"))
      (node (ref "C9") (pin "2") (pinfunction "2_2") (pintype "passive"))
      (node (ref "C90") (pin "2") (pinfunction "2_2") (pintype "passive"))
      (node (ref "C91") (pin "2") (pinfunction "2_2") (pintype "passive"))
      (node (ref "C92") (pin "2") (pinfunction "2_2") (pintype "passive"))
      (node (ref "C93") (pin "2") (pinfunction "2_2") (pintype "passive"))
      (node (ref "C94") (pin "2") (pinfunction "2_2") (pintype "passive"))
      (node (ref "C95") (pin "2") (pinfunction "2_2") (pintype "passive"))
      (node (ref "C96") (pin "2") (pinfunction "2_2") (pintype "passive"))
      (node (ref "C97") (pin "2") (pinfunction "2_2") (pintype "passive"))
      (node (ref "C98") (pin "2") (pinfunction "2_2") (pintype "passive"))
      (node (ref "C99") (pin "2") (pinfunction "2_2") (pintype "passive"))
      (node (ref "D2") (pin "C") (pinfunction "C_C") (pintype "passive"))
      (node (ref "D3") (pin "A") (pinfunction "A_A") (pintype "passive"))
      (node (ref "H1") (pin "B3,2") (pinfunction "MOUNT_B3,2") (pintype "passive"))
      (node (ref "H2") (pin "B3,2") (pinfunction "MOUNT_B3,2") (pintype "passive"))
      (node (ref "H3") (pin "B3,2") (pinfunction "MOUNT_B3,2") (pintype "passive"))
      (node (ref "H4") (pin "B3,2") (pinfunction "MOUNT_B3,2") (pintype "passive"))
      (node (ref "IC1") (pin "4") (pinfunction "GND_4") (pintype "bidirectional"))
      (node (ref "IC1") (pin "PAD") (pinfunction "GND_PAD") (pintype "bidirectional"))
      (node (ref "IC10") (pin "1") (pinfunction "GND_1") (pintype "bidirectional"))
      (node (ref "IC10") (pin "16") (pinfunction "GND_16") (pintype "bidirectional"))
      (node (ref "IC10") (pin "8") (pinfunction "GND_8") (pintype "bidirectional"))
      (node (ref "IC10") (pin "9") (pinfunction "GND_9") (pintype "bidirectional"))
      (node (ref "IC14") (pin "5") (pinfunction "LEN_5") (pintype "bidirectional"))
      (node (ref "IC14") (pin "6") (pinfunction "GND_6") (pintype "bidirectional"))
      (node (ref "IC15") (pin "4") (pinfunction "GND_4") (pintype "bidirectional"))
      (node (ref "IC16") (pin "3") (pinfunction "GND_3") (pintype "power_in"))
      (node (ref "IC17") (pin "3") (pinfunction "GND_3") (pintype "power_in"))
      (node (ref "IC18") (pin "3") (pinfunction "GND_3") (pintype "power_in"))
      (node (ref "IC19") (pin "3") (pinfunction "GND_3") (pintype "power_in"))
      (node (ref "IC2") (pin "4") (pinfunction "GND_4") (pintype "bidirectional"))
      (node (ref "IC2") (pin "PAD") (pinfunction "GND_PAD") (pintype "bidirectional"))
      (node (ref "IC20") (pin "2") (pinfunction "GND_2") (pintype "bidirectional"))
      (node (ref "IC21") (pin "3") (pinfunction "GND_3") (pintype "power_in"))
      (node (ref "IC22") (pin "3") (pinfunction "GND_3") (pintype "power_in"))
      (node (ref "IC24") (pin "3") (pinfunction "+IN_3") (pintype "input"))
      (node (ref "IC25") (pin "11") (pinfunction "SUBC_11") (pintype "bidirectional"))
      (node (ref "IC25") (pin "4") (pinfunction "SUBC_4") (pintype "bidirectional"))
      (node (ref "IC26") (pin "3") (pinfunction "+IN_3") (pintype "input"))
      (node (ref "IC28") (pin "2") (pinfunction "V-_2") (pintype "power_in"))
      (node (ref "IC29") (pin "2") (pinfunction "GND_2") (pintype "bidirectional"))
      (node (ref "IC3") (pin "1") (pinfunction "GND_1") (pintype "bidirectional"))
      (node (ref "IC3") (pin "16") (pinfunction "GND_16") (pintype "bidirectional"))
      (node (ref "IC3") (pin "8") (pinfunction "GND_8") (pintype "bidirectional"))
      (node (ref "IC3") (pin "9") (pinfunction "GND_9") (pintype "bidirectional"))
      (node (ref "IC30") (pin "12") (pinfunction "VSSA_12") (pintype "bidirectional"))
      (node (ref "IC30") (pin "18") (pinfunction "VSS1_18") (pintype "bidirectional"))
      (node (ref "IC30") (pin "63") (pinfunction "VSS2_63") (pintype "bidirectional"))
      (node (ref "IC31") (pin "15") (pinfunction "CSB_15") (pintype "bidirectional"))
      (node (ref "IC31") (pin "19") (pinfunction "GND_19") (pintype "bidirectional"))
      (node (ref "IC31") (pin "20") (pinfunction "M/~{Z}_20") (pintype "bidirectional"))
      (node (ref "IC32") (pin "1") (pinfunction "GND_1") (pintype "bidirectional"))
      (node (ref "IC4") (pin "15") (pinfunction "GND_15") (pintype "bidirectional"))
      (node (ref "IC6") (pin "6") (pinfunction "C_6") (pintype "passive"))
      (node (ref "IC7") (pin "4") (pinfunction "GND_4") (pintype "bidirectional"))
      (node (ref "IC9") (pin "4") (pinfunction "GND_4") (pintype "bidirectional"))
      (node (ref "IC9") (pin "PAD") (pinfunction "GND_PAD") (pintype "bidirectional"))
      (node (ref "L1") (pin "2") (pinfunction "P$2_2") (pintype "bidirectional"))
      (node (ref "L10") (pin "2") (pinfunction "P$2_2") (pintype "bidirectional"))
      (node (ref "L5") (pin "2") (pinfunction "P$2_2") (pintype "bidirectional"))
      (node (ref "LED1") (pin "BOT_K") (pinfunction "BOT_K_BOT_K") (pintype "bidirectional"))
      (node (ref "LED1") (pin "MID_K") (pinfunction "MID_K_MID_K") (pintype "bidirectional"))
      (node (ref "LED1") (pin "TOP_K") (pinfunction "TOP_K_TOP_K") (pintype "bidirectional"))
      (node (ref "M1") (pin "2") (pinfunction "S_2") (pintype "passive"))
      (node (ref "M2") (pin "2") (pinfunction "S_2") (pintype "passive"))
      (node (ref "PROG") (pin "3") (pinfunction "3_3") (pintype "bidirectional"))
      (node (ref "R1") (pin "2") (pinfunction "2_2") (pintype "passive"))
      (node (ref "R14") (pin "2") (pinfunction "2_2") (pintype "passive"))
      (node (ref "R15") (pin "2") (pinfunction "2_2") (pintype "passive"))
      (node (ref "R19") (pin "1") (pinfunction "1_1") (pintype "passive"))
      (node (ref "R2") (pin "2") (pinfunction "2_2") (pintype "passive"))
      (node (ref "R20") (pin "2") (pinfunction "2_2") (pintype "passive"))
      (node (ref "R21") (pin "1") (pinfunction "1_1") (pintype "passive"))
      (node (ref "R22") (pin "2") (pinfunction "2_2") (pintype "passive"))
      (node (ref "R30") (pin "1") (pinfunction "1_1") (pintype "passive"))
      (node (ref "R31") (pin "2") (pinfunction "2_2") (pintype "passive"))
      (node (ref "R34") (pin "2") (pinfunction "2_2") (pintype "passive"))
      (node (ref "R43") (pin "2") (pinfunction "2_2") (pintype "passive"))
      (node (ref "R44") (pin "2") (pinfunction "2_2") (pintype "passive"))
      (node (ref "R48") (pin "2") (pinfunction "2_2") (pintype "passive"))
      (node (ref "R49") (pin "1") (pinfunction "1_1") (pintype "passive"))
      (node (ref "R50") (pin "1") (pinfunction "1_1") (pintype "passive"))
      (node (ref "R6") (pin "2") (pinfunction "2_2") (pintype "passive"))
      (node (ref "R68") (pin "3") (pinfunction "MIDDLE_3") (pintype "bidirectional"))
      (node (ref "R71") (pin "2") (pinfunction "2_2") (pintype "passive"))
      (node (ref "R72") (pin "2") (pinfunction "2_2") (pintype "passive"))
      (node (ref "R74") (pin "2") (pinfunction "2_2") (pintype "passive"))
      (node (ref "R8") (pin "1") (pinfunction "1_1") (pintype "passive"))
      (node (ref "RLY1") (pin "1") (pinfunction "PIN1_1") (pintype "bidirectional"))
      (node (ref "RLY1") (pin "4") (pinfunction "PIN4_4") (pintype "bidirectional"))
      (node (ref "RLY1") (pin "6") (pinfunction "PIN6_6") (pintype "bidirectional"))
      (node (ref "RLY1") (pin "9") (pinfunction "PIN9_9") (pintype "bidirectional"))
      (node (ref "RLY2") (pin "1") (pinfunction "PIN1_1") (pintype "bidirectional"))
      (node (ref "RLY2") (pin "4") (pinfunction "PIN4_4") (pintype "bidirectional"))
      (node (ref "RLY2") (pin "6") (pinfunction "PIN6_6") (pintype "bidirectional"))
      (node (ref "RLY2") (pin "9") (pinfunction "PIN9_9") (pintype "bidirectional"))
      (node (ref "SW1") (pin "1") (pinfunction "P$1_1") (pintype "bidirectional"))
      (node (ref "SW1") (pin "2") (pinfunction "P$1_2") (pintype "bidirectional"))
      (node (ref "TP22") (pin "P$1") (pinfunction "P$1_P$1") (pintype "bidirectional"))
      (node (ref "TP4") (pin "TP") (pinfunction "TP_TP") (pintype "input"))
      (node (ref "TP5") (pin "P$1") (pinfunction "P$1_P$1") (pintype "bidirectional"))
      (node (ref "TP9") (pin "GND1") (pinfunction "GND_GND1") (pintype "power_in"))
      (node (ref "TP9") (pin "GND2") (pinfunction "GND_GND2") (pintype "power_in"))
      (node (ref "U1") (pin "2") (pinfunction "GND_2") (pintype "power_in"))
      (node (ref "U2") (pin "5") (pinfunction "GND_5") (pintype "passive"))
      (node (ref "U2") (pin "6") (pinfunction "D1_6") (pintype "input"))
      (node (ref "U3") (pin "5") (pinfunction "GND_5") (pintype "passive"))
      (node (ref "X1") (pin "G@1") (pinfunction "GND_G@1") (pintype "power_in"))
      (node (ref "X2") (pin "G@1") (pinfunction "GND_G@1") (pintype "power_in"))
      (node (ref "X3") (pin "1") (pinfunction "1_1") (pintype "bidirectional"))
      (node (ref "X3") (pin "2") (pinfunction "1_2") (pintype "bidirectional"))
      (node (ref "X3") (pin "3") (pinfunction "1_3") (pintype "bidirectional"))
      (node (ref "X3") (pin "4") (pinfunction "1_4") (pintype "bidirectional"))
      (node (ref "X4") (pin "G@1") (pinfunction "GND_G@1") (pintype "power_in"))
      (node (ref "X5") (pin "G@1") (pinfunction "GND_G@1") (pintype "power_in"))
      (node (ref "X6") (pin "1") (pinfunction "1_1") (pintype "bidirectional"))
      (node (ref "X6") (pin "2") (pinfunction "1_2") (pintype "bidirectional"))
      (node (ref "X6") (pin "3") (pinfunction "1_3") (pintype "bidirectional"))
      (node (ref "X6") (pin "4") (pinfunction "1_4") (pintype "bidirectional"))
      (node (ref "X7") (pin "G@1") (pinfunction "GND_G@1") (pintype "power_in"))
      (node (ref "X8") (pin "S1") (pinfunction "S1_S1") (pintype "passive"))
      (node (ref "X8") (pin "S2") (pinfunction "S2_S2") (pintype "passive"))
      (node (ref "XTAL1") (pin "2") (pinfunction "GND_2") (pintype "bidirectional"))
    )
    (net (code "37") (name "HOLDOFF_TRIG") (class "Default")
      (node (ref "IC15") (pin "1") (pinfunction "CLK_1") (pintype "bidirectional"))
      (node (ref "U3") (pin "7") (pinfunction "Q_7") (pintype "output"))
    )
    (net (code "38") (name "LDO_N10V0_FB_CH1") (class "Default")
      (node (ref "C41") (pin "2") (pinfunction "2_2") (pintype "passive"))
      (node (ref "IC9") (pin "2") (pinfunction "FB_2") (pintype "bidirectional"))
      (node (ref "R32") (pin "1") (pinfunction "1_1") (pintype "passive"))
      (node (ref "R34") (pin "1") (pinfunction "1_1") (pintype "passive"))
    )
    (net (code "39") (name "LDO_N10V0_NR_SS_CH1") (class "Default")
      (node (ref "C54") (pin "1") (pinfunction "1_1") (pintype "passive"))
      (node (ref "IC9") (pin "6") (pinfunction "NR/SS_6") (pintype "bidirectional"))
    )
    (net (code "40") (name "LDO_P5V0_FB_CH1") (class "Default")
      (node (ref "C5") (pin "2") (pinfunction "2_2") (pintype "passive"))
      (node (ref "IC1") (pin "2") (pinfunction "FB_2") (pintype "bidirectional"))
      (node (ref "R1") (pin "1") (pinfunction "1_1") (pintype "passive"))
      (node (ref "R10") (pin "1") (pinfunction "1_1") (pintype "passive"))
    )
    (net (code "41") (name "LDO_P5V0_NR_SS_CH1") (class "Default")
      (node (ref "C1") (pin "1") (pinfunction "1_1") (pintype "passive"))
      (node (ref "IC1") (pin "6") (pinfunction "NR/SS_6") (pintype "bidirectional"))
    )
    (net (code "42") (name "LDO_P10V0_FB_CH1") (class "Default")
      (node (ref "C6") (pin "2") (pinfunction "2_2") (pintype "passive"))
      (node (ref "IC2") (pin "2") (pinfunction "FB_2") (pintype "bidirectional"))
      (node (ref "R11") (pin "1") (pinfunction "1_1") (pintype "passive"))
      (node (ref "R2") (pin "1") (pinfunction "1_1") (pintype "passive"))
    )
    (net (code "43") (name "LDO_P10V0_NR_SS_CH1") (class "Default")
      (node (ref "C2") (pin "1") (pinfunction "1_1") (pintype "passive"))
      (node (ref "IC2") (pin "6") (pinfunction "NR/SS_6") (pintype "bidirectional"))
    )
    (net (code "44") (name "LOGIC_QUENCH") (class "Default")
      (node (ref "IC13") (pin "4") (pinfunction "B_4") (pintype "passive"))
      (node (ref "IC15") (pin "5") (pinfunction "Q_5") (pintype "bidirectional"))
      (node (ref "TP13") (pin "TP") (pinfunction "TP_TP") (pintype "input"))
    )
    (net (code "45") (name "LOGIC_QUENCH_BUF") (class "Default")
      (node (ref "IC16") (pin "4") (pinfunction "O_4") (pintype "output"))
      (node (ref "IC20") (pin "1") (pinfunction "IN1_1") (pintype "bidirectional"))
      (node (ref "IC20") (pin "3") (pinfunction "IN2_3") (pintype "bidirectional"))
      (node (ref "IC22") (pin "2") (pinfunction "I1_2") (pintype "input"))
      (node (ref "IC7") (pin "1") (pinfunction "IN_1") (pintype "bidirectional"))
      (node (ref "R40") (pin "2") (pinfunction "2_2") (pintype "passive"))
    )
    (net (code "46") (name "MCU_AQC_RLY") (class "Default")
      (node (ref "IC30") (pin "34") (pinfunction "PB13/I2S2_CK_34") (pintype "bidirectional"))
      (node (ref "R76") (pin "2") (pinfunction "2_2") (pintype "passive"))
    )
    (net (code "47") (name "MCU_BOOT0") (class "Default")
      (node (ref "IC30") (pin "60") (pinfunction "BOOT0_60") (pintype "bidirectional"))
      (node (ref "R69") (pin "2") (pinfunction "2_2") (pintype "passive"))
      (node (ref "R71") (pin "1") (pinfunction "1_1") (pintype "passive"))
    )
    (net (code "48") (name "MCU_BOOT1") (class "Default")
      (node (ref "IC30") (pin "28") (pinfunction "PB2-BOOT1_28") (pintype "bidirectional"))
      (node (ref "R66") (pin "2") (pinfunction "2_2") (pintype "passive"))
      (node (ref "R72") (pin "1") (pinfunction "1_1") (pintype "passive"))
    )
    (net (code "49") (name "MCU_IVTEST_RLY") (class "Default")
      (node (ref "IC30") (pin "33") (pinfunction "PB12/I2S2_WS_33") (pintype "bidirectional"))
      (node (ref "R75") (pin "2") (pinfunction "2_2") (pintype "passive"))
    )
    (net (code "50") (name "MCU_JTCK") (class "Default")
      (node (ref "IC30") (pin "49") (pinfunction "PA14/JTCK_49") (pintype "bidirectional"))
      (node (ref "PROG") (pin "2") (pinfunction "2_2") (pintype "bidirectional"))
    )
    (net (code "51") (name "MCU_JTDO") (class "Default")
      (node (ref "IC30") (pin "55") (pinfunction "PB3/JTDO_55") (pintype "bidirectional"))
      (node (ref "PROG") (pin "6") (pinfunction "6_6") (pintype "bidirectional"))
    )
    (net (code "52") (name "MCU_JTMS") (class "Default")
      (node (ref "IC30") (pin "46") (pinfunction "PA13/JTMS_46") (pintype "bidirectional"))
      (node (ref "PROG") (pin "4") (pinfunction "4_4") (pintype "bidirectional"))
    )
    (net (code "53") (name "MCU_LED1") (class "Default")
      (node (ref "IC30") (pin "8") (pinfunction "PC0_8") (pintype "bidirectional"))
      (node (ref "R65") (pin "2") (pinfunction "2_2") (pintype "passive"))
    )
    (net (code "54") (name "MCU_LED2") (class "Default")
      (node (ref "IC30") (pin "9") (pinfunction "PC1_9") (pintype "bidirectional"))
      (node (ref "R60") (pin "2") (pinfunction "2_2") (pintype "passive"))
    )
    (net (code "55") (name "MCU_LED3") (class "Default")
      (node (ref "IC30") (pin "10") (pinfunction "PC2_10") (pintype "bidirectional"))
      (node (ref "R55") (pin "2") (pinfunction "2_2") (pintype "passive"))
    )
    (net (code "56") (name "MCU_NRST") (class "Default")
      (node (ref "C82") (pin "1") (pinfunction "1_1") (pintype "passive"))
      (node (ref "IC30") (pin "7") (pinfunction "NRST_7") (pintype "bidirectional"))
      (node (ref "PROG") (pin "5") (pinfunction "5_5") (pintype "bidirectional"))
      (node (ref "SW1") (pin "3") (pinfunction "P$2_3") (pintype "bidirectional"))
      (node (ref "SW1") (pin "4") (pinfunction "P$2_4") (pintype "bidirectional"))
    )
    (net (code "57") (name "MCU_OSC_IN") (class "Default")
      (node (ref "IC30") (pin "5") (pinfunction "PH0/OSC_IN_5") (pintype "bidirectional"))
      (node (ref "XTAL1") (pin "1") (pinfunction "LEFT_1") (pintype "bidirectional"))
    )
    (net (code "58") (name "MCU_OSC_OUT") (class "Default")
      (node (ref "IC30") (pin "6") (pinfunction "PH1/OSC_OUT_6") (pintype "bidirectional"))
      (node (ref "XTAL1") (pin "3") (pinfunction "RIGHT_3") (pintype "bidirectional"))
    )
    (net (code "59") (name "MCU_PB11") (class "Default")
      (node (ref "C104") (pin "1") (pinfunction "1_1") (pintype "passive"))
      (node (ref "IC30") (pin "30") (pinfunction "PB11_30") (pintype "bidirectional"))
    )
    (net (code "60") (name "MCU_TIM2_CH1_IN") (class "Default")
      (node (ref "IC30") (pin "14") (pinfunction "PA0_14") (pintype "bidirectional"))
      (node (ref "R40") (pin "1") (pinfunction "1_1") (pintype "passive"))
    )
    (net (code "61") (name "MCU_TIM2_CH1_OUT_1") (class "Default")
      (node (ref "IC21") (pin "1") (pinfunction "I0_1") (pintype "input"))
      (node (ref "IC30") (pin "21") (pinfunction "PA5/SPI1_SCK_21") (pintype "bidirectional"))
    )
    (net (code "62") (name "MCU_TIM2_CH1_OUT_2") (class "Default")
      (node (ref "IC19") (pin "2") (pinfunction "I1_2") (pintype "input"))
      (node (ref "IC30") (pin "50") (pinfunction "PA15/JTDI_50") (pintype "bidirectional"))
    )
    (net (code "63") (name "MCU_USB_FS_D_N") (class "Default")
      (node (ref "C101") (pin "1") (pinfunction "1_1") (pintype "passive"))
      (node (ref "IC30") (pin "44") (pinfunction "PA11_44") (pintype "bidirectional"))
      (node (ref "R70") (pin "1") (pinfunction "1_1") (pintype "passive"))
    )
    (net (code "64") (name "MCU_USB_FS_D_P") (class "Default")
      (node (ref "C98") (pin "1") (pinfunction "1_1") (pintype "passive"))
      (node (ref "IC30") (pin "45") (pinfunction "PA12_45") (pintype "bidirectional"))
      (node (ref "R67") (pin "1") (pinfunction "1_1") (pintype "passive"))
    )
    (net (code "65") (name "MCU_VCAP_1") (class "Default")
      (node (ref "IC30") (pin "31") (pinfunction "VCAP_1_31") (pintype "bidirectional"))
      (node (ref "R74") (pin "1") (pinfunction "1_1") (pintype "passive"))
    )
    (net (code "66") (name "MCU_VCAP_2") (class "Default")
      (node (ref "C112") (pin "1") (pinfunction "1_1") (pintype "passive"))
      (node (ref "IC30") (pin "47") (pinfunction "VCAP_2_47") (pintype "bidirectional"))
    )
    (net (code "67") (name "NC_DAC1_IRQ") (class "Default")
      (node (ref "IC31") (pin "16") (pinfunction "~{IRQ}_16") (pintype "bidirectional"))
    )
    (net (code "68") (name "NC_ONE_SHOT_CLR") (class "Default")
      (node (ref "IC14") (pin "8") (pinfunction "~{Q}_8") (pintype "bidirectional"))
    )
    (net (code "69") (name "Net-(C3-Pad2)") (class "Default")
      (node (ref "C3") (pin "2") (pinfunction "2_2") (pintype "passive"))
      (node (ref "R7") (pin "2") (pinfunction "2_2") (pintype "passive"))
    )
    (net (code "70") (name "Net-(C13-Pad+)") (class "Default")
      (node (ref "C13") (pin "+") (pinfunction "+_+") (pintype "passive"))
      (node (ref "C14") (pin "+") (pinfunction "+_+") (pintype "passive"))
      (node (ref "D1") (pin "C") (pinfunction "C_C") (pintype "passive"))
      (node (ref "L3") (pin "1") (pinfunction "1_1") (pintype "bidirectional"))
      (node (ref "R4") (pin "1") (pinfunction "1_1") (pintype "passive"))
      (node (ref "R9") (pin "1") (pinfunction "1_1") (pintype "passive"))
    )
    (net (code "71") (name "Net-(C18-Pad1)") (class "Default")
      (node (ref "C18") (pin "1") (pinfunction "1_1") (pintype "passive"))
      (node (ref "R16") (pin "1") (pinfunction "1_1") (pintype "passive"))
    )
    (net (code "72") (name "Net-(C31-Pad1)") (class "Default")
      (node (ref "C31") (pin "1") (pinfunction "1_1") (pintype "passive"))
      (node (ref "R29") (pin "2") (pinfunction "2_2") (pintype "passive"))
    )
    (net (code "73") (name "Net-(C42-Pad-)") (class "Default")
      (node (ref "C42") (pin "-") (pinfunction "-_-") (pintype "passive"))
      (node (ref "C71") (pin "1") (pinfunction "1_1") (pintype "passive"))
      (node (ref "D2") (pin "A") (pinfunction "A_A") (pintype "passive"))
      (node (ref "L6") (pin "4") (pinfunction "4_4") (pintype "bidirectional"))
    )
    (net (code "74") (name "Net-(C68-Pad1)") (class "Default")
      (node (ref "C68") (pin "1") (pinfunction "1_1") (pintype "passive"))
      (node (ref "R45") (pin "1") (pinfunction "1_1") (pintype "passive"))
    )
    (net (code "75") (name "Net-(D4-A)") (class "Default")
      (node (ref "D4") (pin "1") (pinfunction "A_1") (pintype "passive"))
      (node (ref "M1") (pin "3") (pinfunction "D_3") (pintype "passive"))
      (node (ref "RLY2") (pin "2") (pinfunction "PIN2_2") (pintype "bidirectional"))
    )
    (net (code "76") (name "Net-(D5-A)") (class "Default")
      (node (ref "D5") (pin "1") (pinfunction "A_1") (pintype "passive"))
      (node (ref "M2") (pin "3") (pinfunction "D_3") (pintype "passive"))
      (node (ref "RLY1") (pin "2") (pinfunction "PIN2_2") (pintype "bidirectional"))
    )
    (net (code "77") (name "Net-(IC3-COL)") (class "Default")
      (node (ref "D1") (pin "A") (pinfunction "A_A") (pintype "passive"))
      (node (ref "IC3") (pin "2") (pinfunction "COL_2") (pintype "bidirectional"))
      (node (ref "L2") (pin "2") (pinfunction "P$2_2") (pintype "bidirectional"))
      (node (ref "R7") (pin "1") (pinfunction "1_1") (pintype "passive"))
    )
    (net (code "78") (name "Net-(IC3-CT)") (class "Default")
      (node (ref "C4") (pin "1") (pinfunction "1_1") (pintype "passive"))
      (node (ref "IC3") (pin "5") (pinfunction "CT_5") (pintype "bidirectional"))
    )
    (net (code "79") (name "Net-(IC3-FB)") (class "Default")
      (node (ref "IC3") (pin "7") (pinfunction "FB_7") (pintype "bidirectional"))
      (node (ref "R5") (pin "1") (pinfunction "1_1") (pintype "passive"))
      (node (ref "R6") (pin "1") (pinfunction "1_1") (pintype "passive"))
    )
    (net (code "80") (name "Net-(IC3-PGND)") (class "Default")
      (node (ref "IC3") (pin "3") (pinfunction "PGND_3") (pintype "bidirectional"))
      (node (ref "L1") (pin "1") (pinfunction "P$1_1") (pintype "bidirectional"))
    )
    (net (code "81") (name "Net-(IC3-RCSL)") (class "Default")
      (node (ref "IC3") (pin "13") (pinfunction "RCSL_13") (pintype "bidirectional"))
      (node (ref "R15") (pin "1") (pinfunction "1_1") (pintype "passive"))
    )
    (net (code "82") (name "Net-(IC3-RT)") (class "Default")
      (node (ref "IC3") (pin "6") (pinfunction "RT_6") (pintype "bidirectional"))
      (node (ref "R8") (pin "2") (pinfunction "2_2") (pintype "passive"))
    )
    (net (code "83") (name "Net-(IC3-RVSL)") (class "Default")
      (node (ref "IC3") (pin "14") (pinfunction "RVSL_14") (pintype "bidirectional"))
      (node (ref "R14") (pin "1") (pinfunction "1_1") (pintype "passive"))
    )
    (net (code "84") (name "Net-(IC3-VC)") (class "Default")
      (node (ref "C19") (pin "1") (pinfunction "1_1") (pintype "passive"))
      (node (ref "IC3") (pin "11") (pinfunction "VC_11") (pintype "bidirectional"))
      (node (ref "R16") (pin "2") (pinfunction "2_2") (pintype "passive"))
    )
    (net (code "85") (name "Net-(IC4-HYS)") (class "Default")
      (node (ref "IC4") (pin "14") (pinfunction "HYS_14") (pintype "bidirectional"))
      (node (ref "R36") (pin "2") (pinfunction "2_2") (pintype "passive"))
    )
    (net (code "86") (name "Net-(IC4-VTN)") (class "Default")
      (node (ref "IC4") (pin "4") (pinfunction "VTN_4") (pintype "bidirectional"))
      (node (ref "R21") (pin "2") (pinfunction "2_2") (pintype "passive"))
    )
    (net (code "87") (name "Net-(IC4-VTT)") (class "Default")
      (node (ref "IC4") (pin "8") (pinfunction "VTT_8") (pintype "bidirectional"))
      (node (ref "R20") (pin "1") (pinfunction "1_1") (pintype "passive"))
    )
    (net (code "88") (name "Net-(IC7-TAP1)") (class "Default")
      (node (ref "IC7") (pin "7") (pinfunction "TAP1_7") (pintype "bidirectional"))
      (node (ref "R28") (pin "2") (pinfunction "2_2") (pintype "passive"))
    )
    (net (code "89") (name "Net-(IC7-TAP2)") (class "Default")
      (node (ref "IC7") (pin "2") (pinfunction "TAP2_2") (pintype "bidirectional"))
      (node (ref "R24") (pin "2") (pinfunction "2_2") (pintype "passive"))
    )
    (net (code "90") (name "Net-(IC7-TAP3)") (class "Default")
      (node (ref "IC7") (pin "6") (pinfunction "TAP3_6") (pintype "bidirectional"))
      (node (ref "R26") (pin "2") (pinfunction "2_2") (pintype "passive"))
    )
    (net (code "91") (name "Net-(IC7-TAP4)") (class "Default")
      (node (ref "IC7") (pin "3") (pinfunction "TAP4_3") (pintype "bidirectional"))
      (node (ref "R25") (pin "2") (pinfunction "2_2") (pintype "passive"))
    )
    (net (code "92") (name "Net-(IC7-TAP5)") (class "Default")
      (node (ref "IC7") (pin "5") (pinfunction "TAP5_5") (pintype "bidirectional"))
      (node (ref "R27") (pin "2") (pinfunction "2_2") (pintype "passive"))
    )
    (net (code "93") (name "Net-(IC10-COL)") (class "Default")
      (node (ref "C42") (pin "+") (pinfunction "+_+") (pintype "passive"))
      (node (ref "IC10") (pin "2") (pinfunction "COL_2") (pintype "bidirectional"))
      (node (ref "L6") (pin "3") (pinfunction "3_3") (pintype "bidirectional"))
      (node (ref "R29") (pin "1") (pinfunction "1_1") (pintype "passive"))
    )
    (net (code "94") (name "Net-(IC10-CT)") (class "Default")
      (node (ref "C32") (pin "1") (pinfunction "1_1") (pintype "passive"))
      (node (ref "IC10") (pin "5") (pinfunction "CT_5") (pintype "bidirectional"))
    )
    (net (code "95") (name "Net-(IC10-NFB)") (class "Default")
      (node (ref "IC10") (pin "10") (pinfunction "NFB_10") (pintype "bidirectional"))
      (node (ref "R41") (pin "2") (pinfunction "2_2") (pintype "passive"))
      (node (ref "R48") (pin "1") (pinfunction "1_1") (pintype "passive"))
    )
    (net (code "96") (name "Net-(IC10-PGND)") (class "Default")
      (node (ref "IC10") (pin "3") (pinfunction "PGND_3") (pintype "bidirectional"))
      (node (ref "L5") (pin "1") (pinfunction "P$1_1") (pintype "bidirectional"))
    )
    (net (code "97") (name "Net-(IC10-RCSL)") (class "Default")
      (node (ref "IC10") (pin "13") (pinfunction "RCSL_13") (pintype "bidirectional"))
      (node (ref "R44") (pin "1") (pinfunction "1_1") (pintype "passive"))
    )
    (net (code "98") (name "Net-(IC10-RT)") (class "Default")
      (node (ref "IC10") (pin "6") (pinfunction "RT_6") (pintype "bidirectional"))
      (node (ref "R30") (pin "2") (pinfunction "2_2") (pintype "passive"))
    )
    (net (code "99") (name "Net-(IC10-RVSL)") (class "Default")
      (node (ref "IC10") (pin "14") (pinfunction "RVSL_14") (pintype "bidirectional"))
      (node (ref "R43") (pin "1") (pinfunction "1_1") (pintype "passive"))
    )
    (net (code "100") (name "Net-(IC10-VC)") (class "Default")
      (node (ref "C69") (pin "1") (pinfunction "1_1") (pintype "passive"))
      (node (ref "IC10") (pin "11") (pinfunction "VC_11") (pintype "bidirectional"))
      (node (ref "R45") (pin "2") (pinfunction "2_2") (pintype "passive"))
    )
    (net (code "101") (name "Net-(IC14-+IN)") (class "Default")
      (node (ref "C72") (pin "1") (pinfunction "1_1") (pintype "passive"))
      (node (ref "IC14") (pin "2") (pinfunction "+IN_2") (pintype "bidirectional"))
      (node (ref "R47") (pin "1") (pinfunction "1_1") (pintype "passive"))
    )
    (net (code "102") (name "Net-(IC14--IN)") (class "Default")
      (node (ref "C72") (pin "2") (pinfunction "2_2") (pintype "passive"))
      (node (ref "IC14") (pin "3") (pinfunction "-IN_3") (pintype "bidirectional"))
      (node (ref "R51") (pin "1") (pinfunction "1_1") (pintype "passive"))
    )
    (net (code "103") (name "Net-(IC20-OUT1)") (class "Default")
      (node (ref "IC20") (pin "4") (pinfunction "OUT2_4") (pintype "bidirectional"))
      (node (ref "IC20") (pin "6") (pinfunction "OUT1_6") (pintype "bidirectional"))
      (node (ref "R52") (pin "2") (pinfunction "2_2") (pintype "passive"))
    )
    (net (code "104") (name "Net-(IC24A-OUT)") (class "Default")
      (node (ref "IC24") (pin "1") (pinfunction "OUT_1") (pintype "output"))
      (node (ref "T1") (pin "B") (pinfunction "B_B") (pintype "passive"))
    )
    (net (code "105") (name "Net-(IC24B--IN)") (class "Default")
      (node (ref "IC24") (pin "6") (pinfunction "-IN_6") (pintype "input"))
      (node (ref "R56") (pin "1") (pinfunction "1_1") (pintype "passive"))
      (node (ref "R57") (pin "2") (pinfunction "2_2") (pintype "passive"))
    )
    (net (code "106") (name "Net-(IC24B-OUT)") (class "Default")
      (node (ref "IC24") (pin "7") (pinfunction "OUT_7") (pintype "output"))
      (node (ref "R51") (pin "2") (pinfunction "2_2") (pintype "passive"))
      (node (ref "R57") (pin "1") (pinfunction "1_1") (pintype "passive"))
    )
    (net (code "107") (name "Net-(IC25A-B)") (class "Default")
      (node (ref "IC25") (pin "1") (pinfunction "C_1") (pintype "passive"))
      (node (ref "IC25") (pin "10") (pinfunction "E_10") (pintype "passive"))
      (node (ref "IC25") (pin "13") (pinfunction "B_13") (pintype "passive"))
      (node (ref "IC25") (pin "2") (pinfunction "B_2") (pintype "passive"))
    )
    (net (code "108") (name "Net-(IC25B-C)") (class "Default")
      (node (ref "IC25") (pin "14") (pinfunction "C_14") (pintype "passive"))
      (node (ref "IC25") (pin "5") (pinfunction "E_5") (pintype "passive"))
    )
    (net (code "109") (name "Net-(IC27A-C)") (class "Default")
      (node (ref "IC27") (pin "6") (pinfunction "C_6") (pintype "passive"))
      (node (ref "IC5") (pin "2") (pinfunction "E_2") (pintype "passive"))
    )
    (net (code "110") (name "Net-(IC27B-C)") (class "Default")
      (node (ref "IC27") (pin "3") (pinfunction "C_3") (pintype "passive"))
      (node (ref "IC5") (pin "5") (pinfunction "E_5") (pintype "passive"))
    )
    (net (code "111") (name "Net-(IC31-REF)") (class "Default")
      (node (ref "IC31") (pin "1") (pinfunction "REF_1") (pintype "bidirectional"))
      (node (ref "R73") (pin "2") (pinfunction "2_2") (pintype "passive"))
    )
    (net (code "112") (name "Net-(L3-Pad2)") (class "Default")
      (node (ref "L3") (pin "2") (pinfunction "2_2") (pintype "bidirectional"))
      (node (ref "L3") (pin "3") (pinfunction "3_3") (pintype "bidirectional"))
    )
    (net (code "113") (name "Net-(LED1-PadBOT_A)") (class "Default")
      (node (ref "LED1") (pin "BOT_A") (pinfunction "BOT_A_BOT_A") (pintype "bidirectional"))
      (node (ref "R55") (pin "1") (pinfunction "1_1") (pintype "passive"))
    )
    (net (code "114") (name "Net-(LED1-PadMID_A)") (class "Default")
      (node (ref "LED1") (pin "MID_A") (pinfunction "MID_A_MID_A") (pintype "bidirectional"))
      (node (ref "R60") (pin "1") (pinfunction "1_1") (pintype "passive"))
    )
    (net (code "115") (name "Net-(LED1-PadTOP_A)") (class "Default")
      (node (ref "LED1") (pin "TOP_A") (pinfunction "TOP_A_TOP_A") (pintype "bidirectional"))
      (node (ref "R65") (pin "1") (pinfunction "1_1") (pintype "passive"))
    )
    (net (code "116") (name "Net-(M1-G)") (class "Default")
      (node (ref "M1") (pin "1") (pinfunction "G_1") (pintype "passive"))
      (node (ref "R75") (pin "1") (pinfunction "1_1") (pintype "passive"))
    )
    (net (code "117") (name "Net-(M2-G)") (class "Default")
      (node (ref "M2") (pin "1") (pinfunction "G_1") (pintype "passive"))
      (node (ref "R76") (pin "1") (pinfunction "1_1") (pintype "passive"))
    )
    (net (code "118") (name "Net-(Q1-G)") (class "Default")
      (node (ref "C79") (pin "1") (pinfunction "1_1") (pintype "passive"))
      (node (ref "Q1") (pin "1") (pinfunction "G_1") (pintype "passive"))
      (node (ref "R58") (pin "1") (pinfunction "1_1") (pintype "passive"))
      (node (ref "R62") (pin "1") (pinfunction "1_1") (pintype "passive"))
    )
    (net (code "119") (name "Net-(R3-Pad2)") (class "Default")
      (node (ref "R3") (pin "2") (pinfunction "2_2") (pintype "passive"))
      (node (ref "R4") (pin "2") (pinfunction "2_2") (pintype "passive"))
      (node (ref "R5") (pin "2") (pinfunction "2_2") (pintype "passive"))
    )
    (net (code "120") (name "Net-(R52-Pad1)") (class "Default")
      (node (ref "R52") (pin "1") (pinfunction "1_1") (pintype "passive"))
      (node (ref "X5") (pin "1") (pinfunction "1_1") (pintype "passive"))
    )
    (net (code "121") (name "Net-(U1-VOUT)") (class "Default")
      (node (ref "R18") (pin "2") (pinfunction "2_2") (pintype "passive"))
      (node (ref "U1") (pin "1") (pinfunction "VOUT_1") (pintype "output"))
    )
    (net (code "122") (name "ONE_SHOT_CAP") (class "Default")
      (node (ref "C70") (pin "1") (pinfunction "1_1") (pintype "passive"))
      (node (ref "IC17") (pin "4") (pinfunction "O_4") (pintype "tri_state"))
      (node (ref "R47") (pin "2") (pinfunction "2_2") (pintype "passive"))
      (node (ref "T1") (pin "C") (pinfunction "C_C") (pintype "passive"))
    )
    (net (code "123") (name "ONE_SHOT_FB") (class "Default")
      (node (ref "R53") (pin "1") (pinfunction "1_1") (pintype "passive"))
      (node (ref "R54") (pin "1") (pinfunction "1_1") (pintype "passive"))
      (node (ref "T1") (pin "E") (pinfunction "E_E") (pintype "passive"))
    )
    (net (code "124") (name "ONE_SHOT_VGND") (class "Default")
      (node (ref "IC24") (pin "2") (pinfunction "-IN_2") (pintype "input"))
      (node (ref "R53") (pin "2") (pinfunction "2_2") (pintype "passive"))
      (node (ref "R61") (pin "1") (pinfunction "1_1") (pintype "passive"))
    )
    (net (code "125") (name "PP_N5V0_ANALOG") (class "Default")
      (node (ref "C37") (pin "1") (pinfunction "1_1") (pintype "passive"))
      (node (ref "C38") (pin "1") (pinfunction "1_1") (pintype "passive"))
      (node (ref "C39") (pin "1") (pinfunction "1_1") (pintype "passive"))
      (node (ref "C41") (pin "1") (pinfunction "1_1") (pintype "passive"))
      (node (ref "C46") (pin "1") (pinfunction "1_1") (pintype "passive"))
      (node (ref "C55") (pin "1") (pinfunction "1_1") (pintype "passive"))
      (node (ref "C62") (pin "1") (pinfunction "1_1") (pintype "passive"))
      (node (ref "C80") (pin "1") (pinfunction "1_1") (pintype "passive"))
      (node (ref "C94") (pin "1") (pinfunction "1_1") (pintype "passive"))
      (node (ref "IC14") (pin "4") (pinfunction "V-_4") (pintype "bidirectional"))
      (node (ref "IC24") (pin "4") (pinfunction "V-_4") (pintype "power_in"))
      (node (ref "IC26") (pin "4") (pinfunction "V-_4") (pintype "power_in"))
      (node (ref "IC4") (pin "13") (pinfunction "VEE_13") (pintype "bidirectional"))
      (node (ref "IC9") (pin "1") (pinfunction "OUT_1") (pintype "bidirectional"))
      (node (ref "R32") (pin "2") (pinfunction "2_2") (pintype "passive"))
      (node (ref "R36") (pin "1") (pinfunction "1_1") (pintype "passive"))
      (node (ref "R54") (pin "2") (pinfunction "2_2") (pintype "passive"))
      (node (ref "R63") (pin "1") (pinfunction "1_1") (pintype "passive"))
      (node (ref "TP11") (pin "TP") (pinfunction "TP_TP") (pintype "input"))
    )
    (net (code "126") (name "PP_N6V0_CUK") (class "Default")
      (node (ref "C53") (pin "1") (pinfunction "1_1") (pintype "passive"))
      (node (ref "C56") (pin "1") (pinfunction "1_1") (pintype "passive"))
      (node (ref "IC9") (pin "5") (pinfunction "EN_5") (pintype "bidirectional"))
      (node (ref "IC9") (pin "8") (pinfunction "IN_8") (pintype "bidirectional"))
      (node (ref "L6") (pin "2") (pinfunction "2_2") (pintype "bidirectional"))
      (node (ref "R41") (pin "1") (pinfunction "1_1") (pintype "passive"))
    )
    (net (code "127") (name "PP_P3V3") (class "Default")
      (node (ref "C106") (pin "1") (pinfunction "1_1") (pintype "passive"))
      (node (ref "C109") (pin "1") (pinfunction "1_1") (pintype "passive"))
      (node (ref "C110") (pin "1") (pinfunction "1_1") (pintype "passive"))
      (node (ref "C111") (pin "1") (pinfunction "1_1") (pintype "passive"))
      (node (ref "C16") (pin "1") (pinfunction "1_1") (pintype "passive"))
      (node (ref "C21") (pin "1") (pinfunction "1_1") (pintype "passive"))
      (node (ref "C23") (pin "1") (pinfunction "1_1") (pintype "passive"))
      (node (ref "C28") (pin "1") (pinfunction "1_1") (pintype "passive"))
      (node (ref "C35") (pin "1") (pinfunction "1_1") (pintype "passive"))
      (node (ref "C43") (pin "1") (pinfunction "1_1") (pintype "passive"))
      (node (ref "C44") (pin "1") (pinfunction "1_1") (pintype "passive"))
      (node (ref "C48") (pin "1") (pinfunction "1_1") (pintype "passive"))
      (node (ref "C49") (pin "1") (pinfunction "1_1") (pintype "passive"))
      (node (ref "C58") (pin "1") (pinfunction "1_1") (pintype "passive"))
      (node (ref "C59") (pin "1") (pinfunction "1_1") (pintype "passive"))
      (node (ref "C60") (pin "1") (pinfunction "1_1") (pintype "passive"))
      (node (ref "C61") (pin "1") (pinfunction "1_1") (pintype "passive"))
      (node (ref "C63") (pin "1") (pinfunction "1_1") (pintype "passive"))
      (node (ref "C64") (pin "1") (pinfunction "1_1") (pintype "passive"))
      (node (ref "C65") (pin "1") (pinfunction "1_1") (pintype "passive"))
      (node (ref "C66") (pin "1") (pinfunction "1_1") (pintype "passive"))
      (node (ref "C73") (pin "1") (pinfunction "1_1") (pintype "passive"))
      (node (ref "C74") (pin "1") (pinfunction "1_1") (pintype "passive"))
      (node (ref "C81") (pin "1") (pinfunction "1_1") (pintype "passive"))
      (node (ref "C83") (pin "1") (pinfunction "1_1") (pintype "passive"))
      (node (ref "C84") (pin "1") (pinfunction "1_1") (pintype "passive"))
      (node (ref "C85") (pin "1") (pinfunction "1_1") (pintype "passive"))
      (node (ref "C87") (pin "1") (pinfunction "1_1") (pintype "passive"))
      (node (ref "C89") (pin "1") (pinfunction "1_1") (pintype "passive"))
      (node (ref "C90") (pin "1") (pinfunction "1_1") (pintype "passive"))
      (node (ref "C91") (pin "1") (pinfunction "1_1") (pintype "passive"))
      (node (ref "C95") (pin "1") (pinfunction "1_1") (pintype "passive"))
      (node (ref "C96") (pin "1") (pinfunction "1_1") (pintype "passive"))
      (node (ref "C97") (pin "1") (pinfunction "1_1") (pintype "passive"))
      (node (ref "C99") (pin "1") (pinfunction "1_1") (pintype "passive"))
      (node (ref "IC15") (pin "2") (pinfunction "D_2") (pintype "bidirectional"))
      (node (ref "IC15") (pin "8") (pinfunction "VDD_8") (pintype "bidirectional"))
      (node (ref "IC16") (pin "5") (pinfunction "VCC_5") (pintype "power_in"))
      (node (ref "IC17") (pin "2") (pinfunction "I_2") (pintype "input"))
      (node (ref "IC17") (pin "5") (pinfunction "VCC_5") (pintype "power_in"))
      (node (ref "IC18") (pin "5") (pinfunction "VCC_5") (pintype "power_in"))
      (node (ref "IC19") (pin "5") (pinfunction "VCC_5") (pintype "power_in"))
      (node (ref "IC20") (pin "5") (pinfunction "VCC_5") (pintype "bidirectional"))
      (node (ref "IC21") (pin "5") (pinfunction "VCC_5") (pintype "power_in"))
      (node (ref "IC22") (pin "5") (pinfunction "VCC_5") (pintype "power_in"))
      (node (ref "IC29") (pin "5") (pinfunction "VBUS_5") (pintype "bidirectional"))
      (node (ref "IC30") (pin "1") (pinfunction "VBAT_1") (pintype "bidirectional"))
      (node (ref "IC30") (pin "19") (pinfunction "VDD1_19") (pintype "bidirectional"))
      (node (ref "IC30") (pin "32") (pinfunction "VDD2_32") (pintype "bidirectional"))
      (node (ref "IC30") (pin "48") (pinfunction "VDD3_48") (pintype "bidirectional"))
      (node (ref "IC30") (pin "64") (pinfunction "VDD4_64") (pintype "bidirectional"))
      (node (ref "IC31") (pin "11") (pinfunction "VDDIO_11") (pintype "bidirectional"))
      (node (ref "IC31") (pin "18") (pinfunction "~{LDAC}_18") (pintype "bidirectional"))
      (node (ref "IC32") (pin "2") (pinfunction "OUT_2") (pintype "bidirectional"))
      (node (ref "IC32") (pin "4") (pinfunction "TAB_4") (pintype "bidirectional"))
      (node (ref "IC4") (pin "12") (pinfunction "VCCO_12") (pintype "bidirectional"))
      (node (ref "IC4") (pin "9") (pinfunction "VCCO_9") (pintype "bidirectional"))
      (node (ref "IC7") (pin "8") (pinfunction "VCC_8") (pintype "bidirectional"))
      (node (ref "L4") (pin "1") (pinfunction "P$1_1") (pintype "bidirectional"))
      (node (ref "L7") (pin "1") (pinfunction "P$1_1") (pintype "bidirectional"))
      (node (ref "PROG") (pin "1") (pinfunction "1_1") (pintype "bidirectional"))
      (node (ref "R12") (pin "1") (pinfunction "1_1") (pintype "passive"))
      (node (ref "R13") (pin "1") (pinfunction "1_1") (pintype "passive"))
      (node (ref "R66") (pin "1") (pinfunction "1_1") (pintype "passive"))
      (node (ref "R69") (pin "1") (pinfunction "1_1") (pintype "passive"))
      (node (ref "TP23") (pin "TP") (pinfunction "TP_TP") (pintype "input"))
      (node (ref "U2") (pin "8") (pinfunction "VCC_8") (pintype "power_in"))
      (node (ref "U3") (pin "8") (pinfunction "VCC_8") (pintype "power_in"))
    )
    (net (code "128") (name "PP_P3V3_AV_DET_DAC") (class "Default")
      (node (ref "C20") (pin "1") (pinfunction "1_1") (pintype "passive"))
      (node (ref "C22") (pin "1") (pinfunction "1_1") (pintype "passive"))
      (node (ref "L4") (pin "2") (pinfunction "P$2_2") (pintype "bidirectional"))
      (node (ref "R17") (pin "2") (pinfunction "2_2") (pintype "passive"))
      (node (ref "U1") (pin "3") (pinfunction "VDD_3") (pintype "power_in"))
    )
    (net (code "129") (name "PP_P3V3_VDDA") (class "Default")
      (node (ref "C86") (pin "1") (pinfunction "1_1") (pintype "passive"))
      (node (ref "C92") (pin "1") (pinfunction "1_1") (pintype "passive"))
      (node (ref "IC30") (pin "13") (pinfunction "VDDA_13") (pintype "bidirectional"))
      (node (ref "L7") (pin "2") (pinfunction "P$2_2") (pintype "bidirectional"))
    )
    (net (code "130") (name "PP_P5V0_ANALOG") (class "Default")
      (node (ref "C100") (pin "1") (pinfunction "1_1") (pintype "passive"))
      (node (ref "C12") (pin "1") (pinfunction "1_1") (pintype "passive"))
      (node (ref "C24") (pin "1") (pinfunction "1_1") (pintype "passive"))
      (node (ref "C29") (pin "1") (pinfunction "1_1") (pintype "passive"))
      (node (ref "C30") (pin "1") (pinfunction "1_1") (pintype "passive"))
      (node (ref "C36") (pin "1") (pinfunction "1_1") (pintype "passive"))
      (node (ref "C40") (pin "1") (pinfunction "1_1") (pintype "passive"))
      (node (ref "C47") (pin "1") (pinfunction "1_1") (pintype "passive"))
      (node (ref "C5") (pin "1") (pinfunction "1_1") (pintype "passive"))
      (node (ref "C50") (pin "1") (pinfunction "1_1") (pintype "passive"))
      (node (ref "C77") (pin "1") (pinfunction "1_1") (pintype "passive"))
      (node (ref "C78") (pin "1") (pinfunction "1_1") (pintype "passive"))
      (node (ref "C88") (pin "1") (pinfunction "1_1") (pintype "passive"))
      (node (ref "C9") (pin "1") (pinfunction "1_1") (pintype "passive"))
      (node (ref "C93") (pin "1") (pinfunction "1_1") (pintype "passive"))
      (node (ref "IC1") (pin "1") (pinfunction "OUT_1") (pintype "bidirectional"))
      (node (ref "IC11") (pin "1") (pinfunction "B_1") (pintype "passive"))
      (node (ref "IC11") (pin "4") (pinfunction "B_4") (pintype "passive"))
      (node (ref "IC13") (pin "6") (pinfunction "C_6") (pintype "passive"))
      (node (ref "IC14") (pin "1") (pinfunction "V+_1") (pintype "bidirectional"))
      (node (ref "IC24") (pin "8") (pinfunction "V+_8") (pintype "power_in"))
      (node (ref "IC26") (pin "8") (pinfunction "V+_8") (pintype "power_in"))
      (node (ref "IC28") (pin "5") (pinfunction "V+_5") (pintype "power_in"))
      (node (ref "IC4") (pin "16") (pinfunction "VCCI_16") (pintype "bidirectional"))
      (node (ref "IC4") (pin "5") (pinfunction "VCCI_5") (pintype "bidirectional"))
      (node (ref "IC5") (pin "1") (pinfunction "B_1") (pintype "passive"))
      (node (ref "IC5") (pin "4") (pinfunction "B_4") (pintype "passive"))
      (node (ref "IC6") (pin "1") (pinfunction "B_1") (pintype "passive"))
      (node (ref "IC6") (pin "4") (pinfunction "B_4") (pintype "passive"))
      (node (ref "L9") (pin "1") (pinfunction "P$1_1") (pintype "bidirectional"))
      (node (ref "R10") (pin "2") (pinfunction "2_2") (pintype "passive"))
      (node (ref "R56") (pin "2") (pinfunction "2_2") (pintype "passive"))
      (node (ref "TP3") (pin "TP") (pinfunction "TP_TP") (pintype "input"))
    )
    (net (code "131") (name "PP_P5V0_DAC1") (class "Default")
      (node (ref "C102") (pin "1") (pinfunction "1_1") (pintype "passive"))
      (node (ref "C103") (pin "1") (pinfunction "1_1") (pintype "passive"))
      (node (ref "IC31") (pin "10") (pinfunction "VDD_10") (pintype "bidirectional"))
      (node (ref "L9") (pin "2") (pinfunction "P$2_2") (pintype "bidirectional"))
      (node (ref "R73") (pin "1") (pinfunction "1_1") (pintype "passive"))
    )
    (net (code "132") (name "PP_P15V0_ANALOG") (class "Default")
      (node (ref "C10") (pin "1") (pinfunction "1_1") (pintype "passive"))
      (node (ref "C11") (pin "1") (pinfunction "1_1") (pintype "passive"))
      (node (ref "C6") (pin "1") (pinfunction "1_1") (pintype "passive"))
      (node (ref "C7") (pin "1") (pinfunction "1_1") (pintype "passive"))
      (node (ref "C75") (pin "1") (pinfunction "1_1") (pintype "passive"))
      (node (ref "C76") (pin "1") (pinfunction "1_1") (pintype "passive"))
      (node (ref "IC1") (pin "5") (pinfunction "EN_5") (pintype "bidirectional"))
      (node (ref "IC1") (pin "8") (pinfunction "IN_8") (pintype "bidirectional"))
      (node (ref "IC12") (pin "3") (pinfunction "C_3") (pintype "passive"))
      (node (ref "IC12") (pin "6") (pinfunction "C_6") (pintype "passive"))
      (node (ref "IC2") (pin "1") (pinfunction "OUT_1") (pintype "bidirectional"))
      (node (ref "IC25") (pin "12") (pinfunction "E_12") (pintype "passive"))
      (node (ref "IC25") (pin "3") (pinfunction "E_3") (pintype "passive"))
      (node (ref "R11") (pin "2") (pinfunction "2_2") (pintype "passive"))
      (node (ref "R46") (pin "2") (pinfunction "2_2") (pintype "passive"))
      (node (ref "TP1") (pin "TP") (pinfunction "TP_TP") (pintype "input"))
    )
    (net (code "133") (name "PP_P16V0_BOOST") (class "Default")
      (node (ref "C25") (pin "+") (pinfunction "+_+") (pintype "passive"))
      (node (ref "C8") (pin "1") (pinfunction "1_1") (pintype "passive"))
      (node (ref "IC2") (pin "5") (pinfunction "EN_5") (pintype "bidirectional"))
      (node (ref "IC2") (pin "8") (pinfunction "IN_8") (pintype "bidirectional"))
      (node (ref "L3") (pin "4") (pinfunction "4_4") (pintype "bidirectional"))
      (node (ref "R3") (pin "1") (pinfunction "1_1") (pintype "passive"))
      (node (ref "R9") (pin "2") (pinfunction "2_2") (pintype "passive"))
    )
    (net (code "134") (name "PULLDN_SENSE_R_CONN") (class "Default")
      (node (ref "R23") (pin "1") (pinfunction "1_1") (pintype "passive"))
      (node (ref "X1") (pin "1") (pinfunction "1_1") (pintype "passive"))
    )
    (net (code "135") (name "SMPS_USB_VDD") (class "Default")
      (node (ref "C113") (pin "1") (pinfunction "1_1") (pintype "passive"))
      (node (ref "C15") (pin "1") (pinfunction "1_1") (pintype "passive"))
      (node (ref "C17") (pin "1") (pinfunction "1_1") (pintype "passive"))
      (node (ref "C26") (pin "+") (pinfunction "+_+") (pintype "passive"))
      (node (ref "C27") (pin "1") (pinfunction "1_1") (pintype "passive"))
      (node (ref "C45") (pin "1") (pinfunction "1_1") (pintype "passive"))
      (node (ref "C57") (pin "1") (pinfunction "1_1") (pintype "passive"))
      (node (ref "C67") (pin "1") (pinfunction "1_1") (pintype "passive"))
      (node (ref "C79") (pin "2") (pinfunction "2_2") (pintype "passive"))
      (node (ref "D4") (pin "3") (pinfunction "C_3") (pintype "passive"))
      (node (ref "D5") (pin "3") (pinfunction "C_3") (pintype "passive"))
      (node (ref "IC10") (pin "15") (pinfunction "VIN_15") (pintype "bidirectional"))
      (node (ref "IC3") (pin "15") (pinfunction "VIN_15") (pintype "bidirectional"))
      (node (ref "L2") (pin "1") (pinfunction "P$1_1") (pintype "bidirectional"))
      (node (ref "L6") (pin "1") (pinfunction "1_1") (pintype "bidirectional"))
      (node (ref "Q1") (pin "3") (pinfunction "D_3") (pintype "passive"))
      (node (ref "RLY1") (pin "3") (pinfunction "PIN3_3") (pintype "bidirectional"))
      (node (ref "RLY2") (pin "3") (pinfunction "PIN3_3") (pintype "bidirectional"))
    )
    (net (code "136") (name "SPAD_PULLDN_SENSE") (class "Default")
      (node (ref "IC4") (pin "3") (pinfunction "VN_3") (pintype "bidirectional"))
      (node (ref "IC6") (pin "3") (pinfunction "C_3") (pintype "passive"))
      (node (ref "R23") (pin "2") (pinfunction "2_2") (pintype "passive"))
    )
    (net (code "137") (name "STEERING_CASC") (class "Default")
      (node (ref "IC11") (pin "2") (pinfunction "E_2") (pintype "passive"))
      (node (ref "IC13") (pin "3") (pinfunction "C_3") (pintype "passive"))
    )
    (net (code "138") (name "TP_FB_CUK") (class "Default")
      (node (ref "IC10") (pin "7") (pinfunction "FB_7") (pintype "bidirectional"))
      (node (ref "TP10") (pin "TP") (pinfunction "TP_TP") (pintype "input"))
    )
    (net (code "139") (name "TP_NFB_BOOST") (class "Default")
      (node (ref "IC3") (pin "10") (pinfunction "NFB_10") (pintype "bidirectional"))
      (node (ref "TP7") (pin "TP") (pinfunction "TP_TP") (pintype "input"))
    )
    (net (code "140") (name "TP_SYNC_BOOST") (class "Default")
      (node (ref "IC3") (pin "4") (pinfunction "SYNC_4") (pintype "bidirectional"))
      (node (ref "TP2") (pin "TP") (pinfunction "TP_TP") (pintype "input"))
    )
    (net (code "141") (name "TP_SYNC_CUK") (class "Default")
      (node (ref "IC10") (pin "4") (pinfunction "SYNC_4") (pintype "bidirectional"))
      (node (ref "TP8") (pin "TP") (pinfunction "TP_TP") (pintype "input"))
    )
    (net (code "142") (name "USBCONN_P1") (class "Default")
      (node (ref "C105") (pin "1") (pinfunction "1_1") (pintype "passive"))
      (node (ref "L8") (pin "1") (pinfunction "P$1_1") (pintype "bidirectional"))
      (node (ref "X8") (pin "1") (pinfunction "1_1") (pintype "passive"))
    )
    (net (code "143") (name "USBCONN_P4") (class "Default")
      (node (ref "L10") (pin "1") (pinfunction "P$1_1") (pintype "bidirectional"))
      (node (ref "X8") (pin "4") (pinfunction "4_4") (pintype "passive"))
    )
    (net (code "144") (name "USBD_CONN_N") (class "Default")
      (node (ref "IC29") (pin "3") (pinfunction "I/O2_3") (pintype "bidirectional"))
      (node (ref "X8") (pin "2") (pinfunction "2_2") (pintype "passive"))
    )
    (net (code "145") (name "USBD_CONN_P") (class "Default")
      (node (ref "IC29") (pin "1") (pinfunction "I/O1_1_1") (pintype "bidirectional"))
      (node (ref "X8") (pin "3") (pinfunction "3_3") (pintype "passive"))
    )
    (net (code "146") (name "USBD_TVS_N") (class "Default")
      (node (ref "IC29") (pin "4") (pinfunction "I/O2_2_4") (pintype "bidirectional"))
      (node (ref "R70") (pin "2") (pinfunction "2_2") (pintype "passive"))
    )
    (net (code "147") (name "USBD_TVS_P") (class "Default")
      (node (ref "IC29") (pin "6") (pinfunction "I/O1_2_6") (pintype "bidirectional"))
      (node (ref "R67") (pin "2") (pinfunction "2_2") (pintype "passive"))
    )
    (net (code "148") (name "USB_VDD") (class "Default")
      (node (ref "C107") (pin "1") (pinfunction "1_1") (pintype "passive"))
      (node (ref "C108") (pin "1") (pinfunction "1_1") (pintype "passive"))
      (node (ref "IC32") (pin "3") (pinfunction "IN_3") (pintype "bidirectional"))
      (node (ref "L8") (pin "2") (pinfunction "P$2_2") (pintype "bidirectional"))
      (node (ref "Q1") (pin "2") (pinfunction "S_2") (pintype "passive"))
      (node (ref "R62") (pin "2") (pinfunction "2_2") (pintype "passive"))
    )
    (net (code "149") (name "VA_BASE") (class "Default")
      (node (ref "IC23") (pin "4") (pinfunction "B_4") (pintype "passive"))
      (node (ref "IC26") (pin "7") (pinfunction "OUT_7") (pintype "output"))
    )
    (net (code "150") (name "VA_FB") (class "Default")
      (node (ref "IC23") (pin "5") (pinfunction "E_5") (pintype "passive"))
      (node (ref "IC26") (pin "6") (pinfunction "-IN_6") (pintype "input"))
      (node (ref "R50") (pin "2") (pinfunction "2_2") (pintype "passive"))
    )
    (net (code "151") (name "VBB") (class "Default")
      (node (ref "U3") (pin "4") (pinfunction "VBB_4") (pintype "power_in"))
    )
    (net (code "152") (name "VREF_AV_DET") (class "Default")
      (node (ref "C33") (pin "1") (pinfunction "1_1") (pintype "passive"))
      (node (ref "C34") (pin "1") (pinfunction "1_1") (pintype "passive"))
      (node (ref "IC4") (pin "2") (pinfunction "VP_2") (pintype "bidirectional"))
      (node (ref "R17") (pin "1") (pinfunction "1_1") (pintype "passive"))
      (node (ref "R18") (pin "1") (pinfunction "1_1") (pintype "passive"))
      (node (ref "R19") (pin "2") (pinfunction "2_2") (pintype "passive"))
      (node (ref "TP6") (pin "P$1") (pinfunction "P$1_P$1") (pintype "bidirectional"))
    )
    (net (code "153") (name "VREF_DELTAV_SETPOINT") (class "Default")
      (node (ref "IC31") (pin "2") (pinfunction "OUT0_2") (pintype "bidirectional"))
      (node (ref "R64") (pin "2") (pinfunction "2_2") (pintype "passive"))
      (node (ref "TP14") (pin "P$1") (pinfunction "P$1_P$1") (pintype "bidirectional"))
    )
    (net (code "154") (name "VREF_DIAMOND_IBIAS") (class "Default")
      (node (ref "IC28") (pin "3") (pinfunction "+IN_3") (pintype "input"))
      (node (ref "IC31") (pin "3") (pinfunction "OUT1_3") (pintype "bidirectional"))
      (node (ref "TP15") (pin "P$1") (pinfunction "P$1_P$1") (pintype "bidirectional"))
    )
    (net (code "155") (name "VREF_EXTRA_2") (class "Default")
      (node (ref "IC31") (pin "7") (pinfunction "OUT5_7") (pintype "bidirectional"))
      (node (ref "TP19") (pin "P$1") (pinfunction "P$1_P$1") (pintype "bidirectional"))
    )
    (net (code "156") (name "VREF_EXTRA_3") (class "Default")
      (node (ref "IC31") (pin "8") (pinfunction "OUT6_8") (pintype "bidirectional"))
      (node (ref "TP20") (pin "P$1") (pinfunction "P$1_P$1") (pintype "bidirectional"))
    )
    (net (code "157") (name "VREF_EXTRA_4") (class "Default")
      (node (ref "IC31") (pin "9") (pinfunction "OUT7_9") (pintype "bidirectional"))
      (node (ref "TP21") (pin "P$1") (pinfunction "P$1_P$1") (pintype "bidirectional"))
    )
    (net (code "158") (name "VREF_ONE_SHOT_CCS") (class "Default")
      (node (ref "IC31") (pin "6") (pinfunction "OUT4_6") (pintype "bidirectional"))
      (node (ref "R61") (pin "2") (pinfunction "2_2") (pintype "passive"))
      (node (ref "TP18") (pin "P$1") (pinfunction "P$1_P$1") (pintype "bidirectional"))
    )
    (net (code "159") (name "VREF_ONE_SHOT_COMP") (class "Default")
      (node (ref "IC24") (pin "5") (pinfunction "+IN_5") (pintype "input"))
      (node (ref "IC31") (pin "4") (pinfunction "OUT2_4") (pintype "bidirectional"))
      (node (ref "TP16") (pin "P$1") (pinfunction "P$1_P$1") (pintype "bidirectional"))
    )
    (net (code "160") (name "VREF_VA_SETPOINT") (class "Default")
      (node (ref "IC26") (pin "5") (pinfunction "+IN_5") (pintype "input"))
      (node (ref "IC31") (pin "5") (pinfunction "OUT3_5") (pintype "bidirectional"))
      (node (ref "TP17") (pin "P$1") (pinfunction "P$1_P$1") (pintype "bidirectional"))
    )
    (net (code "161") (name "V_IVTEST") (class "Default")
      (node (ref "RLY2") (pin "5") (pinfunction "PIN5_5") (pintype "bidirectional"))
      (node (ref "X7") (pin "1") (pinfunction "1_1") (pintype "passive"))
    )
    (net (code "162") (name "V_SCOPE") (class "Default")
      (node (ref "R35") (pin "2") (pinfunction "2_2") (pintype "passive"))
      (node (ref "TP9") (pin "SIG") (pinfunction "1_SIG") (pintype "passive"))
    )
    (net (code "163") (name "V_SPAD") (class "Default")
      (node (ref "D3") (pin "C") (pinfunction "C_C") (pintype "passive"))
      (node (ref "RLY1") (pin "5") (pinfunction "PIN5_5") (pintype "bidirectional"))
      (node (ref "RLY2") (pin "10") (pinfunction "PIN10_10") (pintype "bidirectional"))
      (node (ref "X4") (pin "1") (pinfunction "1_1") (pintype "passive"))
    )
    (net (code "164") (name "unconnected-(IC4-VTP-Pad1)") (class "Default")
      (node (ref "IC4") (pin "1") (pinfunction "VTP_1") (pintype "bidirectional"))
    )
    (net (code "165") (name "unconnected-(IC30-PA4{slash}SPI1_NSS-Pad20)") (class "Default")
      (node (ref "IC30") (pin "20") (pinfunction "PA4/SPI1_NSS_20") (pintype "bidirectional"))
    )
    (net (code "166") (name "unconnected-(IC30-PA6{slash}SPI1_MISO-Pad22)") (class "Default")
      (node (ref "IC30") (pin "22") (pinfunction "PA6/SPI1_MISO_22") (pintype "bidirectional"))
    )
    (net (code "167") (name "unconnected-(IC30-PA7{slash}SPI1_MOSI-Pad23)") (class "Default")
      (node (ref "IC30") (pin "23") (pinfunction "PA7/SPI1_MOSI_23") (pintype "bidirectional"))
    )
    (net (code "168") (name "unconnected-(IC30-PA8-Pad41)") (class "Default")
      (node (ref "IC30") (pin "41") (pinfunction "PA8_41") (pintype "bidirectional"))
    )
    (net (code "169") (name "unconnected-(IC30-PA9{slash}UART1_TX-Pad42)") (class "Default")
      (node (ref "IC30") (pin "42") (pinfunction "PA9/UART1_TX_42") (pintype "bidirectional"))
    )
    (net (code "170") (name "unconnected-(IC30-PA10{slash}UART1_RX-Pad43)") (class "Default")
      (node (ref "IC30") (pin "43") (pinfunction "PA10/UART1_RX_43") (pintype "bidirectional"))
    )
    (net (code "171") (name "unconnected-(IC30-PB0-Pad26)") (class "Default")
      (node (ref "IC30") (pin "26") (pinfunction "PB0_26") (pintype "bidirectional"))
    )
    (net (code "172") (name "unconnected-(IC30-PB1-Pad27)") (class "Default")
      (node (ref "IC30") (pin "27") (pinfunction "PB1_27") (pintype "bidirectional"))
    )
    (net (code "173") (name "unconnected-(IC30-PB4{slash}JTRST-Pad56)") (class "Default")
      (node (ref "IC30") (pin "56") (pinfunction "PB4/JTRST_56") (pintype "bidirectional"))
    )
    (net (code "174") (name "unconnected-(IC30-PB8-Pad61)") (class "Default")
      (node (ref "IC30") (pin "61") (pinfunction "PB8_61") (pintype "bidirectional"))
    )
    (net (code "175") (name "unconnected-(IC30-PB9-Pad62)") (class "Default")
      (node (ref "IC30") (pin "62") (pinfunction "PB9_62") (pintype "bidirectional"))
    )
    (net (code "176") (name "unconnected-(IC30-PB10-Pad29)") (class "Default")
      (node (ref "IC30") (pin "29") (pinfunction "PB10_29") (pintype "bidirectional"))
    )
    (net (code "177") (name "unconnected-(IC30-PB14{slash}I2S2_XD-Pad35)") (class "Default")
      (node (ref "IC30") (pin "35") (pinfunction "PB14/I2S2_XD_35") (pintype "bidirectional"))
    )
    (net (code "178") (name "unconnected-(IC30-PB15{slash}I2S2_SD-Pad36)") (class "Default")
      (node (ref "IC30") (pin "36") (pinfunction "PB15/I2S2_SD_36") (pintype "bidirectional"))
    )
    (net (code "179") (name "unconnected-(IC30-PC3-Pad11)") (class "Default")
      (node (ref "IC30") (pin "11") (pinfunction "PC3_11") (pintype "bidirectional"))
    )
    (net (code "180") (name "unconnected-(IC30-PC4-Pad24)") (class "Default")
      (node (ref "IC30") (pin "24") (pinfunction "PC4_24") (pintype "bidirectional"))
    )
    (net (code "181") (name "unconnected-(IC30-PC5-Pad25)") (class "Default")
      (node (ref "IC30") (pin "25") (pinfunction "PC5_25") (pintype "bidirectional"))
    )
    (net (code "182") (name "unconnected-(IC30-PC6{slash}I2S2_MCK-Pad37)") (class "Default")
      (node (ref "IC30") (pin "37") (pinfunction "PC6/I2S2_MCK_37") (pintype "bidirectional"))
    )
    (net (code "183") (name "unconnected-(IC30-PC7-Pad38)") (class "Default")
      (node (ref "IC30") (pin "38") (pinfunction "PC7_38") (pintype "bidirectional"))
    )
    (net (code "184") (name "unconnected-(IC30-PC8{slash}SDIO_D0-Pad39)") (class "Default")
      (node (ref "IC30") (pin "39") (pinfunction "PC8/SDIO_D0_39") (pintype "bidirectional"))
    )
    (net (code "185") (name "unconnected-(IC30-PC9{slash}SDIO_D1-Pad40)") (class "Default")
      (node (ref "IC30") (pin "40") (pinfunction "PC9/SDIO_D1_40") (pintype "bidirectional"))
    )
    (net (code "186") (name "unconnected-(IC30-PC13-Pad2)") (class "Default")
      (node (ref "IC30") (pin "2") (pinfunction "PC13_2") (pintype "bidirectional"))
    )
    (net (code "187") (name "unconnected-(IC30-PC14-Pad3)") (class "Default")
      (node (ref "IC30") (pin "3") (pinfunction "PC14_3") (pintype "bidirectional"))
    )
    (net (code "188") (name "unconnected-(IC30-PC15-Pad4)") (class "Default")
      (node (ref "IC30") (pin "4") (pinfunction "PC15_4") (pintype "bidirectional"))
    )
    (net (code "189") (name "unconnected-(RLY1-PIN7-Pad7)") (class "Default")
      (node (ref "RLY1") (pin "7") (pinfunction "PIN7_7") (pintype "bidirectional"))
    )
    (net (code "190") (name "unconnected-(RLY1-PIN8-Pad8)") (class "Default")
      (node (ref "RLY1") (pin "8") (pinfunction "PIN8_8") (pintype "bidirectional"))
    )
    (net (code "191") (name "unconnected-(RLY2-PIN7-Pad7)") (class "Default")
      (node (ref "RLY2") (pin "7") (pinfunction "PIN7_7") (pintype "bidirectional"))
    )
    (net (code "192") (name "unconnected-(RLY2-PIN8-Pad8)") (class "Default")
      (node (ref "RLY2") (pin "8") (pinfunction "PIN8_8") (pintype "bidirectional"))
    )
    (net (code "193") (name "unconnected-(U2-Q1-Pad3)") (class "Default")
      (node (ref "U2") (pin "3") (pinfunction "Q1_3") (pintype "output"))
    )
    (net (code "194") (name "unconnected-(U2-~{Q1}-Pad4)") (class "Default")
      (node (ref "U2") (pin "4") (pinfunction "~{Q1}_4") (pintype "output"))
    )
    (net (code "195") (name "unconnected-(U3-NC-Pad6)") (class "Default")
      (node (ref "U3") (pin "6") (pinfunction "NC_6") (pintype "no_connect"))
    )
    (net (code "196") (name "unconnected-(U3-NC_2-Pad1)") (class "Default")
      (node (ref "U3") (pin "1") (pinfunction "NC_2_1") (pintype "no_connect"))
    )
    (net (code "197") (name "~{FORCE_QUENCH}") (class "Default")
      (node (ref "IC15") (pin "7") (pinfunction "~{PRE}_7") (pintype "bidirectional"))
      (node (ref "IC18") (pin "4") (pinfunction "O_4") (pintype "output"))
      (node (ref "IC22") (pin "1") (pinfunction "I0_1") (pintype "input"))
    )
    (net (code "198") (name "~{LOGIC_QUENCH}") (class "Default")
      (node (ref "IC13") (pin "1") (pinfunction "B_1") (pintype "passive"))
      (node (ref "IC15") (pin "3") (pinfunction "~{Q}_3") (pintype "bidirectional"))
      (node (ref "IC16") (pin "2") (pinfunction "I_2") (pintype "input"))
      (node (ref "TP12") (pin "TP") (pinfunction "TP_TP") (pintype "input"))
    )
    (net (code "199") (name "~{MCU_SHDN_BOOST}") (class "Default")
      (node (ref "IC3") (pin "12") (pinfunction "~{SHDN}_12") (pintype "bidirectional"))
      (node (ref "IC30") (pin "16") (pinfunction "PA2/UART2_TX_16") (pintype "bidirectional"))
    )
    (net (code "200") (name "~{MCU_SHDN_CUK}") (class "Default")
      (node (ref "IC10") (pin "12") (pinfunction "~{SHDN}_12") (pintype "bidirectional"))
      (node (ref "IC30") (pin "15") (pinfunction "PA1_15") (pintype "bidirectional"))
    )
    (net (code "201") (name "~{MCU_SMPS_PRECHG}") (class "Default")
      (node (ref "IC30") (pin "17") (pinfunction "PA3/UART2_RX_17") (pintype "bidirectional"))
      (node (ref "R58") (pin "2") (pinfunction "2_2") (pintype "passive"))
    )
    (net (code "202") (name "~{ONE_SHOT_CLR}") (class "Default")
      (node (ref "IC14") (pin "7") (pinfunction "Q_7") (pintype "bidirectional"))
      (node (ref "IC21") (pin "2") (pinfunction "I1_2") (pintype "input"))
    )
  )
)
